# ams-master-pcb.net
KiCad netlist of a schematic drawn in EAGLE
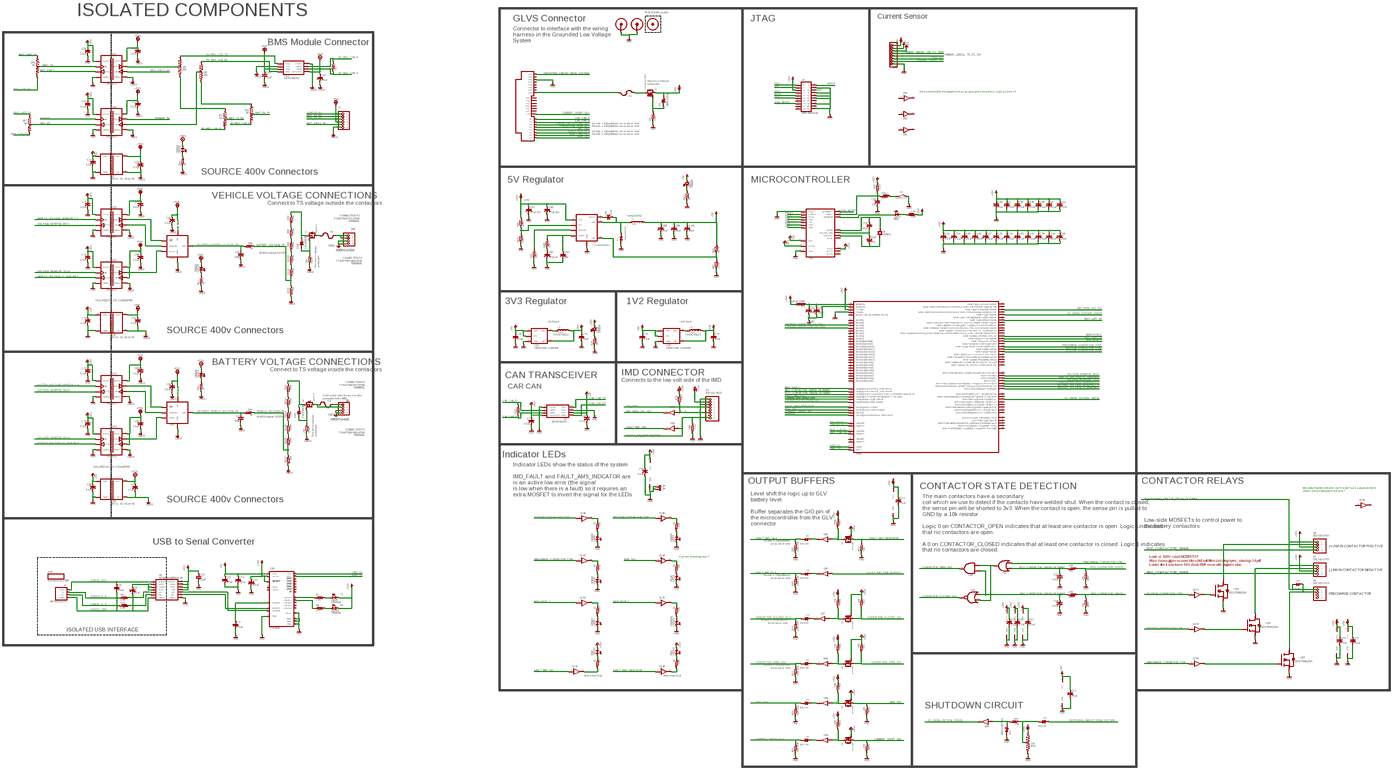
[diagram p0: schematic, sheet 1, overview]
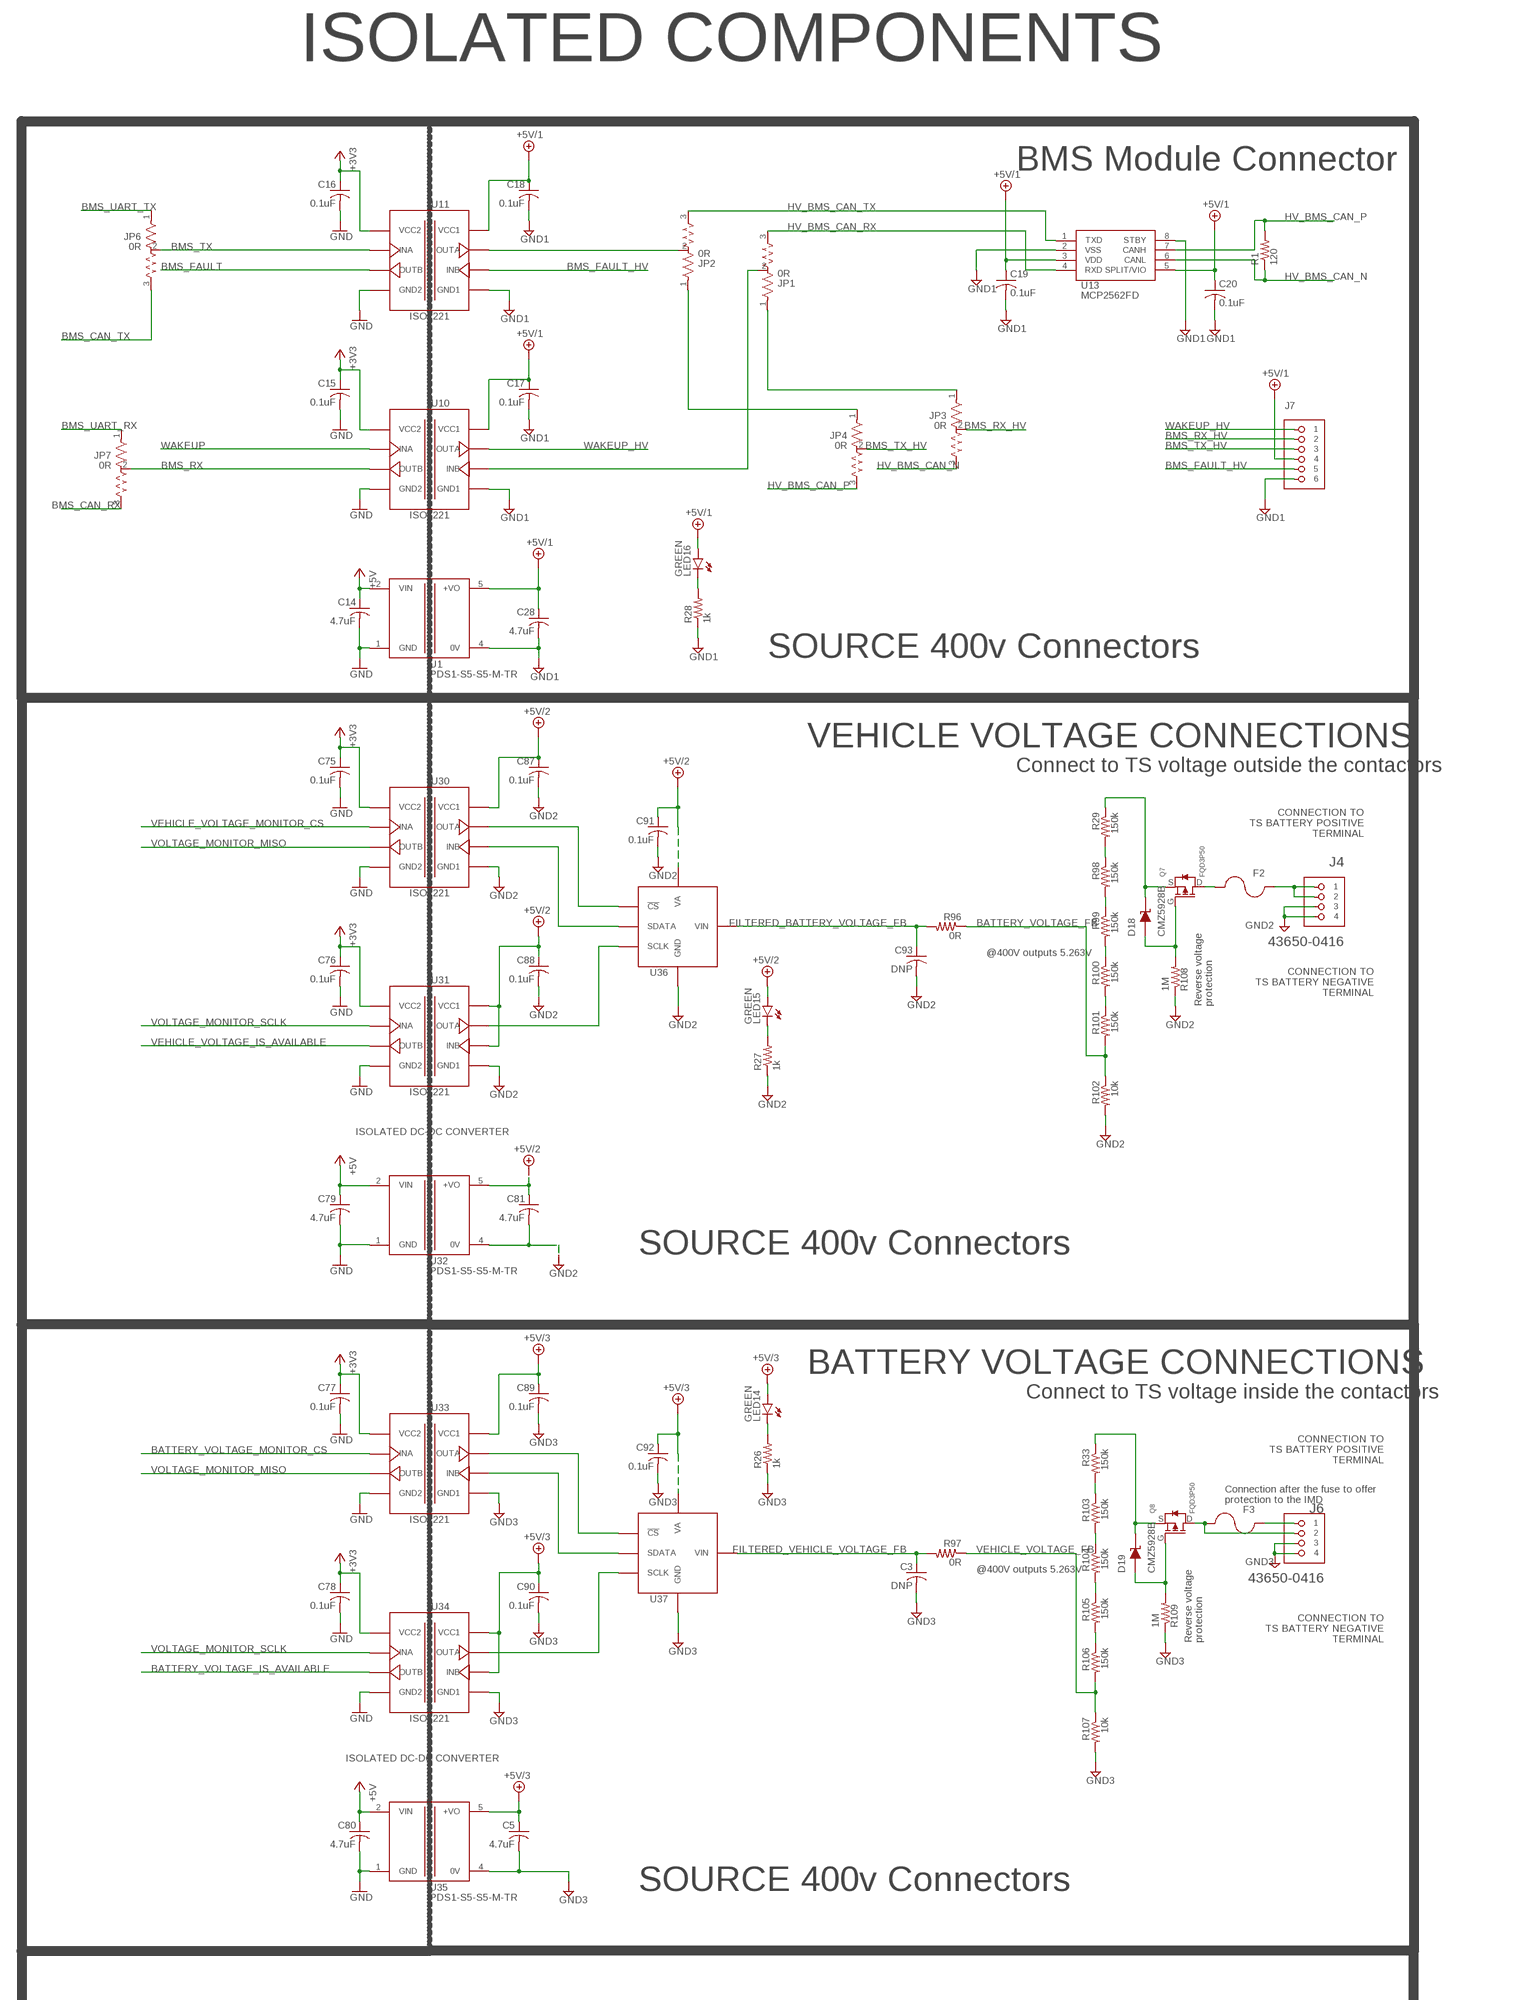
[diagram p1: schematic, sheet 1, part 1 of 6]
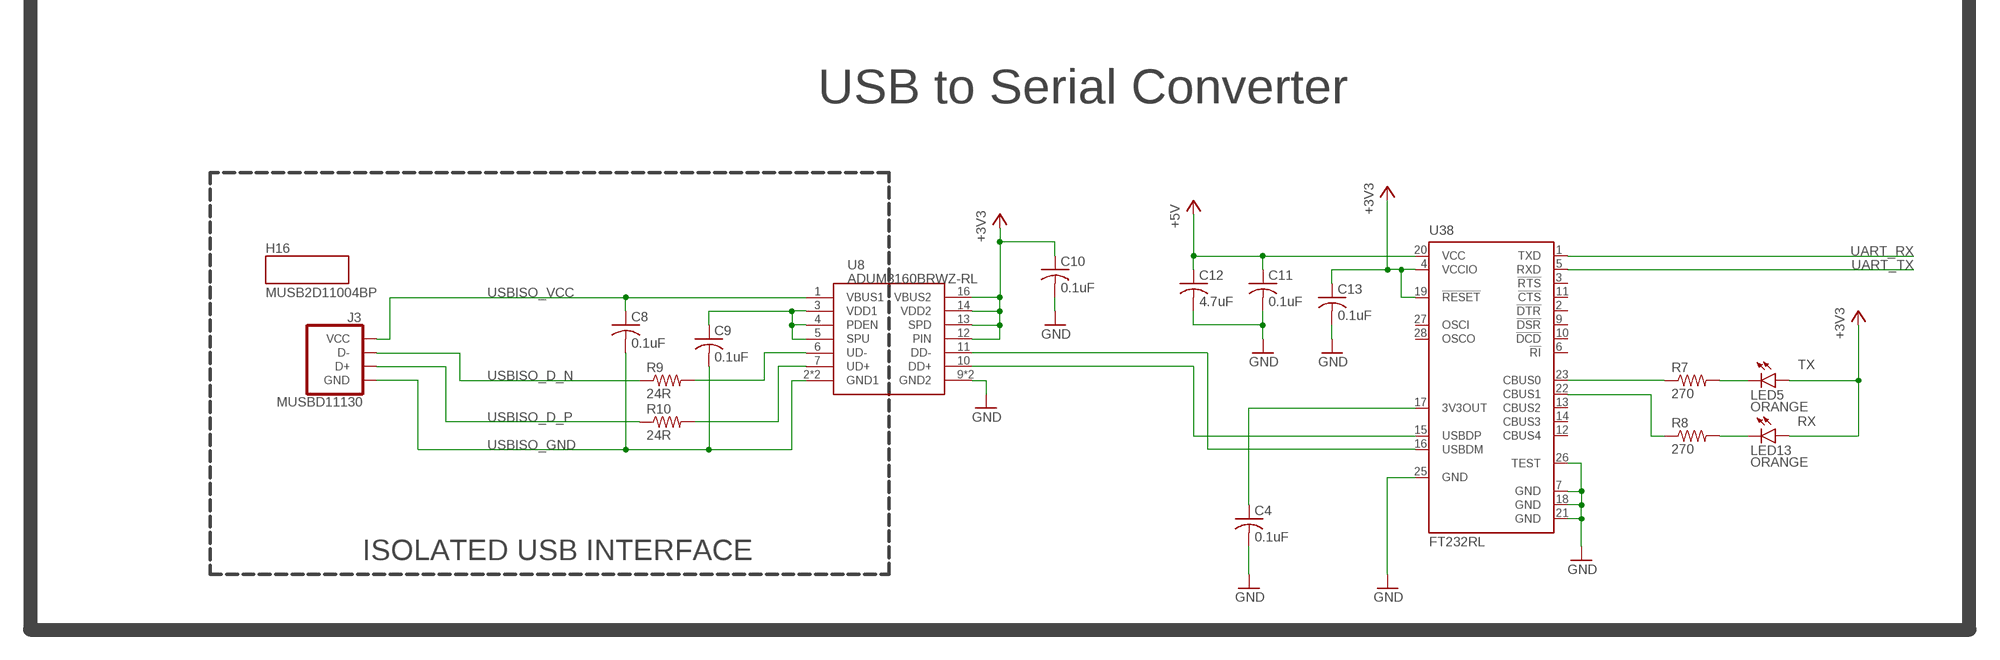
[diagram p2: schematic, sheet 1, part 2 of 6]
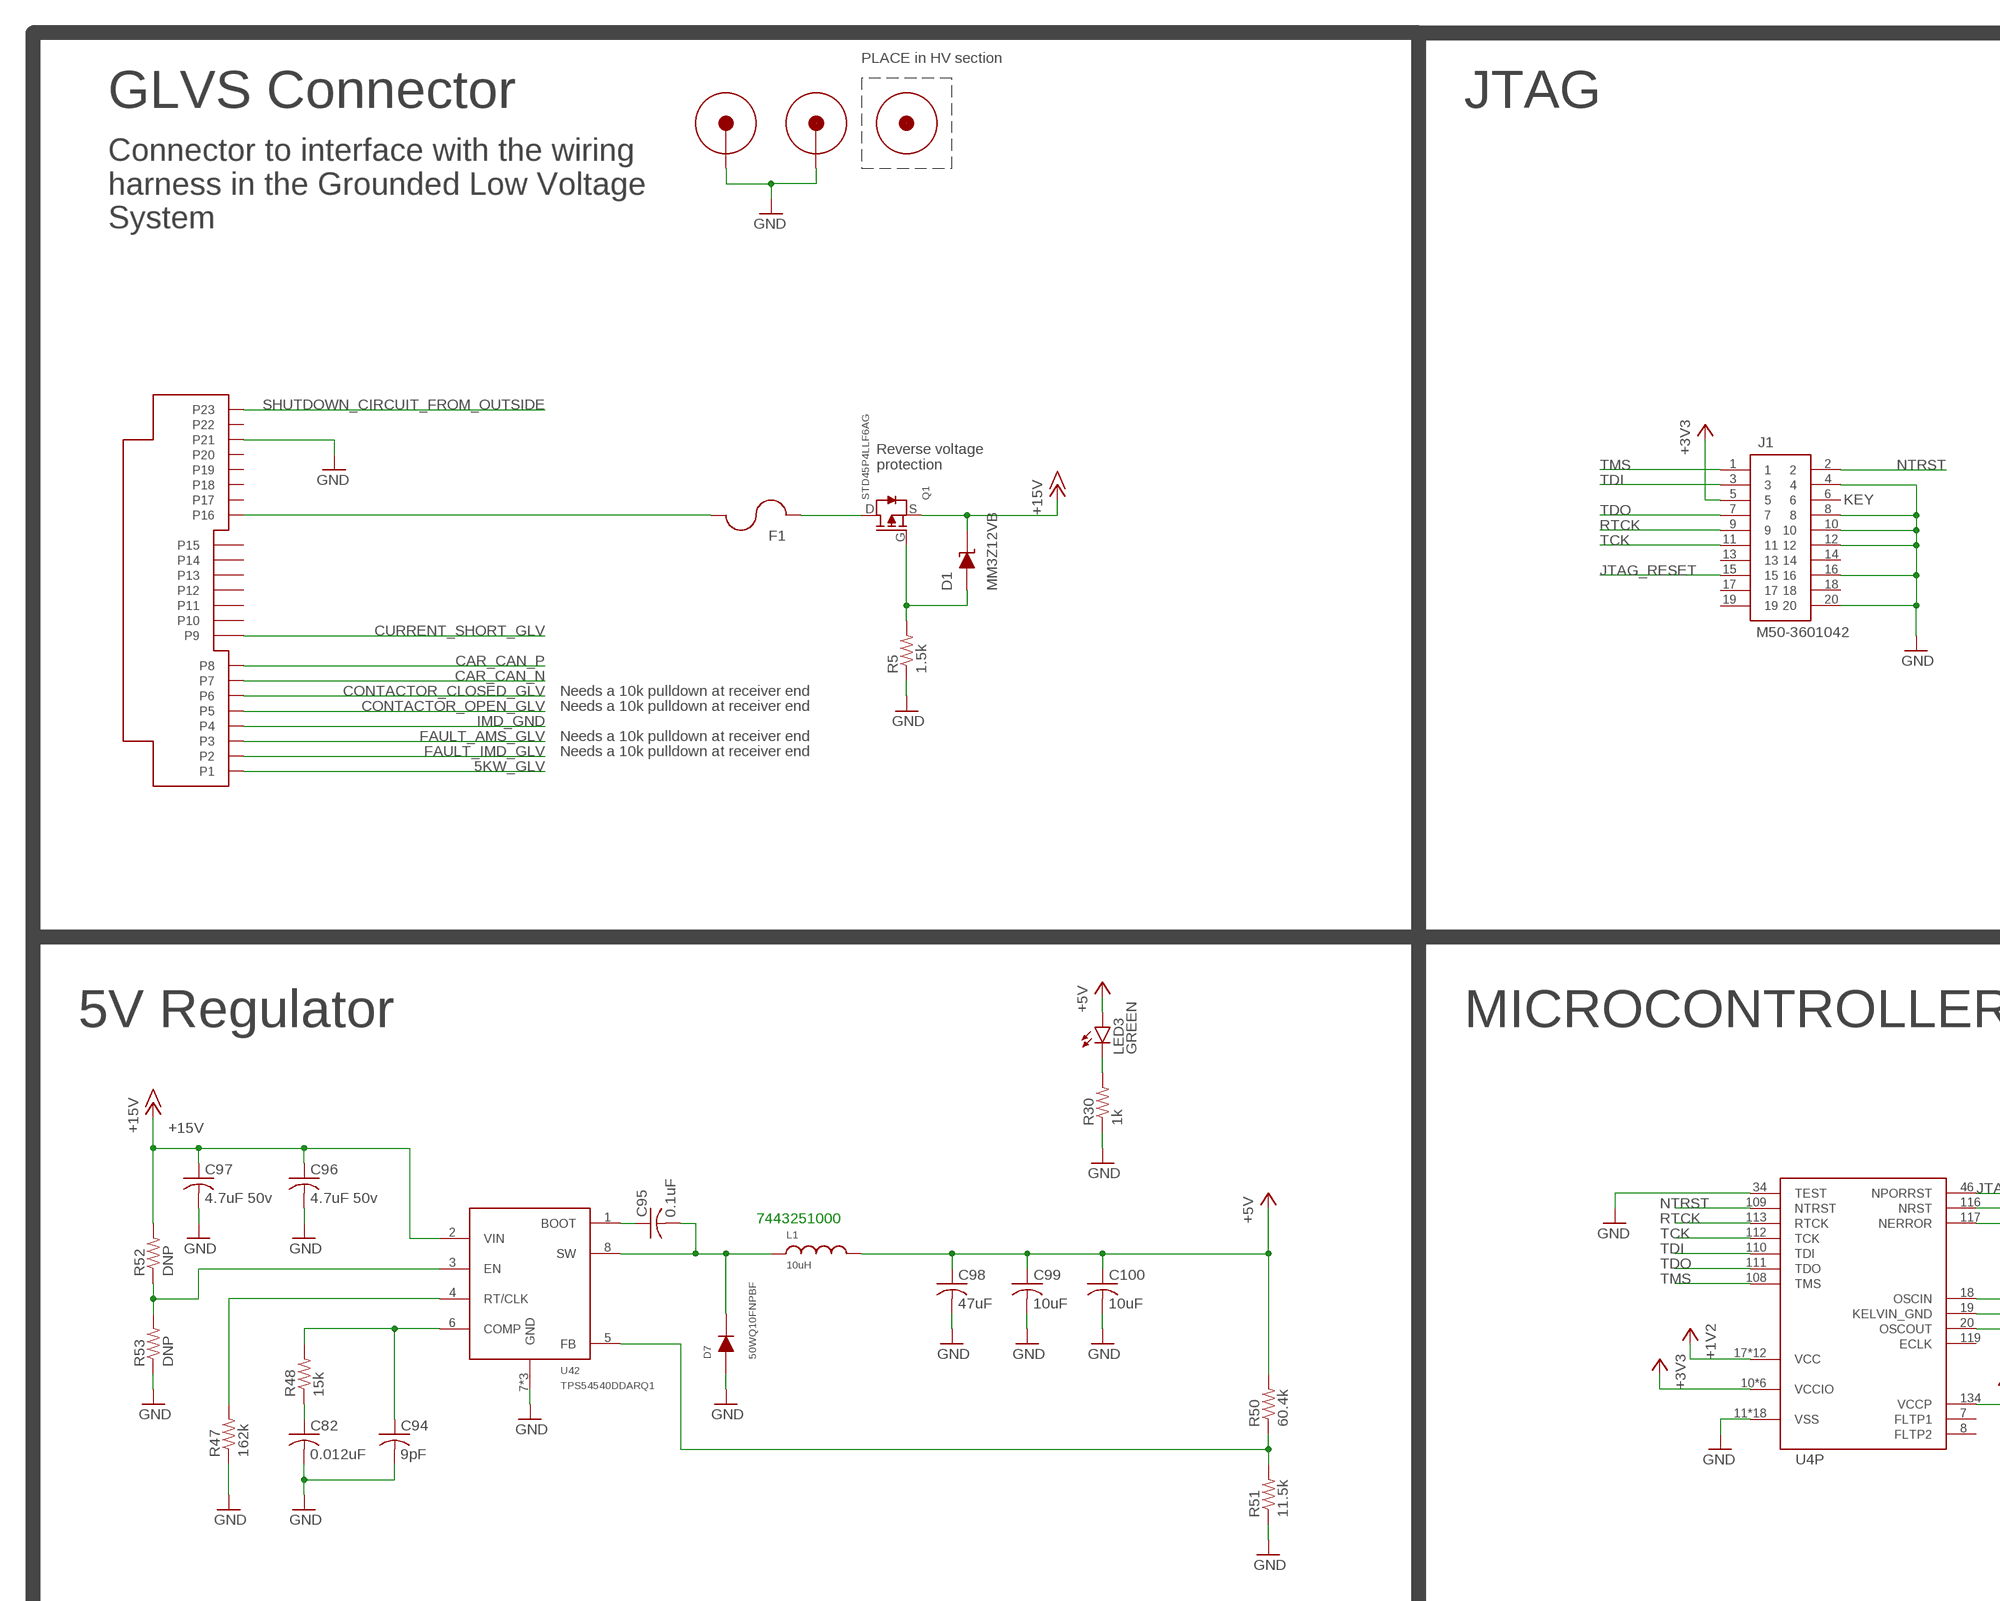
[diagram p3: schematic, sheet 1, part 3 of 6]
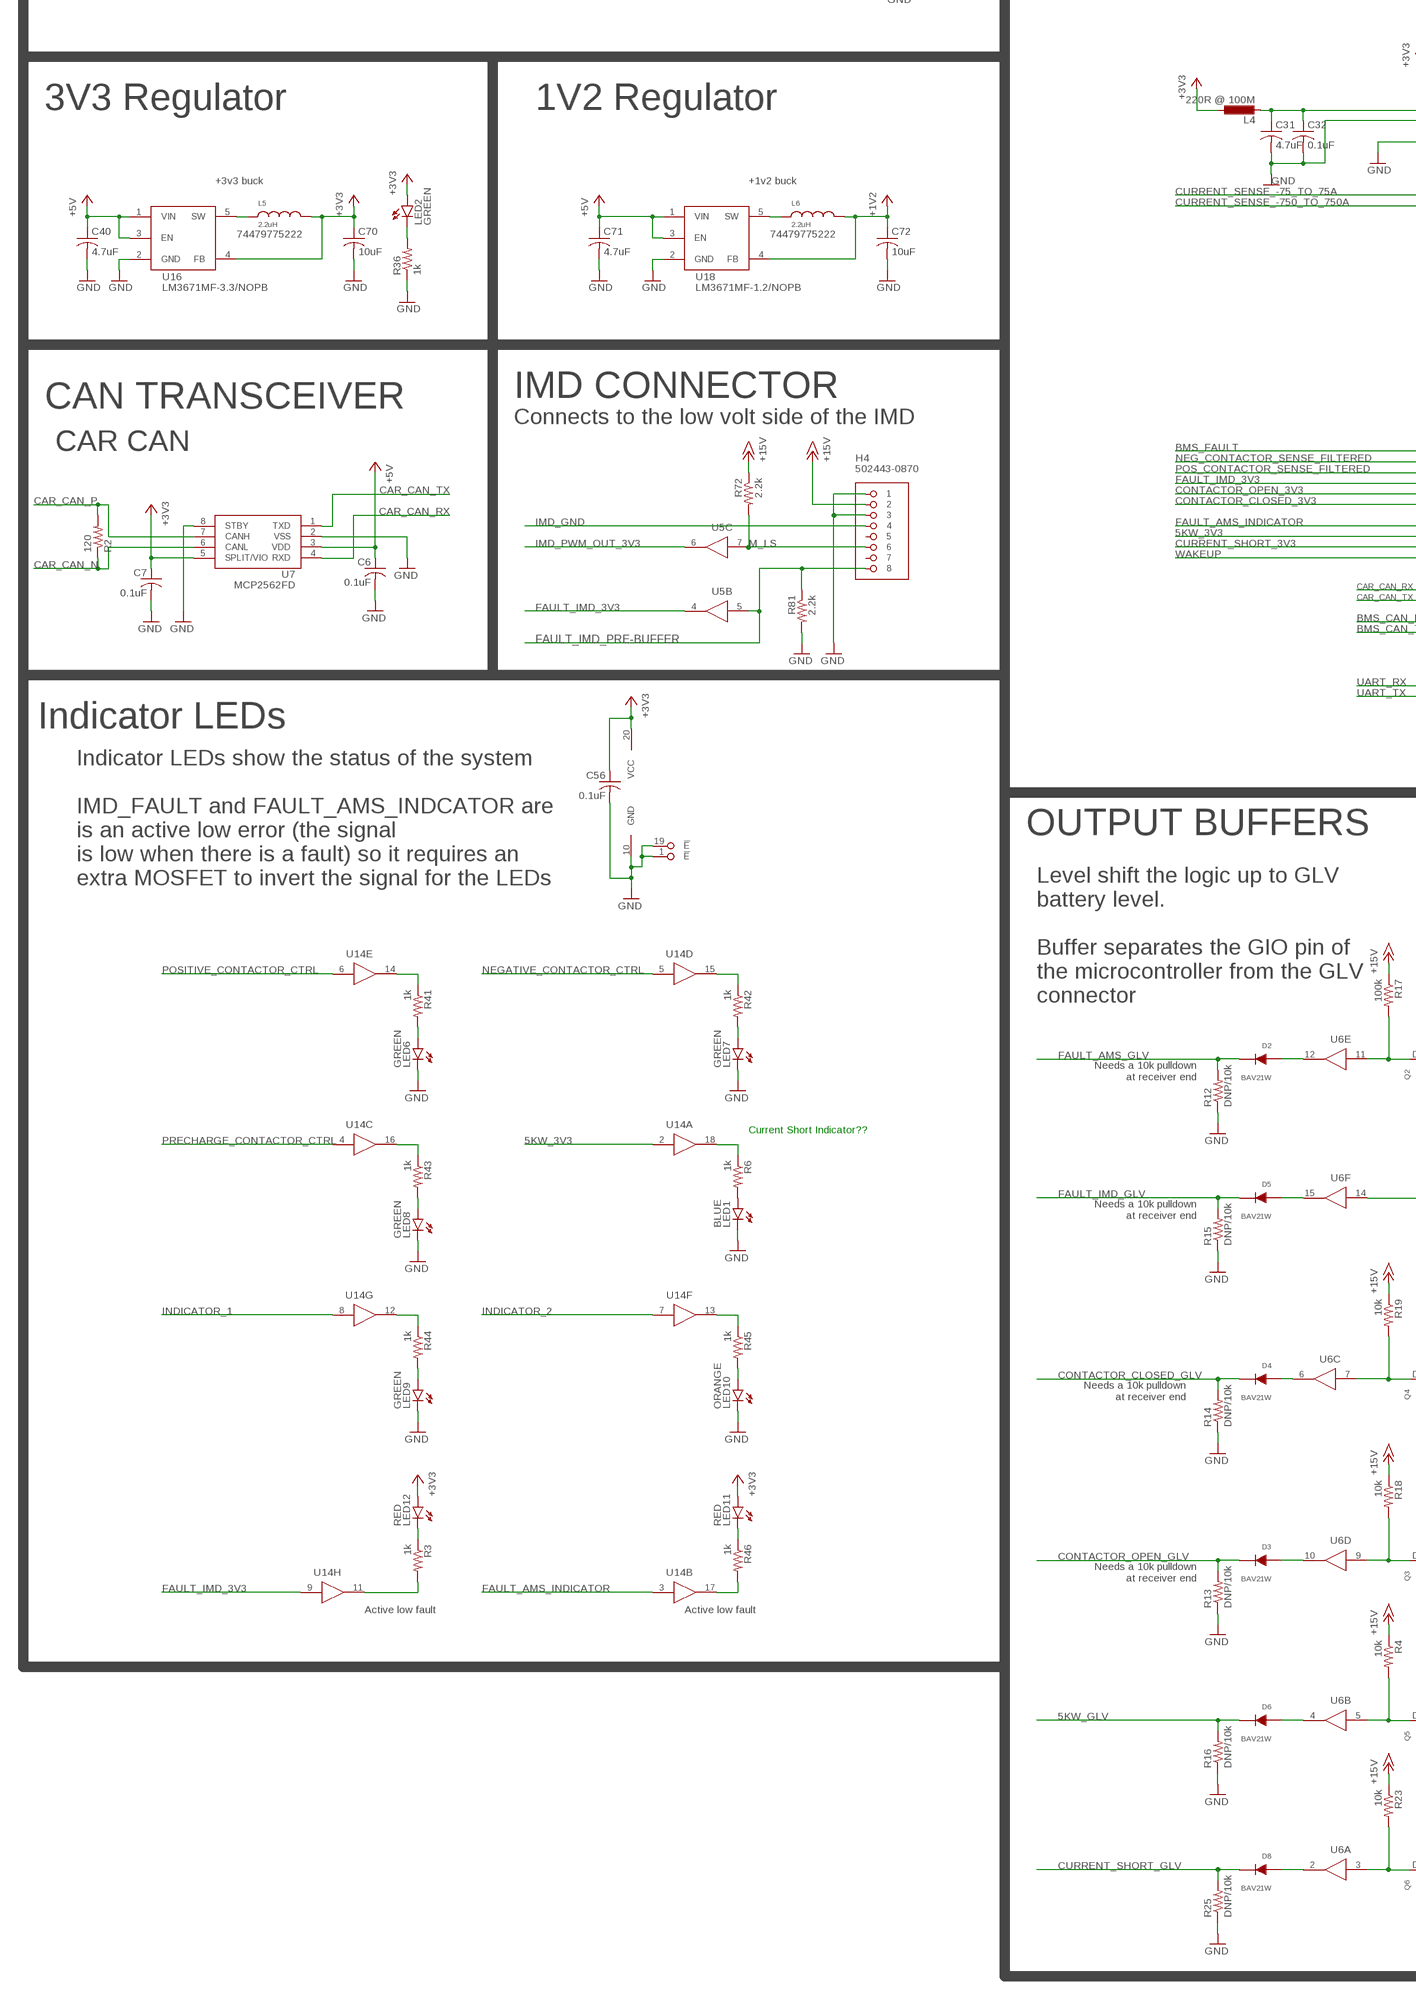
[diagram p4: schematic, sheet 1, part 4 of 6]
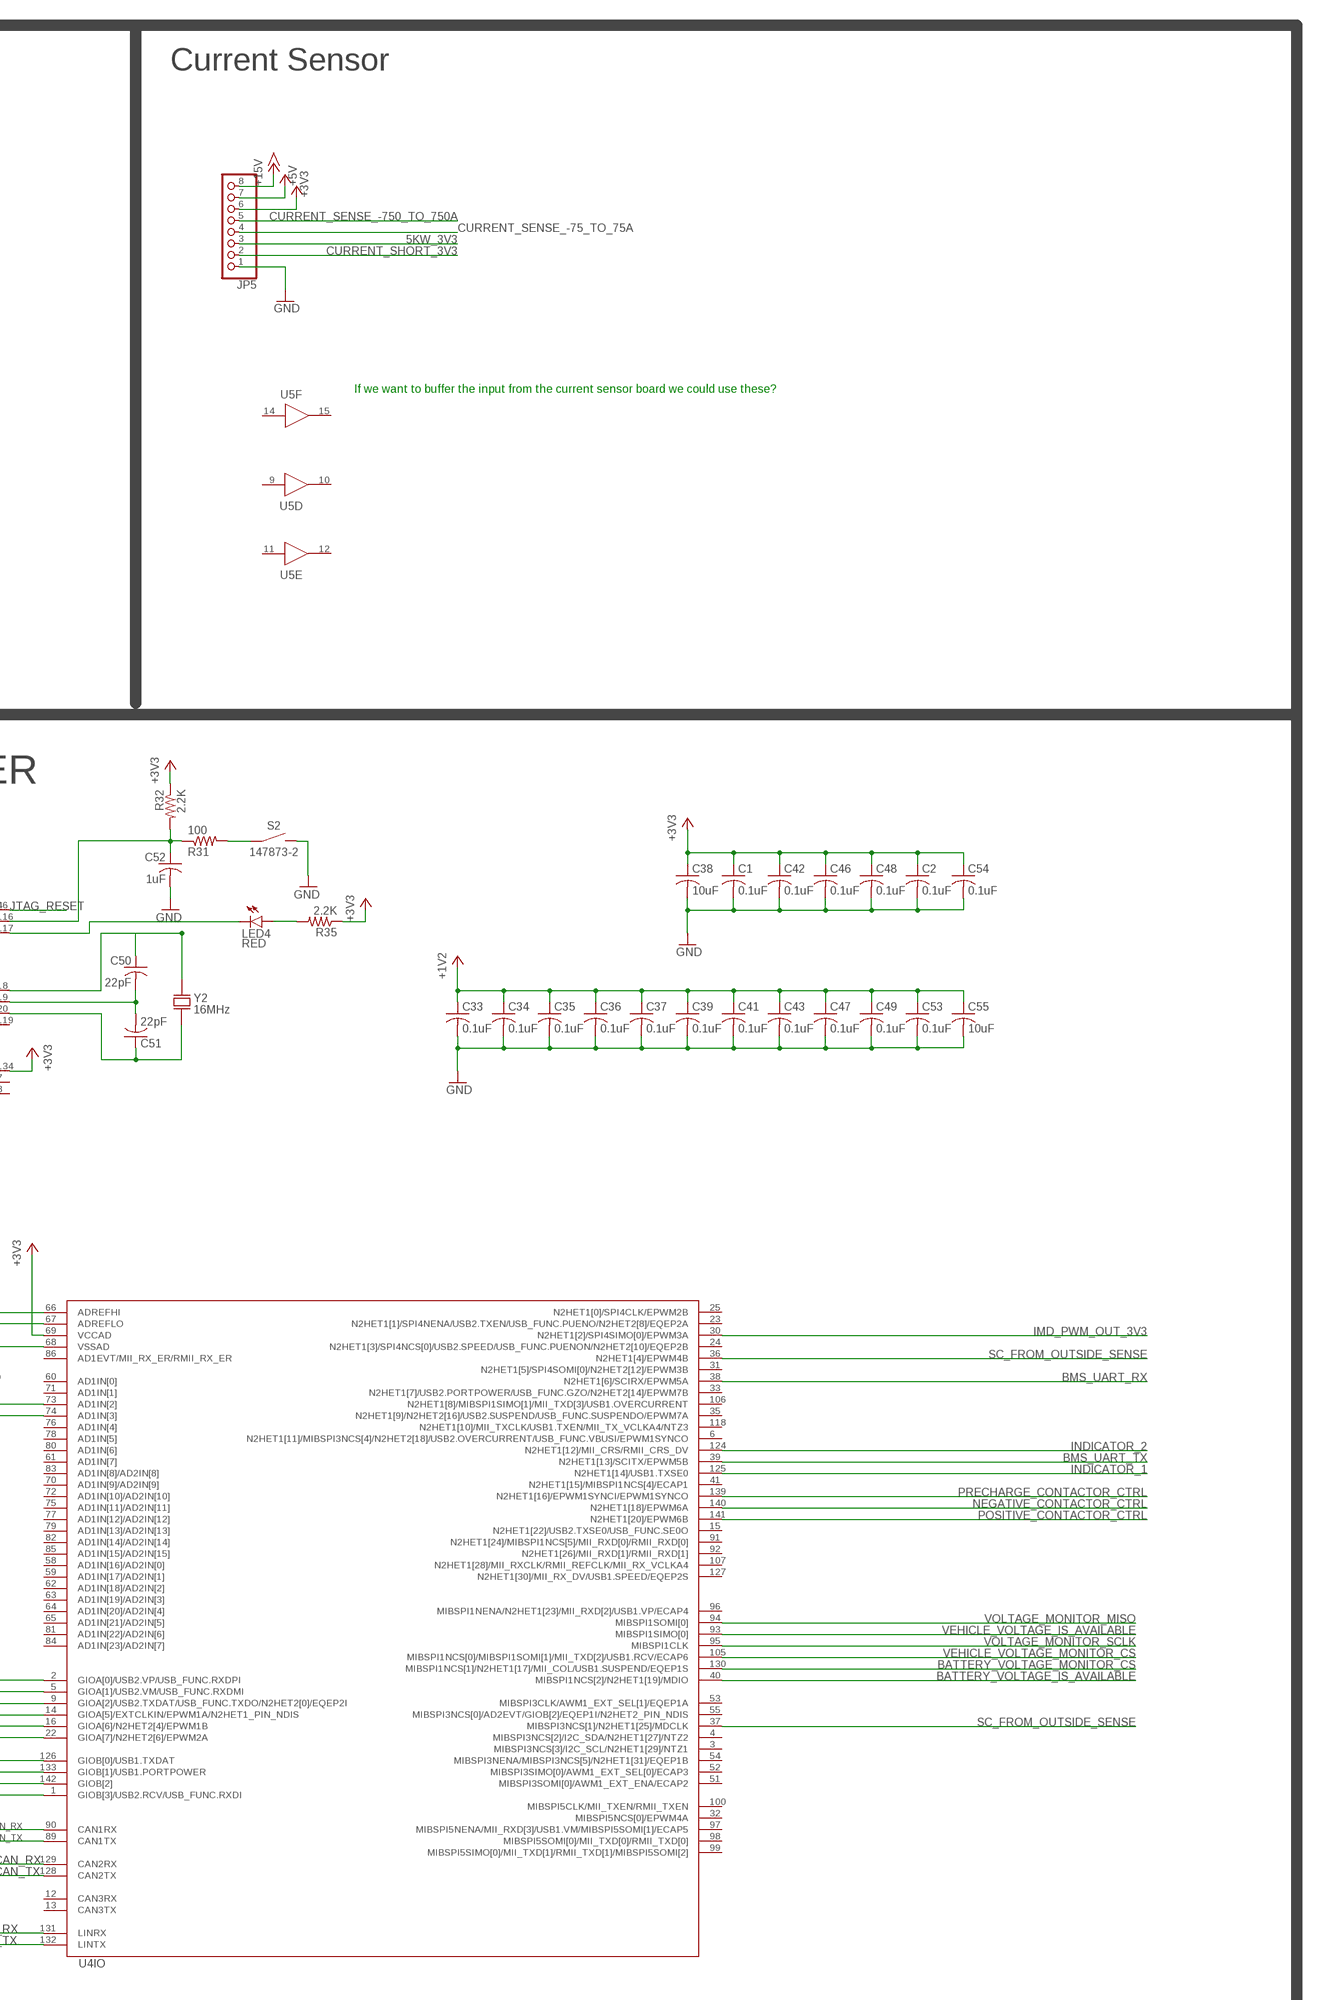
[diagram p5: schematic, sheet 1, part 5 of 6]
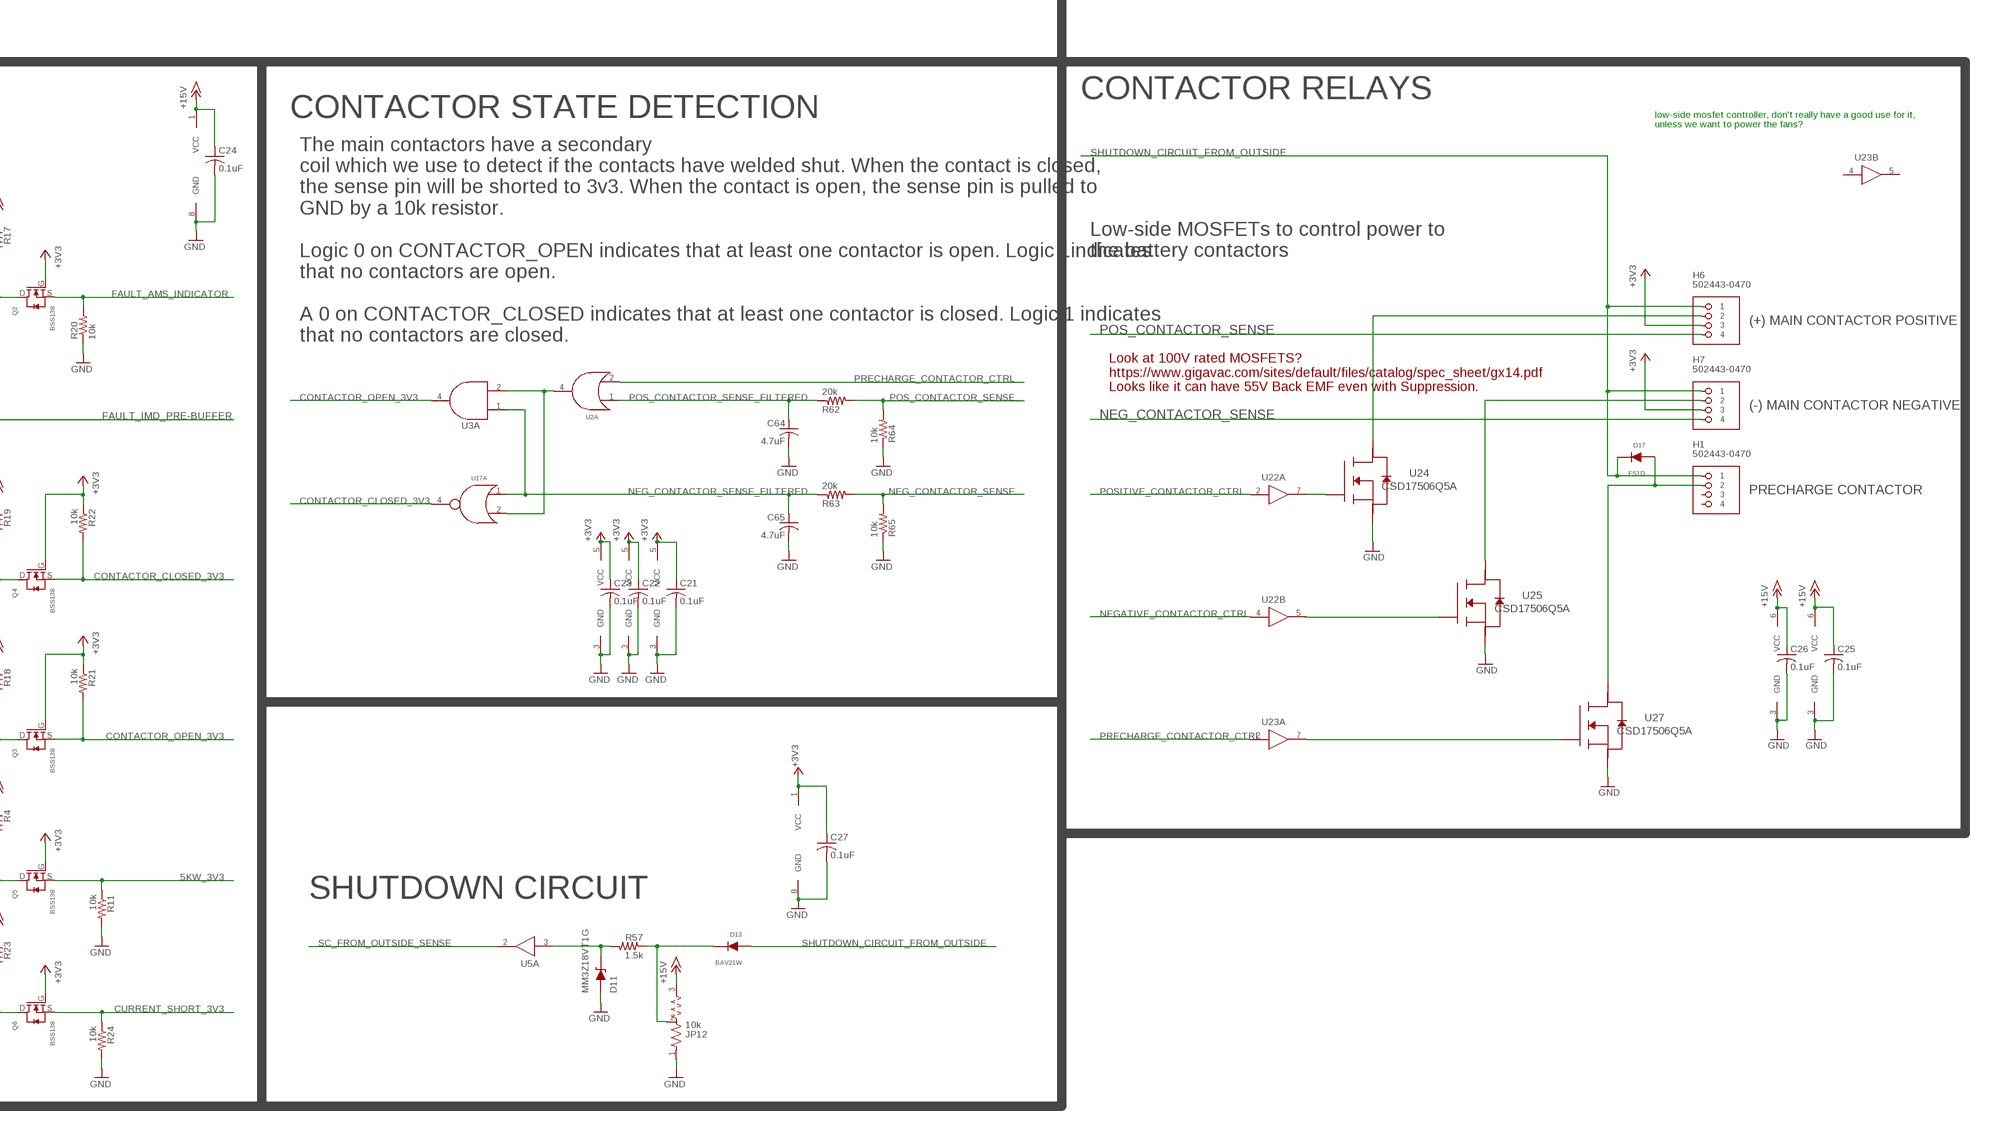
[diagram p6: schematic, sheet 1, part 6 of 6]

(export (version "E")
  (design (tool "Eeschema 10.0.6"))
  (components
    (comp (ref "C1")
      (value "0.1uF")
      (footprint "eagle-import:C0603K")
      (fields (field (name "PARTNO") "GRM188R71E104KA01D"))
      (libsource (lib "eagle-import") (part "C-USC0603K"))
    )
    (comp (ref "C2")
      (value "0.1uF")
      (footprint "eagle-import:C0603K")
      (fields (field (name "PARTNO") "GRM188R71E104KA01D"))
      (libsource (lib "eagle-import") (part "C-USC0603K"))
    )
    (comp (ref "C3")
      (value "DNP")
      (footprint "eagle-import:C0603K")
      (libsource (lib "eagle-import") (part "C-USC0603K"))
    )
    (comp (ref "C4")
      (value "0.1uF")
      (footprint "eagle-import:C0603K")
      (fields (field (name "PARTNO") "GRM188R71E104KA01D"))
      (libsource (lib "eagle-import") (part "C-USC0603K"))
    )
    (comp (ref "C5")
      (value "4.7uF")
      (footprint "eagle-import:C0603K")
      (fields (field (name "PARTNO") "GRM188R61A475KE15D"))
      (libsource (lib "eagle-import") (part "C-USC0603K"))
    )
    (comp (ref "C6")
      (value "0.1uF")
      (footprint "eagle-import:C0603K")
      (fields (field (name "PARTNO") "GRM188R71E104KA01D"))
      (libsource (lib "eagle-import") (part "C-USC0603K"))
    )
    (comp (ref "C7")
      (value "0.1uF")
      (footprint "eagle-import:C0603K")
      (fields (field (name "PARTNO") "GRM188R71E104KA01D"))
      (libsource (lib "eagle-import") (part "C-USC0603K"))
    )
    (comp (ref "C8")
      (value "0.1uF")
      (footprint "eagle-import:C0603K")
      (fields (field (name "PARTNO") "GRM188R71E104KA01D"))
      (libsource (lib "eagle-import") (part "C-USC0603K"))
    )
    (comp (ref "C9")
      (value "0.1uF")
      (footprint "eagle-import:C0603K")
      (fields (field (name "PARTNO") "GRM188R71E104KA01D"))
      (libsource (lib "eagle-import") (part "C-USC0603K"))
    )
    (comp (ref "C10")
      (value "0.1uF")
      (footprint "eagle-import:C0603K")
      (fields (field (name "PARTNO") "GRM188R71E104KA01D"))
      (libsource (lib "eagle-import") (part "C-USC0603K"))
    )
    (comp (ref "C11")
      (value "0.1uF")
      (footprint "eagle-import:C0603K")
      (fields (field (name "PARTNO") "GRM188R71E104KA01D"))
      (libsource (lib "eagle-import") (part "C-USC0603K"))
    )
    (comp (ref "C12")
      (value "4.7uF")
      (footprint "eagle-import:C0603K")
      (fields (field (name "PARTNO") "GRM188R61A475KE15D"))
      (libsource (lib "eagle-import") (part "C-USC0603K"))
    )
    (comp (ref "C13")
      (value "0.1uF")
      (footprint "eagle-import:C0603K")
      (fields (field (name "PARTNO") "GRM188R71E104KA01D"))
      (libsource (lib "eagle-import") (part "C-USC0603K"))
    )
    (comp (ref "C14")
      (value "4.7uF")
      (footprint "eagle-import:C0603K")
      (fields (field (name "PARTNO") "GRM188R61A475KE15D"))
      (libsource (lib "eagle-import") (part "C-USC0603K"))
    )
    (comp (ref "C15")
      (value "0.1uF")
      (footprint "eagle-import:C0603K")
      (fields (field (name "PARTNO") "GRM188R71E104KA01D"))
      (libsource (lib "eagle-import") (part "C-USC0603K"))
    )
    (comp (ref "C16")
      (value "0.1uF")
      (footprint "eagle-import:C0603K")
      (fields (field (name "PARTNO") "GRM188R71E104KA01D"))
      (libsource (lib "eagle-import") (part "C-USC0603K"))
    )
    (comp (ref "C17")
      (value "0.1uF")
      (footprint "eagle-import:C0603K")
      (fields (field (name "PARTNO") "GRM188R71E104KA01D"))
      (libsource (lib "eagle-import") (part "C-USC0603K"))
    )
    (comp (ref "C18")
      (value "0.1uF")
      (footprint "eagle-import:C0603K")
      (fields (field (name "PARTNO") "GRM188R71E104KA01D"))
      (libsource (lib "eagle-import") (part "C-USC0603K"))
    )
    (comp (ref "C19")
      (value "0.1uF")
      (footprint "eagle-import:C0603K")
      (fields (field (name "PARTNO") "GRM188R71E104KA01D"))
      (libsource (lib "eagle-import") (part "C-USC0603K"))
    )
    (comp (ref "C20")
      (value "0.1uF")
      (footprint "eagle-import:C0603K")
      (fields (field (name "PARTNO") "GRM188R71E104KA01D"))
      (libsource (lib "eagle-import") (part "C-USC0603K"))
    )
    (comp (ref "C21")
      (value "0.1uF")
      (footprint "eagle-import:C0603K")
      (fields (field (name "PARTNO") "GRM188R71E104KA01D"))
      (libsource (lib "eagle-import") (part "C-USC0603K"))
    )
    (comp (ref "C22")
      (value "0.1uF")
      (footprint "eagle-import:C0603K")
      (fields (field (name "PARTNO") "GRM188R71E104KA01D"))
      (libsource (lib "eagle-import") (part "C-USC0603K"))
    )
    (comp (ref "C23")
      (value "0.1uF")
      (footprint "eagle-import:C0603K")
      (fields (field (name "PARTNO") "GRM188R71E104KA01D"))
      (libsource (lib "eagle-import") (part "C-USC0603K"))
    )
    (comp (ref "C24")
      (value "0.1uF")
      (footprint "eagle-import:C0603K")
      (fields (field (name "PARTNO") "GRM188R71E104KA01D"))
      (libsource (lib "eagle-import") (part "C-USC0603K"))
    )
    (comp (ref "C25")
      (value "0.1uF")
      (footprint "eagle-import:C0603K")
      (fields (field (name "PARTNO") "GRM188R71E104KA01D"))
      (libsource (lib "eagle-import") (part "C-USC0603K"))
    )
    (comp (ref "C26")
      (value "0.1uF")
      (footprint "eagle-import:C0603K")
      (fields (field (name "PARTNO") "GRM188R71E104KA01D"))
      (libsource (lib "eagle-import") (part "C-USC0603K"))
    )
    (comp (ref "C27")
      (value "0.1uF")
      (footprint "eagle-import:C0603K")
      (fields (field (name "PARTNO") "GRM188R71E104KA01D"))
      (libsource (lib "eagle-import") (part "C-USC0603K"))
    )
    (comp (ref "C28")
      (value "4.7uF")
      (footprint "eagle-import:C0603K")
      (fields (field (name "PARTNO") "GRM188R61A475KE15D"))
      (libsource (lib "eagle-import") (part "C-USC0603K"))
    )
    (comp (ref "C31")
      (value "4.7uF")
      (footprint "eagle-import:C0603K")
      (fields (field (name "PARTNO") "GRM188R61A475KE15D"))
      (libsource (lib "eagle-import") (part "C-USC0603K"))
    )
    (comp (ref "C32")
      (value "0.1uF")
      (footprint "eagle-import:C0603K")
      (fields (field (name "PARTNO") "GRM188R71E104KA01D"))
      (libsource (lib "eagle-import") (part "C-USC0603K"))
    )
    (comp (ref "C33")
      (value "0.1uF")
      (footprint "eagle-import:C0603K")
      (fields (field (name "PARTNO") "GRM188R71E104KA01D"))
      (libsource (lib "eagle-import") (part "C-USC0603K"))
    )
    (comp (ref "C34")
      (value "0.1uF")
      (footprint "eagle-import:C0603K")
      (fields (field (name "PARTNO") "GRM188R71E104KA01D"))
      (libsource (lib "eagle-import") (part "C-USC0603K"))
    )
    (comp (ref "C35")
      (value "0.1uF")
      (footprint "eagle-import:C0603K")
      (fields (field (name "PARTNO") "GRM188R71E104KA01D"))
      (libsource (lib "eagle-import") (part "C-USC0603K"))
    )
    (comp (ref "C36")
      (value "0.1uF")
      (footprint "eagle-import:C0603K")
      (fields (field (name "PARTNO") "GRM188R71E104KA01D"))
      (libsource (lib "eagle-import") (part "C-USC0603K"))
    )
    (comp (ref "C37")
      (value "0.1uF")
      (footprint "eagle-import:C0603K")
      (fields (field (name "PARTNO") "GRM188R71E104KA01D"))
      (libsource (lib "eagle-import") (part "C-USC0603K"))
    )
    (comp (ref "C38")
      (value "10uF")
      (footprint "eagle-import:C0603K")
      (fields (field (name "PARTNO") "GRM188R61A106KE69D"))
      (libsource (lib "eagle-import") (part "C-USC0603K"))
    )
    (comp (ref "C39")
      (value "0.1uF")
      (footprint "eagle-import:C0603K")
      (fields (field (name "PARTNO") "GRM188R71E104KA01D"))
      (libsource (lib "eagle-import") (part "C-USC0603K"))
    )
    (comp (ref "C40")
      (value "4.7uF")
      (footprint "eagle-import:C0603K")
      (fields (field (name "PARTNO") "GRM188R61E475KE11D"))
      (libsource (lib "eagle-import") (part "C-USC0603K"))
    )
    (comp (ref "C41")
      (value "0.1uF")
      (footprint "eagle-import:C0603K")
      (fields (field (name "PARTNO") "GRM188R71E104KA01D"))
      (libsource (lib "eagle-import") (part "C-USC0603K"))
    )
    (comp (ref "C42")
      (value "0.1uF")
      (footprint "eagle-import:C0603K")
      (fields (field (name "PARTNO") "GRM188R71E104KA01D"))
      (libsource (lib "eagle-import") (part "C-USC0603K"))
    )
    (comp (ref "C43")
      (value "0.1uF")
      (footprint "eagle-import:C0603K")
      (fields (field (name "PARTNO") "GRM188R71E104KA01D"))
      (libsource (lib "eagle-import") (part "C-USC0603K"))
    )
    (comp (ref "C46")
      (value "0.1uF")
      (footprint "eagle-import:C0603K")
      (fields (field (name "PARTNO") "GRM188R71E104KA01D"))
      (libsource (lib "eagle-import") (part "C-USC0603K"))
    )
    (comp (ref "C47")
      (value "0.1uF")
      (footprint "eagle-import:C0603K")
      (fields (field (name "PARTNO") "GRM188R71E104KA01D"))
      (libsource (lib "eagle-import") (part "C-USC0603K"))
    )
    (comp (ref "C48")
      (value "0.1uF")
      (footprint "eagle-import:C0603K")
      (fields (field (name "PARTNO") "GRM188R71E104KA01D"))
      (libsource (lib "eagle-import") (part "C-USC0603K"))
    )
    (comp (ref "C49")
      (value "0.1uF")
      (footprint "eagle-import:C0603K")
      (fields (field (name "PARTNO") "GRM188R71E104KA01D"))
      (libsource (lib "eagle-import") (part "C-USC0603K"))
    )
    (comp (ref "C50")
      (value "22pF")
      (footprint "eagle-import:C0603K")
      (fields (field (name "PARTNO") "C1608C0G1H220J080AA"))
      (libsource (lib "eagle-import") (part "C-USC0603K"))
    )
    (comp (ref "C51")
      (value "22pF")
      (footprint "eagle-import:C0603K")
      (fields (field (name "PARTNO") "C1608C0G1H220J080AA"))
      (libsource (lib "eagle-import") (part "C-USC0603K"))
    )
    (comp (ref "C52")
      (value "1uF")
      (footprint "eagle-import:C0603K")
      (fields (field (name "PARTNO") "GRM188R61E105KA12D"))
      (libsource (lib "eagle-import") (part "C-USC0603K"))
    )
    (comp (ref "C53")
      (value "0.1uF")
      (footprint "eagle-import:C0603K")
      (fields (field (name "PARTNO") "GRM188R71E104KA01D"))
      (libsource (lib "eagle-import") (part "C-USC0603K"))
    )
    (comp (ref "C54")
      (value "0.1uF")
      (footprint "eagle-import:C0603K")
      (fields (field (name "PARTNO") "GRM188R71E104KA01D"))
      (libsource (lib "eagle-import") (part "C-USC0603K"))
    )
    (comp (ref "C55")
      (value "10uF")
      (footprint "eagle-import:C0603K")
      (fields (field (name "PARTNO") "GRM188R61A106KE69D"))
      (libsource (lib "eagle-import") (part "C-USC0603K"))
    )
    (comp (ref "C56")
      (value "0.1uF")
      (footprint "eagle-import:C0603K")
      (fields (field (name "PARTNO") "GRM188R71E104KA01D"))
      (libsource (lib "eagle-import") (part "C-USC0603K"))
    )
    (comp (ref "C64")
      (value "4.7uF")
      (footprint "eagle-import:C0603K")
      (fields (field (name "PARTNO") "GRM188R61A475KE15D"))
      (libsource (lib "eagle-import") (part "C-USC0603K"))
    )
    (comp (ref "C65")
      (value "4.7uF")
      (footprint "eagle-import:C0603K")
      (fields (field (name "PARTNO") "GRM188R61A475KE15D"))
      (libsource (lib "eagle-import") (part "C-USC0603K"))
    )
    (comp (ref "C70")
      (value "10uF")
      (footprint "eagle-import:C0603K")
      (fields (field (name "PARTNO") "GRM188R61A106KE69D"))
      (libsource (lib "eagle-import") (part "C-USC0603K"))
    )
    (comp (ref "C71")
      (value "4.7uF")
      (footprint "eagle-import:C0603K")
      (fields (field (name "PARTNO") "GRM188R61E475KE11D"))
      (libsource (lib "eagle-import") (part "C-USC0603K"))
    )
    (comp (ref "C72")
      (value "10uF")
      (footprint "eagle-import:C0603K")
      (fields (field (name "PARTNO") "GRM188R61A106KE69D"))
      (libsource (lib "eagle-import") (part "C-USC0603K"))
    )
    (comp (ref "C75")
      (value "0.1uF")
      (footprint "eagle-import:C0603K")
      (fields (field (name "PARTNO") "GRM188R71E104KA01D"))
      (libsource (lib "eagle-import") (part "C-USC0603K"))
    )
    (comp (ref "C76")
      (value "0.1uF")
      (footprint "eagle-import:C0603K")
      (fields (field (name "PARTNO") "GRM188R71E104KA01D"))
      (libsource (lib "eagle-import") (part "C-USC0603K"))
    )
    (comp (ref "C77")
      (value "0.1uF")
      (footprint "eagle-import:C0603K")
      (fields (field (name "PARTNO") "GRM188R71E104KA01D"))
      (libsource (lib "eagle-import") (part "C-USC0603K"))
    )
    (comp (ref "C78")
      (value "0.1uF")
      (footprint "eagle-import:C0603K")
      (fields (field (name "PARTNO") "GRM188R71E104KA01D"))
      (libsource (lib "eagle-import") (part "C-USC0603K"))
    )
    (comp (ref "C79")
      (value "4.7uF")
      (footprint "eagle-import:C0603K")
      (fields (field (name "PARTNO") "GRM188R61A475KE15D"))
      (libsource (lib "eagle-import") (part "C-USC0603K"))
    )
    (comp (ref "C80")
      (value "4.7uF")
      (footprint "eagle-import:C0603K")
      (fields (field (name "PARTNO") "GRM188R61A475KE15D"))
      (libsource (lib "eagle-import") (part "C-USC0603K"))
    )
    (comp (ref "C81")
      (value "4.7uF")
      (footprint "eagle-import:C0603K")
      (fields (field (name "PARTNO") "GRM188R61A475KE15D"))
      (libsource (lib "eagle-import") (part "C-USC0603K"))
    )
    (comp (ref "C82")
      (value "0.012uF")
      (footprint "eagle-import:C0603K")
      (fields (field (name "PARTNO") "GRM188R71H123KA01D"))
      (libsource (lib "eagle-import") (part "C-USC0603K"))
    )
    (comp (ref "C87")
      (value "0.1uF")
      (footprint "eagle-import:C0603K")
      (fields (field (name "PARTNO") "GRM188R71E104KA01D"))
      (libsource (lib "eagle-import") (part "C-USC0603K"))
    )
    (comp (ref "C88")
      (value "0.1uF")
      (footprint "eagle-import:C0603K")
      (fields (field (name "PARTNO") "GRM188R71E104KA01D"))
      (libsource (lib "eagle-import") (part "C-USC0603K"))
    )
    (comp (ref "C89")
      (value "0.1uF")
      (footprint "eagle-import:C0603K")
      (fields (field (name "PARTNO") "GRM188R71E104KA01D"))
      (libsource (lib "eagle-import") (part "C-USC0603K"))
    )
    (comp (ref "C90")
      (value "0.1uF")
      (footprint "eagle-import:C0603K")
      (fields (field (name "PARTNO") "GRM188R71E104KA01D"))
      (libsource (lib "eagle-import") (part "C-USC0603K"))
    )
    (comp (ref "C91")
      (value "0.1uF")
      (footprint "eagle-import:C0603K")
      (fields (field (name "PARTNO") "GRM188R71E104KA01D"))
      (libsource (lib "eagle-import") (part "C-USC0603K"))
    )
    (comp (ref "C92")
      (value "0.1uF")
      (footprint "eagle-import:C0603K")
      (fields (field (name "PARTNO") "GRM188R71E104KA01D"))
      (libsource (lib "eagle-import") (part "C-USC0603K"))
    )
    (comp (ref "C93")
      (value "DNP")
      (footprint "eagle-import:C0603K")
      (libsource (lib "eagle-import") (part "C-USC0603K"))
    )
    (comp (ref "C94")
      (value "9pF")
      (footprint "eagle-import:C0603K")
      (fields (field (name "PARTNO") "GRM1885C1H9R0DA01D"))
      (libsource (lib "eagle-import") (part "C-USC0603K"))
    )
    (comp (ref "C95")
      (value "0.1uF")
      (footprint "eagle-import:C0603K")
      (fields (field (name "PARTNO") "GRM188R71E104KA01D"))
      (libsource (lib "eagle-import") (part "C-USC0603K"))
    )
    (comp (ref "C96")
      (value "4.7uF 50v")
      (footprint "eagle-import:C1206")
      (fields (field (name "PARTNO") "GRM31CR71H475KA12L"))
      (libsource (lib "eagle-import") (part "C-USC1206"))
    )
    (comp (ref "C97")
      (value "4.7uF 50v")
      (footprint "eagle-import:C1206")
      (fields (field (name "PARTNO") "GRM31CR71H475KA12L"))
      (libsource (lib "eagle-import") (part "C-USC1206"))
    )
    (comp (ref "C98")
      (value "47uF")
      (footprint "eagle-import:C1206")
      (fields (field (name "PARTNO") "GRM31CR61A476ME15L"))
      (libsource (lib "eagle-import") (part "C-USC1206"))
    )
    (comp (ref "C99")
      (value "10uF")
      (footprint "eagle-import:C0603K")
      (fields (field (name "PARTNO") "GRM188R61A106KE69D"))
      (libsource (lib "eagle-import") (part "C-USC0603K"))
    )
    (comp (ref "C100")
      (value "10uF")
      (footprint "eagle-import:C0603K")
      (fields (field (name "PARTNO") "GRM188R61A106KE69D"))
      (libsource (lib "eagle-import") (part "C-USC0603K"))
    )
    (comp (ref "D1")
      (value "MM3Z12VB")
      (footprint "eagle-import:SOD323F")
      (libsource (lib "eagle-import") (part "MM3Z12VB"))
    )
    (comp (ref "D2")
      (value "BAV21W")
      (footprint "eagle-import:BAV21W")
      (fields (field (name "PARTNO") "BAV21WS-TP"))
      (libsource (lib "eagle-import") (part "BAV21W"))
    )
    (comp (ref "D3")
      (value "BAV21W")
      (footprint "eagle-import:BAV21W")
      (fields (field (name "PARTNO") "BAV21WS-TP"))
      (libsource (lib "eagle-import") (part "BAV21W"))
    )
    (comp (ref "D4")
      (value "BAV21W")
      (footprint "eagle-import:BAV21W")
      (fields (field (name "PARTNO") "BAV21WS-TP"))
      (libsource (lib "eagle-import") (part "BAV21W"))
    )
    (comp (ref "D5")
      (value "BAV21W")
      (footprint "eagle-import:BAV21W")
      (fields (field (name "PARTNO") "BAV21WS-TP"))
      (libsource (lib "eagle-import") (part "BAV21W"))
    )
    (comp (ref "D6")
      (value "BAV21W")
      (footprint "eagle-import:BAV21W")
      (fields (field (name "PARTNO") "BAV21WS-TP"))
      (libsource (lib "eagle-import") (part "BAV21W"))
    )
    (comp (ref "D7")
      (value "50WQ10FNPBF")
      (footprint "eagle-import:DPAK")
      (fields (field (name "PARTNO") "VS-50WQ10FNPBF"))
      (libsource (lib "eagle-import") (part "VISHAY-50WQ10FNPBF"))
    )
    (comp (ref "D8")
      (value "BAV21W")
      (footprint "eagle-import:BAV21W")
      (fields (field (name "PARTNO") "BAV21WS-TP"))
      (libsource (lib "eagle-import") (part "BAV21W"))
    )
    (comp (ref "D11")
      (value "MM3Z18VT1G")
      (footprint "eagle-import:SOD-323")
      (libsource (lib "eagle-import") (part "MM3Z18VT1G"))
    )
    (comp (ref "D13")
      (value "BAV21W")
      (footprint "eagle-import:BAV21W")
      (fields (field (name "PARTNO") "BAV21WS-TP"))
      (libsource (lib "eagle-import") (part "BAV21W"))
    )
    (comp (ref "D17")
      (value "ES1D")
      (footprint "eagle-import:ES1D")
      (libsource (lib "eagle-import") (part "ES1D"))
    )
    (comp (ref "D18")
      (value "CMZ5928B")
      (footprint "eagle-import:CMZ59")
      (fields (field (name "PARTNO") "CMZ5928B TR13"))
      (libsource (lib "eagle-import") (part "CMZ5931B"))
    )
    (comp (ref "D19")
      (value "CMZ5928B")
      (footprint "eagle-import:CMZ59")
      (fields (field (name "PARTNO") "CMZ5928B TR13"))
      (libsource (lib "eagle-import") (part "CMZ5931B"))
    )
    (comp (ref "F1")
      (value "0458005.DR")
      (footprint "eagle-import:FUSE_GENERIC_1206")
      (libsource (lib "eagle-import") (part "FUSE_GENERIC_1206"))
    )
    (comp (ref "F2")
      (value "0485001.DR")
      (footprint "eagle-import:LITTELFUSE_485")
      (libsource (lib "eagle-import") (part "LITTELFUSE_485"))
    )
    (comp (ref "F3")
      (value "0485001.DR")
      (footprint "eagle-import:LITTELFUSE_485")
      (libsource (lib "eagle-import") (part "LITTELFUSE_485"))
    )
    (comp (ref "H1")
      (value "502443-0470")
      (footprint "eagle-import:MOLEX_5024430470")
      (fields (field (name "PARTNO") "5024430470"))
      (libsource (lib "eagle-import") (part "MOLEX_502443-0470"))
    )
    (comp (ref "H2")
      (value "MOUNT-HOLE-NPTH3.8MM")
      (footprint "eagle-import:MOUNT-HOLE-3.8MM-NPTH")
      (libsource (lib "eagle-import") (part "MOUNT-HOLE-NPTH3.8MM"))
    )
    (comp (ref "H4")
      (value "502443-0870")
      (footprint "eagle-import:MOLEX_5024430870")
      (fields (field (name "PARTNO") "5024430870"))
      (libsource (lib "eagle-import") (part "MOLEX_502443-0870"))
    )
    (comp (ref "H6")
      (value "502443-0470")
      (footprint "eagle-import:MOLEX_5024430470")
      (fields (field (name "PARTNO") "5024430470"))
      (libsource (lib "eagle-import") (part "MOLEX_502443-0470"))
    )
    (comp (ref "H7")
      (value "502443-0470")
      (footprint "eagle-import:MOLEX_5024430470")
      (fields (field (name "PARTNO") "5024430470"))
      (libsource (lib "eagle-import") (part "MOLEX_502443-0470"))
    )
    (comp (ref "H16")
      (value "MUSB2D11004BP")
      (footprint "eagle-import:EMPTY_FOOTPRINT")
      (libsource (lib "eagle-import") (part "GENERIC_BLOCK"))
    )
    (comp (ref "J1")
      (value "M50-3601042")
      (footprint "eagle-import:SAMTEC-FTR-DUALROW")
      (libsource (lib "eagle-import") (part "CTI-20-MALE"))
    )
    (comp (ref "J2")
      (value "TE-776087")
      (footprint "eagle-import:TE-776087")
      (fields (field (name "PARTNO") "776087-1"))
      (libsource (lib "eagle-import") (part "TE-776087"))
    )
    (comp (ref "J3")
      (value "MUSBD11130")
      (footprint "eagle-import:MUSBD111XX")
      (libsource (lib "eagle-import") (part "MUSBD111XX"))
    )
    (comp (ref "J4")
      (value "MOLEX_43650-0416MOLEX_43650-0416_0_0")
      (footprint "eagle-import:MOLEX_43650-0416_0")
      (fields
        (field (name "3DS_PART_NUMBER") "610-00126")
        (field (name "DIGIKEY_PART_NUMBER") "WM1924-ND")
        (field (name "MF") "Molex")
      )
      (libsource (lib "eagle-import") (part "MOLEX_43650-0416MOLEX_43650-0416_0_0"))
    )
    (comp (ref "J6")
      (value "MOLEX_43650-0416MOLEX_43650-0416_0_0")
      (footprint "eagle-import:MOLEX_43650-0416_0")
      (fields
        (field (name "3DS_PART_NUMBER") "610-00126")
        (field (name "DIGIKEY_PART_NUMBER") "WM1924-ND")
        (field (name "MF") "Molex")
      )
      (libsource (lib "eagle-import") (part "MOLEX_43650-0416MOLEX_43650-0416_0_0"))
    )
    (comp (ref "J7")
      (value "43650-0616")
      (footprint "eagle-import:MOLEX_43650-0616")
      (libsource (lib "eagle-import") (part "MOLEX_43650-0616"))
    )
    (comp (ref "JP1")
      (value "0R")
      (footprint "eagle-import:0603-TWO-WAY-JUMPER")
      (fields (field (name "PARTNO") "ERJ-3EKF1002V"))
      (libsource (lib "eagle-import") (part "TWO-WAY-JUMPER-0603"))
    )
    (comp (ref "JP2")
      (value "0R")
      (footprint "eagle-import:0603-TWO-WAY-JUMPER")
      (fields (field (name "PARTNO") "ERJ-3EKF1002V"))
      (libsource (lib "eagle-import") (part "TWO-WAY-JUMPER-0603"))
    )
    (comp (ref "JP3")
      (value "0R")
      (footprint "eagle-import:0603-TWO-WAY-JUMPER")
      (fields (field (name "PARTNO") "ERJ-3EKF1002V"))
      (libsource (lib "eagle-import") (part "TWO-WAY-JUMPER-0603"))
    )
    (comp (ref "JP4")
      (value "0R")
      (footprint "eagle-import:0603-TWO-WAY-JUMPER")
      (fields (field (name "PARTNO") "ERJ-3EKF1002V"))
      (libsource (lib "eagle-import") (part "TWO-WAY-JUMPER-0603"))
    )
    (comp (ref "JP5")
      (value "PINHD-1X8/90")
      (footprint "eagle-import:1X08_90")
      (libsource (lib "eagle-import") (part "PINHD-1X8/90"))
    )
    (comp (ref "JP6")
      (value "0R")
      (footprint "eagle-import:0603-TWO-WAY-JUMPER")
      (fields (field (name "PARTNO") "ERJ-3EKF1002V"))
      (libsource (lib "eagle-import") (part "TWO-WAY-JUMPER-0603"))
    )
    (comp (ref "JP7")
      (value "0R")
      (footprint "eagle-import:0603-TWO-WAY-JUMPER")
      (fields (field (name "PARTNO") "ERJ-3EKF1002V"))
      (libsource (lib "eagle-import") (part "TWO-WAY-JUMPER-0603"))
    )
    (comp (ref "JP12")
      (value "10k")
      (footprint "eagle-import:0603-TWO-WAY-JUMPER")
      (fields (field (name "PARTNO") "ERJ-3EKF1002V"))
      (libsource (lib "eagle-import") (part "TWO-WAY-JUMPER-0603"))
    )
    (comp (ref "L1")
      (value "10uH")
      (footprint "eagle-import:WURTH-744325XXXX")
      (fields (field (name "PARTNO") "7443251000"))
      (libsource (lib "eagle-import") (part "WURTH-744325XXXX"))
    )
    (comp (ref "L4")
      (value "220R @ 100M")
      (footprint "eagle-import:0805")
      (fields (field (name "PARTNO") "BLM21PG221SN1D"))
      (libsource (lib "eagle-import") (part "INDUCTOR"))
    )
    (comp (ref "L5")
      (value "2.2uH")
      (footprint "eagle-import:0805")
      (fields (field (name "PARTNO") "74479775222"))
      (libsource (lib "eagle-import") (part "L0805"))
    )
    (comp (ref "L6")
      (value "2.2uH")
      (footprint "eagle-import:0805")
      (fields (field (name "PARTNO") "74479775222"))
      (libsource (lib "eagle-import") (part "L0805"))
    )
    (comp (ref "LED1")
      (value "BLUE")
      (footprint "eagle-import:CHIP-LED0805")
      (fields (field (name "PARTNO") "5988110107F"))
      (libsource (lib "eagle-import") (part "LEDCHIP-LED0805"))
    )
    (comp (ref "LED2")
      (value "GREEN")
      (footprint "eagle-import:CHIP-LED0805")
      (fields (field (name "PARTNO") "598-8170-107F"))
      (libsource (lib "eagle-import") (part "LEDCHIP-LED0805"))
    )
    (comp (ref "LED3")
      (value "GREEN")
      (footprint "eagle-import:CHIP-LED0805")
      (fields (field (name "PARTNO") "598-8170-107F"))
      (libsource (lib "eagle-import") (part "LEDCHIP-LED0805"))
    )
    (comp (ref "LED4")
      (value "RED")
      (footprint "eagle-import:CHIP-LED0805")
      (fields (field (name "PARTNO") "5988110107F"))
      (libsource (lib "eagle-import") (part "LEDCHIP-LED0805"))
    )
    (comp (ref "LED5")
      (value "ORANGE")
      (footprint "eagle-import:CHIP-LED0805")
      (fields (field (name "PARTNO") "598-8130-107F"))
      (libsource (lib "eagle-import") (part "LEDCHIP-LED0805"))
    )
    (comp (ref "LED6")
      (value "GREEN")
      (footprint "eagle-import:CHIP-LED0805")
      (fields (field (name "PARTNO") "598-8170-107F"))
      (libsource (lib "eagle-import") (part "LEDCHIP-LED0805"))
    )
    (comp (ref "LED7")
      (value "GREEN")
      (footprint "eagle-import:CHIP-LED0805")
      (fields (field (name "PARTNO") "598-8170-107F"))
      (libsource (lib "eagle-import") (part "LEDCHIP-LED0805"))
    )
    (comp (ref "LED8")
      (value "GREEN")
      (footprint "eagle-import:CHIP-LED0805")
      (fields (field (name "PARTNO") "598-8170-107F"))
      (libsource (lib "eagle-import") (part "LEDCHIP-LED0805"))
    )
    (comp (ref "LED9")
      (value "GREEN")
      (footprint "eagle-import:CHIP-LED0805")
      (fields (field (name "PARTNO") "598-8170-107F"))
      (libsource (lib "eagle-import") (part "LEDCHIP-LED0805"))
    )
    (comp (ref "LED10")
      (value "ORANGE")
      (footprint "eagle-import:CHIP-LED0805")
      (fields (field (name "PARTNO") "598-8130-107F"))
      (libsource (lib "eagle-import") (part "LEDCHIP-LED0805"))
    )
    (comp (ref "LED11")
      (value "RED")
      (footprint "eagle-import:CHIP-LED0805")
      (fields (field (name "PARTNO") "5988110107F"))
      (libsource (lib "eagle-import") (part "LEDCHIP-LED0805"))
    )
    (comp (ref "LED12")
      (value "RED")
      (footprint "eagle-import:CHIP-LED0805")
      (fields (field (name "PARTNO") "5988110107F"))
      (libsource (lib "eagle-import") (part "LEDCHIP-LED0805"))
    )
    (comp (ref "LED13")
      (value "ORANGE")
      (footprint "eagle-import:CHIP-LED0805")
      (fields (field (name "PARTNO") "598-8130-107F"))
      (libsource (lib "eagle-import") (part "LEDCHIP-LED0805"))
    )
    (comp (ref "LED14")
      (value "GREEN")
      (footprint "eagle-import:CHIP-LED0805")
      (fields (field (name "PARTNO") "598-8170-107F"))
      (libsource (lib "eagle-import") (part "LEDCHIP-LED0805"))
    )
    (comp (ref "LED15")
      (value "GREEN")
      (footprint "eagle-import:CHIP-LED0805")
      (fields (field (name "PARTNO") "598-8170-107F"))
      (libsource (lib "eagle-import") (part "LEDCHIP-LED0805"))
    )
    (comp (ref "LED16")
      (value "GREEN")
      (footprint "eagle-import:CHIP-LED0805")
      (fields (field (name "PARTNO") "598-8170-107F"))
      (libsource (lib "eagle-import") (part "LEDCHIP-LED0805"))
    )
    (comp (ref "MP1")
      (value "MOUNT-HOLE3.8MM")
      (footprint "eagle-import:MOUNT-HOLE-3.8MM")
      (libsource (lib "eagle-import") (part "MOUNT-HOLE3.8MM"))
    )
    (comp (ref "MP2")
      (value "MOUNT-HOLE3.8MM")
      (footprint "eagle-import:MOUNT-HOLE-3.8MM")
      (libsource (lib "eagle-import") (part "MOUNT-HOLE3.8MM"))
    )
    (comp (ref "Q1")
      (value "STD45P4LLF6AG")
      (footprint "eagle-import:STD45P4LLF6AG")
      (libsource (lib "eagle-import") (part "STD45P4LLF6AG"))
    )
    (comp (ref "Q2")
      (value "BSS138")
      (footprint "eagle-import:BSS138")
      (libsource (lib "eagle-import") (part "BSS138"))
    )
    (comp (ref "Q3")
      (value "BSS138")
      (footprint "eagle-import:BSS138")
      (libsource (lib "eagle-import") (part "BSS138"))
    )
    (comp (ref "Q4")
      (value "BSS138")
      (footprint "eagle-import:BSS138")
      (libsource (lib "eagle-import") (part "BSS138"))
    )
    (comp (ref "Q5")
      (value "BSS138")
      (footprint "eagle-import:BSS138")
      (libsource (lib "eagle-import") (part "BSS138"))
    )
    (comp (ref "Q6")
      (value "BSS138")
      (footprint "eagle-import:BSS138")
      (libsource (lib "eagle-import") (part "BSS138"))
    )
    (comp (ref "Q7")
      (value "FQD3P50")
      (footprint "eagle-import:FQD3P50")
      (fields (field (name "PARTNO") "FQD3P50TM"))
      (libsource (lib "eagle-import") (part "FQD3P50"))
    )
    (comp (ref "Q8")
      (value "FQD3P50")
      (footprint "eagle-import:FQD3P50")
      (fields (field (name "PARTNO") "FQD3P50TM"))
      (libsource (lib "eagle-import") (part "FQD3P50"))
    )
    (comp (ref "R1")
      (value "120")
      (footprint "eagle-import:R0603")
      (fields (field (name "PARTNO") "ERJ-3EKF1200V"))
      (libsource (lib "eagle-import") (part "R-US_R0603"))
    )
    (comp (ref "R2")
      (value "120")
      (footprint "eagle-import:R0603")
      (fields (field (name "PARTNO") "ERJ-3EKF1200V"))
      (libsource (lib "eagle-import") (part "R-US_R0603"))
    )
    (comp (ref "R3")
      (value "1k")
      (footprint "eagle-import:R0603")
      (fields (field (name "PARTNO") "ERJ-3EKF1001V"))
      (libsource (lib "eagle-import") (part "R-US_R0603"))
    )
    (comp (ref "R4")
      (value "10k")
      (footprint "eagle-import:R0603")
      (fields (field (name "PARTNO") "ERJ-3EKF1002V"))
      (libsource (lib "eagle-import") (part "R-US_R0603"))
    )
    (comp (ref "R5")
      (value "1.5k")
      (footprint "eagle-import:R0603")
      (fields (field (name "PARTNO") "ERJ-3EKF1501V"))
      (libsource (lib "eagle-import") (part "R-US_R0603"))
    )
    (comp (ref "R6")
      (value "1k")
      (footprint "eagle-import:R0603")
      (fields (field (name "PARTNO") "ERJ-3EKF1001V"))
      (libsource (lib "eagle-import") (part "R-US_R0603"))
    )
    (comp (ref "R7")
      (value "270")
      (footprint "eagle-import:R0603")
      (fields (field (name "PARTNO") "ERJ-3EKF2700V"))
      (libsource (lib "eagle-import") (part "R-US_R0603"))
    )
    (comp (ref "R8")
      (value "270")
      (footprint "eagle-import:R0603")
      (fields (field (name "PARTNO") "ERJ-3EKF2700V"))
      (libsource (lib "eagle-import") (part "R-US_R0603"))
    )
    (comp (ref "R9")
      (value "24R")
      (footprint "eagle-import:R0603")
      (fields (field (name "PARTNO") "ERJ-3EKF24R0V"))
      (libsource (lib "eagle-import") (part "R-US_R0603"))
    )
    (comp (ref "R10")
      (value "24R")
      (footprint "eagle-import:R0603")
      (fields (field (name "PARTNO") "ERJ-3EKF24R0V"))
      (libsource (lib "eagle-import") (part "R-US_R0603"))
    )
    (comp (ref "R11")
      (value "10k")
      (footprint "eagle-import:R0603")
      (fields (field (name "PARTNO") "ERJ-3EKF1002V"))
      (libsource (lib "eagle-import") (part "R-US_R0603"))
    )
    (comp (ref "R12")
      (value "DNP/10k")
      (footprint "eagle-import:R0603")
      (libsource (lib "eagle-import") (part "R-US_R0603"))
    )
    (comp (ref "R13")
      (value "DNP/10k")
      (footprint "eagle-import:R0603")
      (libsource (lib "eagle-import") (part "R-US_R0603"))
    )
    (comp (ref "R14")
      (value "DNP/10k")
      (footprint "eagle-import:R0603")
      (libsource (lib "eagle-import") (part "R-US_R0603"))
    )
    (comp (ref "R15")
      (value "DNP/10k")
      (footprint "eagle-import:R0603")
      (libsource (lib "eagle-import") (part "R-US_R0603"))
    )
    (comp (ref "R16")
      (value "DNP/10k")
      (footprint "eagle-import:R0603")
      (libsource (lib "eagle-import") (part "R-US_R0603"))
    )
    (comp (ref "R17")
      (value "100k")
      (footprint "eagle-import:R0603")
      (fields (field (name "PARTNO") "ERJ-3EKF1002V"))
      (libsource (lib "eagle-import") (part "R-US_R0603"))
    )
    (comp (ref "R18")
      (value "10k")
      (footprint "eagle-import:R0603")
      (fields (field (name "PARTNO") "ERJ-3EKF1002V"))
      (libsource (lib "eagle-import") (part "R-US_R0603"))
    )
    (comp (ref "R19")
      (value "10k")
      (footprint "eagle-import:R0603")
      (fields (field (name "PARTNO") "ERJ-3EKF1002V"))
      (libsource (lib "eagle-import") (part "R-US_R0603"))
    )
    (comp (ref "R20")
      (value "10k")
      (footprint "eagle-import:R0603")
      (fields (field (name "PARTNO") "ERJ-3EKF1002V"))
      (libsource (lib "eagle-import") (part "R-US_R0603"))
    )
    (comp (ref "R21")
      (value "10k")
      (footprint "eagle-import:R0603")
      (fields (field (name "PARTNO") "ERJ-3EKF1002V"))
      (libsource (lib "eagle-import") (part "R-US_R0603"))
    )
    (comp (ref "R22")
      (value "10k")
      (footprint "eagle-import:R0603")
      (fields (field (name "PARTNO") "ERJ-3EKF1002V"))
      (libsource (lib "eagle-import") (part "R-US_R0603"))
    )
    (comp (ref "R23")
      (value "10k")
      (footprint "eagle-import:R0603")
      (fields (field (name "PARTNO") "ERJ-3EKF1002V"))
      (libsource (lib "eagle-import") (part "R-US_R0603"))
    )
    (comp (ref "R24")
      (value "10k")
      (footprint "eagle-import:R0603")
      (fields (field (name "PARTNO") "ERJ-3EKF1002V"))
      (libsource (lib "eagle-import") (part "R-US_R0603"))
    )
    (comp (ref "R25")
      (value "DNP/10k")
      (footprint "eagle-import:R0603")
      (libsource (lib "eagle-import") (part "R-US_R0603"))
    )
    (comp (ref "R26")
      (value "1k")
      (footprint "eagle-import:R0603")
      (fields (field (name "PARTNO") "ERJ-3EKF1001V"))
      (libsource (lib "eagle-import") (part "R-US_R0603"))
    )
    (comp (ref "R27")
      (value "1k")
      (footprint "eagle-import:R0603")
      (fields (field (name "PARTNO") "ERJ-3EKF1001V"))
      (libsource (lib "eagle-import") (part "R-US_R0603"))
    )
    (comp (ref "R28")
      (value "1k")
      (footprint "eagle-import:R0603")
      (fields (field (name "PARTNO") "ERJ-3EKF1001V"))
      (libsource (lib "eagle-import") (part "R-US_R0603"))
    )
    (comp (ref "R29")
      (value "150k")
      (footprint "eagle-import:R0805")
      (fields (field (name "PARTNO") "ERJ-6ENF1503V"))
      (libsource (lib "eagle-import") (part "R-US_R0805"))
    )
    (comp (ref "R30")
      (value "1k")
      (footprint "eagle-import:R0603")
      (fields (field (name "PARTNO") "ERJ-3EKF1001V"))
      (libsource (lib "eagle-import") (part "R-US_R0603"))
    )
    (comp (ref "R31")
      (value "100")
      (footprint "eagle-import:R0603")
      (fields (field (name "PARTNO") "ERJ-3EKF1000V"))
      (libsource (lib "eagle-import") (part "R-US_R0603"))
    )
    (comp (ref "R32")
      (value "2.2K")
      (footprint "eagle-import:R0603")
      (fields (field (name "PARTNO") "ERJ-3EKF2201V"))
      (libsource (lib "eagle-import") (part "R-US_R0603"))
    )
    (comp (ref "R33")
      (value "150k")
      (footprint "eagle-import:R0805")
      (fields (field (name "PARTNO") "ERJ-6ENF1503V"))
      (libsource (lib "eagle-import") (part "R-US_R0805"))
    )
    (comp (ref "R35")
      (value "2.2K")
      (footprint "eagle-import:R0603")
      (fields (field (name "PARTNO") "ERJ-3EKF2201V"))
      (libsource (lib "eagle-import") (part "R-US_R0603"))
    )
    (comp (ref "R36")
      (value "1k")
      (footprint "eagle-import:R0603")
      (fields (field (name "PARTNO") "ERJ-3EKF1001V"))
      (libsource (lib "eagle-import") (part "R-US_R0603"))
    )
    (comp (ref "R41")
      (value "1k")
      (footprint "eagle-import:R0603")
      (fields (field (name "PARTNO") "ERJ-3EKF1001V"))
      (libsource (lib "eagle-import") (part "R-US_R0603"))
    )
    (comp (ref "R42")
      (value "1k")
      (footprint "eagle-import:R0603")
      (fields (field (name "PARTNO") "ERJ-3EKF1001V"))
      (libsource (lib "eagle-import") (part "R-US_R0603"))
    )
    (comp (ref "R43")
      (value "1k")
      (footprint "eagle-import:R0603")
      (fields (field (name "PARTNO") "ERJ-3EKF1001V"))
      (libsource (lib "eagle-import") (part "R-US_R0603"))
    )
    (comp (ref "R44")
      (value "1k")
      (footprint "eagle-import:R0603")
      (fields (field (name "PARTNO") "ERJ-3EKF1001V"))
      (libsource (lib "eagle-import") (part "R-US_R0603"))
    )
    (comp (ref "R45")
      (value "1k")
      (footprint "eagle-import:R0603")
      (fields (field (name "PARTNO") "ERJ-3EKF1001V"))
      (libsource (lib "eagle-import") (part "R-US_R0603"))
    )
    (comp (ref "R46")
      (value "1k")
      (footprint "eagle-import:R0603")
      (fields (field (name "PARTNO") "ERJ-3EKF1001V"))
      (libsource (lib "eagle-import") (part "R-US_R0603"))
    )
    (comp (ref "R47")
      (value "162k")
      (footprint "eagle-import:R0603")
      (fields (field (name "PARTNO") "ERJ-3EKF1623V"))
      (libsource (lib "eagle-import") (part "R-US_R0603"))
    )
    (comp (ref "R48")
      (value "15k")
      (footprint "eagle-import:R0603")
      (fields (field (name "PARTNO") "ERJ-3EKF1502V"))
      (libsource (lib "eagle-import") (part "R-US_R0603"))
    )
    (comp (ref "R50")
      (value "60.4k")
      (footprint "eagle-import:R0603")
      (fields (field (name "PARTNO") "ERJ-3EKF6042V"))
      (libsource (lib "eagle-import") (part "R-US_R0603"))
    )
    (comp (ref "R51")
      (value "11.5k")
      (footprint "eagle-import:R0603")
      (fields (field (name "PARTNO") "ERJ-3EKF1152V"))
      (libsource (lib "eagle-import") (part "R-US_R0603"))
    )
    (comp (ref "R52")
      (value "DNP")
      (footprint "eagle-import:R0603")
      (libsource (lib "eagle-import") (part "R-US_R0603"))
    )
    (comp (ref "R53")
      (value "DNP")
      (footprint "eagle-import:R0603")
      (libsource (lib "eagle-import") (part "R-US_R0603"))
    )
    (comp (ref "R57")
      (value "1.5k")
      (footprint "eagle-import:R0603")
      (fields (field (name "PARTNO") "ERJ-3EKF1501V"))
      (libsource (lib "eagle-import") (part "R-US_R0603"))
    )
    (comp (ref "R62")
      (value "20k")
      (footprint "eagle-import:R0603")
      (fields (field (name "PARTNO") "ERJ-3EKF2002V"))
      (libsource (lib "eagle-import") (part "R-US_R0603"))
    )
    (comp (ref "R63")
      (value "20k")
      (footprint "eagle-import:R0603")
      (fields (field (name "PARTNO") "ERJ-3EKF2002V"))
      (libsource (lib "eagle-import") (part "R-US_R0603"))
    )
    (comp (ref "R64")
      (value "10k")
      (footprint "eagle-import:R0603")
      (fields (field (name "PARTNO") "ERJ-3EKF1002V"))
      (libsource (lib "eagle-import") (part "R-US_R0603"))
    )
    (comp (ref "R65")
      (value "10k")
      (footprint "eagle-import:R0603")
      (fields (field (name "PARTNO") "ERJ-3EKF1002V"))
      (libsource (lib "eagle-import") (part "R-US_R0603"))
    )
    (comp (ref "R72")
      (value "2.2k")
      (footprint "eagle-import:R0603")
      (fields (field (name "PARTNO") "ERJ-3EKF2201V"))
      (libsource (lib "eagle-import") (part "R-US_R0603"))
    )
    (comp (ref "R81")
      (value "2.2k")
      (footprint "eagle-import:R0603")
      (fields (field (name "PARTNO") "ERJ-3EKF2201V"))
      (libsource (lib "eagle-import") (part "R-US_R0603"))
    )
    (comp (ref "R96")
      (value "0R")
      (footprint "eagle-import:R0603")
      (fields (field (name "PARTNO") "ERJ-3GEY0R00V"))
      (libsource (lib "eagle-import") (part "R-US_R0603"))
    )
    (comp (ref "R97")
      (value "0R")
      (footprint "eagle-import:R0603")
      (fields (field (name "PARTNO") "ERJ-3GEY0R00V"))
      (libsource (lib "eagle-import") (part "R-US_R0603"))
    )
    (comp (ref "R98")
      (value "150k")
      (footprint "eagle-import:R0805")
      (fields (field (name "PARTNO") "ERJ-6ENF1503V"))
      (libsource (lib "eagle-import") (part "R-US_R0805"))
    )
    (comp (ref "R99")
      (value "150k")
      (footprint "eagle-import:R0805")
      (fields (field (name "PARTNO") "ERJ-6ENF1503V"))
      (libsource (lib "eagle-import") (part "R-US_R0805"))
    )
    (comp (ref "R100")
      (value "150k")
      (footprint "eagle-import:R0805")
      (fields (field (name "PARTNO") "ERJ-6ENF1503V"))
      (libsource (lib "eagle-import") (part "R-US_R0805"))
    )
    (comp (ref "R101")
      (value "150k")
      (footprint "eagle-import:R0805")
      (fields (field (name "PARTNO") "ERJ-6ENF1503V"))
      (libsource (lib "eagle-import") (part "R-US_R0805"))
    )
    (comp (ref "R102")
      (value "10k")
      (footprint "eagle-import:R0603")
      (fields (field (name "PARTNO") "ERJ-3EKF1002V"))
      (libsource (lib "eagle-import") (part "R-US_R0603"))
    )
    (comp (ref "R103")
      (value "150k")
      (footprint "eagle-import:R0805")
      (fields (field (name "PARTNO") "ERJ-6ENF1503V"))
      (libsource (lib "eagle-import") (part "R-US_R0805"))
    )
    (comp (ref "R104")
      (value "150k")
      (footprint "eagle-import:R0805")
      (fields (field (name "PARTNO") "ERJ-6ENF1503V"))
      (libsource (lib "eagle-import") (part "R-US_R0805"))
    )
    (comp (ref "R105")
      (value "150k")
      (footprint "eagle-import:R0805")
      (fields (field (name "PARTNO") "ERJ-6ENF1503V"))
      (libsource (lib "eagle-import") (part "R-US_R0805"))
    )
    (comp (ref "R106")
      (value "150k")
      (footprint "eagle-import:R0805")
      (fields (field (name "PARTNO") "ERJ-6ENF1503V"))
      (libsource (lib "eagle-import") (part "R-US_R0805"))
    )
    (comp (ref "R107")
      (value "10k")
      (footprint "eagle-import:R0603")
      (fields (field (name "PARTNO") "ERJ-3EKF1002V"))
      (libsource (lib "eagle-import") (part "R-US_R0603"))
    )
    (comp (ref "R108")
      (value "1M")
      (footprint "eagle-import:R0805")
      (fields (field (name "PARTNO") "ERJ-6ENF1004V"))
      (libsource (lib "eagle-import") (part "R-US_R0805"))
    )
    (comp (ref "R109")
      (value "1M")
      (footprint "eagle-import:R0805")
      (fields (field (name "PARTNO") "ERJ-6ENF1004V"))
      (libsource (lib "eagle-import") (part "R-US_R0805"))
    )
    (comp (ref "S2")
      (value "147873-2")
      (footprint "eagle-import:TE-147873-2")
      (libsource (lib "eagle-import") (part "TE-147873-2"))
    )
    (comp (ref "U1")
      (value "PDS1-S5-S5-M-TR")
      (footprint "eagle-import:PDS1-M")
      (libsource (lib "eagle-import") (part "PDS1-M"))
    )
    (comp (ref "U2")
      (value "SN74LVC1G32DBV")
      (footprint "eagle-import:SOT23-5")
      (fields (field (name "PARTNO") "SN74LVC1G32DBVR"))
      (libsource (lib "eagle-import") (part "LL_OR{colon}SN74LVC1G32-Q1DBV"))
    )
    (comp (ref "U3")
      (value "SN74LVC1G08DBV")
      (footprint "eagle-import:SOT23-5")
      (fields (field (name "PARTNO") "SN74LVC1G08DBVR"))
      (libsource (lib "eagle-import") (part "LL_AND{colon}SN74LVC1G08DBV"))
    )
    (comp (ref "U4")
      (value "RM46L852")
      (footprint "eagle-import:LQFP144")
      (libsource (lib "eagle-import") (part "RM46L852"))
    )
    (comp (ref "U5")
      (value "CD4050BD")
      (footprint "eagle-import:SOIC-16")
      (fields (field (name "PARTNO") "CD4050BDR"))
      (libsource (lib "eagle-import") (part "CD4050BD"))
    )
    (comp (ref "U6")
      (value "CD4050BD")
      (footprint "eagle-import:SOIC-16")
      (fields (field (name "PARTNO") "CD4050BDR"))
      (libsource (lib "eagle-import") (part "CD4050BD"))
    )
    (comp (ref "U7")
      (value "MCP2562FD")
      (footprint "eagle-import:SOIC8-N_MC")
      (fields (field (name "PARTNO") "MCP2562FD-E/SN"))
      (libsource (lib "eagle-import") (part "MCP256X-SOIC"))
    )
    (comp (ref "U8")
      (value "ADUM3160BRWZ-RL")
      (footprint "eagle-import:ADUM3160")
      (libsource (lib "eagle-import") (part "ADUM3160"))
    )
    (comp (ref "U10")
      (value "ISO7221")
      (footprint "eagle-import:ISO722X")
      (fields (field (name "PARTNO") "ISO7221CDR"))
      (libsource (lib "eagle-import") (part "ISO7221"))
    )
    (comp (ref "U11")
      (value "ISO7221")
      (footprint "eagle-import:ISO722X")
      (fields (field (name "PARTNO") "ISO7221CDR"))
      (libsource (lib "eagle-import") (part "ISO7221"))
    )
    (comp (ref "U13")
      (value "MCP2562FD")
      (footprint "eagle-import:SOIC8-N_MC")
      (fields (field (name "PARTNO") "MCP2562FD-E/SN"))
      (libsource (lib "eagle-import") (part "MCP256X-SOIC"))
    )
    (comp (ref "U14")
      (value "SN74LVC541A")
      (footprint "eagle-import:TSSOP20_MC")
      (fields (field (name "PARTNO") "SN74LVC541APWR"))
      (libsource (lib "eagle-import") (part "SN74LVC541A"))
    )
    (comp (ref "U16")
      (value "LM3671MF-3.3/NOPB")
      (footprint "eagle-import:SOT23-5")
      (libsource (lib "eagle-import") (part "LM3671MF"))
    )
    (comp (ref "U17")
      (value "SN74LVC1G02DBV")
      (footprint "eagle-import:SOT23-5")
      (fields (field (name "PARTNO") "SN74LVC1G02DBVR"))
      (libsource (lib "eagle-import") (part "LL_NOR{colon}SN74LVC1G02DBV"))
    )
    (comp (ref "U18")
      (value "LM3671MF-1.2/NOPB")
      (footprint "eagle-import:SOT23-5")
      (libsource (lib "eagle-import") (part "LM3671MF"))
    )
    (comp (ref "U22")
      (value "FAN3214")
      (footprint "eagle-import:FAN3214")
      (fields (field (name "PARTNO") "FAN3214TMX"))
      (libsource (lib "eagle-import") (part "FAN3214"))
    )
    (comp (ref "U23")
      (value "FAN3214")
      (footprint "eagle-import:FAN3214")
      (fields (field (name "PARTNO") "FAN3214TMX"))
      (libsource (lib "eagle-import") (part "FAN3214"))
    )
    (comp (ref "U24")
      (value "CSD17506Q5A")
      (footprint "eagle-import:SON_5X6")
      (libsource (lib "eagle-import") (part "CSD17506Q5A"))
    )
    (comp (ref "U25")
      (value "CSD17506Q5A")
      (footprint "eagle-import:SON_5X6")
      (libsource (lib "eagle-import") (part "CSD17506Q5A"))
    )
    (comp (ref "U27")
      (value "CSD17506Q5A")
      (footprint "eagle-import:SON_5X6")
      (libsource (lib "eagle-import") (part "CSD17506Q5A"))
    )
    (comp (ref "U30")
      (value "ISO7221")
      (footprint "eagle-import:ISO722X")
      (fields (field (name "PARTNO") "ISO7221CDR"))
      (libsource (lib "eagle-import") (part "ISO7221"))
    )
    (comp (ref "U31")
      (value "ISO7221")
      (footprint "eagle-import:ISO722X")
      (fields (field (name "PARTNO") "ISO7221CDR"))
      (libsource (lib "eagle-import") (part "ISO7221"))
    )
    (comp (ref "U32")
      (value "PDS1-S5-S5-M-TR")
      (footprint "eagle-import:PDS1-M")
      (libsource (lib "eagle-import") (part "PDS1-M"))
    )
    (comp (ref "U33")
      (value "ISO7221")
      (footprint "eagle-import:ISO722X")
      (fields (field (name "PARTNO") "ISO7221CDR"))
      (libsource (lib "eagle-import") (part "ISO7221"))
    )
    (comp (ref "U34")
      (value "ISO7221")
      (footprint "eagle-import:ISO722X")
      (fields (field (name "PARTNO") "ISO7221CDR"))
      (libsource (lib "eagle-import") (part "ISO7221"))
    )
    (comp (ref "U35")
      (value "PDS1-S5-S5-M-TR")
      (footprint "eagle-import:PDS1-M")
      (libsource (lib "eagle-import") (part "PDS1-M"))
    )
    (comp (ref "U36")
      (value "ADC121S021")
      (footprint "eagle-import:ADC121S021")
      (fields (field (name "PARTNO") "ADC121S021CIMF/NOPB"))
      (libsource (lib "eagle-import") (part "ADC121S021"))
    )
    (comp (ref "U37")
      (value "ADC121S021")
      (footprint "eagle-import:ADC121S021")
      (fields (field (name "PARTNO") "ADC121S021CIMF/NOPB"))
      (libsource (lib "eagle-import") (part "ADC121S021"))
    )
    (comp (ref "U38")
      (value "FT232RL")
      (footprint "eagle-import:SSOP28")
      (fields (field (name "PARTNO") "FT232RL-REEL"))
      (libsource (lib "eagle-import") (part "FT232RL"))
    )
    (comp (ref "U42")
      (value "TPS54540DDARQ1")
      (footprint "eagle-import:TPS54540")
      (fields (field (name "PARTNO") "TPS54540DDAR"))
      (libsource (lib "eagle-import") (part "TPS54540"))
    )
    (comp (ref "Y2")
      (value "16MHz")
      (footprint "eagle-import:CSM-3X")
      (fields (field (name "PARTNO") "ECS-160-20-3X-TR"))
      (libsource (lib "eagle-import") (part "CSM-3X"))
    )
  )
  (nets
    (net (code "1") (name "+1V2") (class "Default")
      (node (ref "C33") (pin "1") (pinfunction "1_1") (pintype "passive"))
      (node (ref "C34") (pin "1") (pinfunction "1_1") (pintype "passive"))
      (node (ref "C35") (pin "1") (pinfunction "1_1") (pintype "passive"))
      (node (ref "C36") (pin "1") (pinfunction "1_1") (pintype "passive"))
      (node (ref "C37") (pin "1") (pinfunction "1_1") (pintype "passive"))
      (node (ref "C39") (pin "1") (pinfunction "1_1") (pintype "passive"))
      (node (ref "C41") (pin "1") (pinfunction "1_1") (pintype "passive"))
      (node (ref "C43") (pin "1") (pinfunction "1_1") (pintype "passive"))
      (node (ref "C47") (pin "1") (pinfunction "1_1") (pintype "passive"))
      (node (ref "C49") (pin "1") (pinfunction "1_1") (pintype "passive"))
      (node (ref "C53") (pin "1") (pinfunction "1_1") (pintype "passive"))
      (node (ref "C55") (pin "1") (pinfunction "1_1") (pintype "passive"))
      (node (ref "C72") (pin "1") (pinfunction "1_1") (pintype "passive"))
      (node (ref "L6") (pin "2") (pinfunction "P$2_2") (pintype "bidirectional"))
      (node (ref "U18") (pin "4") (pinfunction "FB_4") (pintype "bidirectional"))
      (node (ref "U4") (pin "101") (pinfunction "VCC_101") (pintype "power_in"))
      (node (ref "U4") (pin "114") (pinfunction "VCC_114") (pintype "power_in"))
      (node (ref "U4") (pin "123") (pinfunction "VCC_123") (pintype "power_in"))
      (node (ref "U4") (pin "137") (pinfunction "VCC_137") (pintype "power_in"))
      (node (ref "U4") (pin "143") (pinfunction "VCC_143") (pintype "power_in"))
      (node (ref "U4") (pin "17") (pinfunction "VCC_17") (pintype "power_in"))
      (node (ref "U4") (pin "29") (pinfunction "VCC_29") (pintype "power_in"))
      (node (ref "U4") (pin "45") (pinfunction "VCC_45") (pintype "power_in"))
      (node (ref "U4") (pin "48") (pinfunction "VCC_48") (pintype "power_in"))
      (node (ref "U4") (pin "49") (pinfunction "VCC_49") (pintype "power_in"))
      (node (ref "U4") (pin "57") (pinfunction "VCC_57") (pintype "power_in"))
      (node (ref "U4") (pin "87") (pinfunction "VCC_87") (pintype "power_in"))
    )
    (net (code "2") (name "+3V3") (class "Default")
      (node (ref "C1") (pin "1") (pinfunction "1_1") (pintype "passive"))
      (node (ref "C10") (pin "1") (pinfunction "1_1") (pintype "passive"))
      (node (ref "C13") (pin "1") (pinfunction "1_1") (pintype "passive"))
      (node (ref "C15") (pin "1") (pinfunction "1_1") (pintype "passive"))
      (node (ref "C16") (pin "1") (pinfunction "1_1") (pintype "passive"))
      (node (ref "C2") (pin "1") (pinfunction "1_1") (pintype "passive"))
      (node (ref "C21") (pin "1") (pinfunction "1_1") (pintype "passive"))
      (node (ref "C22") (pin "1") (pinfunction "1_1") (pintype "passive"))
      (node (ref "C23") (pin "1") (pinfunction "1_1") (pintype "passive"))
      (node (ref "C27") (pin "1") (pinfunction "1_1") (pintype "passive"))
      (node (ref "C38") (pin "1") (pinfunction "1_1") (pintype "passive"))
      (node (ref "C42") (pin "1") (pinfunction "1_1") (pintype "passive"))
      (node (ref "C46") (pin "1") (pinfunction "1_1") (pintype "passive"))
      (node (ref "C48") (pin "1") (pinfunction "1_1") (pintype "passive"))
      (node (ref "C54") (pin "1") (pinfunction "1_1") (pintype "passive"))
      (node (ref "C56") (pin "1") (pinfunction "1_1") (pintype "passive"))
      (node (ref "C7") (pin "1") (pinfunction "1_1") (pintype "passive"))
      (node (ref "C70") (pin "1") (pinfunction "1_1") (pintype "passive"))
      (node (ref "C75") (pin "1") (pinfunction "1_1") (pintype "passive"))
      (node (ref "C76") (pin "1") (pinfunction "1_1") (pintype "passive"))
      (node (ref "C77") (pin "1") (pinfunction "1_1") (pintype "passive"))
      (node (ref "C78") (pin "1") (pinfunction "1_1") (pintype "passive"))
      (node (ref "H6") (pin "3") (pinfunction "3_3") (pintype "bidirectional"))
      (node (ref "H7") (pin "3") (pinfunction "3_3") (pintype "bidirectional"))
      (node (ref "J1") (pin "5") (pinfunction "5_5") (pintype "bidirectional"))
      (node (ref "JP5") (pin "6") (pinfunction "6_6") (pintype "passive"))
      (node (ref "L4") (pin "1") (pinfunction "1_1") (pintype "passive"))
      (node (ref "L5") (pin "2") (pinfunction "P$2_2") (pintype "bidirectional"))
      (node (ref "LED11") (pin "A") (pinfunction "A_A") (pintype "passive"))
      (node (ref "LED12") (pin "A") (pinfunction "A_A") (pintype "passive"))
      (node (ref "LED13") (pin "A") (pinfunction "A_A") (pintype "passive"))
      (node (ref "LED2") (pin "A") (pinfunction "A_A") (pintype "passive"))
      (node (ref "LED5") (pin "A") (pinfunction "A_A") (pintype "passive"))
      (node (ref "Q2") (pin "G") (pinfunction "G_G") (pintype "bidirectional"))
      (node (ref "Q3") (pin "G") (pinfunction "G_G") (pintype "bidirectional"))
      (node (ref "Q4") (pin "G") (pinfunction "G_G") (pintype "bidirectional"))
      (node (ref "Q5") (pin "G") (pinfunction "G_G") (pintype "bidirectional"))
      (node (ref "Q6") (pin "G") (pinfunction "G_G") (pintype "bidirectional"))
      (node (ref "R21") (pin "1") (pinfunction "1_1") (pintype "passive"))
      (node (ref "R22") (pin "1") (pinfunction "1_1") (pintype "passive"))
      (node (ref "R32") (pin "1") (pinfunction "1_1") (pintype "passive"))
      (node (ref "R35") (pin "1") (pinfunction "1_1") (pintype "passive"))
      (node (ref "U10") (pin "P$8") (pinfunction "VCC2_P$8") (pintype "bidirectional"))
      (node (ref "U11") (pin "P$8") (pinfunction "VCC2_P$8") (pintype "bidirectional"))
      (node (ref "U14") (pin "20") (pinfunction "VCC_20") (pintype "power_in"))
      (node (ref "U16") (pin "4") (pinfunction "FB_4") (pintype "bidirectional"))
      (node (ref "U17") (pin "5") (pinfunction "VCC_5") (pintype "power_in"))
      (node (ref "U2") (pin "5") (pinfunction "VCC_5") (pintype "power_in"))
      (node (ref "U3") (pin "5") (pinfunction "VCC_5") (pintype "power_in"))
      (node (ref "U30") (pin "P$8") (pinfunction "VCC2_P$8") (pintype "bidirectional"))
      (node (ref "U31") (pin "P$8") (pinfunction "VCC2_P$8") (pintype "bidirectional"))
      (node (ref "U33") (pin "P$8") (pinfunction "VCC2_P$8") (pintype "bidirectional"))
      (node (ref "U34") (pin "P$8") (pinfunction "VCC2_P$8") (pintype "bidirectional"))
      (node (ref "U38") (pin "19") (pinfunction "~{RESET}_19") (pintype "input"))
      (node (ref "U38") (pin "4") (pinfunction "VCCIO_4") (pintype "power_in"))
      (node (ref "U4") (pin "10") (pinfunction "VCCIO_10") (pintype "power_in"))
      (node (ref "U4") (pin "104") (pinfunction "VCCIO_104") (pintype "power_in"))
      (node (ref "U4") (pin "120") (pinfunction "VCCIO_120") (pintype "power_in"))
      (node (ref "U4") (pin "134") (pinfunction "VCCP_134") (pintype "power_in"))
      (node (ref "U4") (pin "136") (pinfunction "VCCIO_136") (pintype "power_in"))
      (node (ref "U4") (pin "26") (pinfunction "VCCIO_26") (pintype "power_in"))
      (node (ref "U4") (pin "42") (pinfunction "VCCIO_42") (pintype "power_in"))
      (node (ref "U4") (pin "69") (pinfunction "VCCAD_69") (pintype "power_in"))
      (node (ref "U5") (pin "1") (pinfunction "VCC_1") (pintype "power_in"))
      (node (ref "U7") (pin "5") (pinfunction "SPLIT/VIO_5") (pintype "bidirectional"))
      (node (ref "U8") (pin "12") (pinfunction "PIN_12") (pintype "bidirectional"))
      (node (ref "U8") (pin "13") (pinfunction "SPD_13") (pintype "bidirectional"))
      (node (ref "U8") (pin "14") (pinfunction "VDD2_14") (pintype "bidirectional"))
      (node (ref "U8") (pin "16") (pinfunction "VBUS2_16") (pintype "bidirectional"))
    )
    (net (code "3") (name "+5V") (class "Default")
      (node (ref "C100") (pin "1") (pinfunction "1_1") (pintype "passive"))
      (node (ref "C11") (pin "1") (pinfunction "1_1") (pintype "passive"))
      (node (ref "C12") (pin "1") (pinfunction "1_1") (pintype "passive"))
      (node (ref "C14") (pin "1") (pinfunction "1_1") (pintype "passive"))
      (node (ref "C40") (pin "1") (pinfunction "1_1") (pintype "passive"))
      (node (ref "C6") (pin "1") (pinfunction "1_1") (pintype "passive"))
      (node (ref "C71") (pin "1") (pinfunction "1_1") (pintype "passive"))
      (node (ref "C79") (pin "1") (pinfunction "1_1") (pintype "passive"))
      (node (ref "C80") (pin "1") (pinfunction "1_1") (pintype "passive"))
      (node (ref "C98") (pin "1") (pinfunction "1_1") (pintype "passive"))
      (node (ref "C99") (pin "1") (pinfunction "1_1") (pintype "passive"))
      (node (ref "JP5") (pin "7") (pinfunction "7_7") (pintype "passive"))
      (node (ref "L1") (pin "P$2") (pinfunction "P$2_P$2") (pintype "bidirectional"))
      (node (ref "LED3") (pin "A") (pinfunction "A_A") (pintype "passive"))
      (node (ref "R50") (pin "2") (pinfunction "2_2") (pintype "passive"))
      (node (ref "U1") (pin "2") (pinfunction "VIN_2") (pintype "bidirectional"))
      (node (ref "U16") (pin "1") (pinfunction "VIN_1") (pintype "bidirectional"))
      (node (ref "U16") (pin "3") (pinfunction "EN_3") (pintype "bidirectional"))
      (node (ref "U18") (pin "1") (pinfunction "VIN_1") (pintype "bidirectional"))
      (node (ref "U18") (pin "3") (pinfunction "EN_3") (pintype "bidirectional"))
      (node (ref "U32") (pin "2") (pinfunction "VIN_2") (pintype "bidirectional"))
      (node (ref "U35") (pin "2") (pinfunction "VIN_2") (pintype "bidirectional"))
      (node (ref "U38") (pin "20") (pinfunction "VCC_20") (pintype "power_in"))
      (node (ref "U7") (pin "3") (pinfunction "VDD_3") (pintype "power_in"))
    )
    (net (code "4") (name "+5V{slash}1") (class "Default")
      (node (ref "C17") (pin "1") (pinfunction "1_1") (pintype "passive"))
      (node (ref "C18") (pin "1") (pinfunction "1_1") (pintype "passive"))
      (node (ref "C19") (pin "1") (pinfunction "1_1") (pintype "passive"))
      (node (ref "C20") (pin "1") (pinfunction "1_1") (pintype "passive"))
      (node (ref "C28") (pin "1") (pinfunction "1_1") (pintype "passive"))
      (node (ref "J7") (pin "4") (pinfunction "4_4") (pintype "bidirectional"))
      (node (ref "LED16") (pin "A") (pinfunction "A_A") (pintype "passive"))
      (node (ref "U1") (pin "5") (pinfunction "+VO_5") (pintype "bidirectional"))
      (node (ref "U10") (pin "P$1") (pinfunction "VCC1_P$1") (pintype "bidirectional"))
      (node (ref "U11") (pin "P$1") (pinfunction "VCC1_P$1") (pintype "bidirectional"))
      (node (ref "U13") (pin "3") (pinfunction "VDD_3") (pintype "power_in"))
      (node (ref "U13") (pin "5") (pinfunction "SPLIT/VIO_5") (pintype "bidirectional"))
    )
    (net (code "5") (name "+5V{slash}2") (class "Default")
      (node (ref "C81") (pin "1") (pinfunction "1_1") (pintype "passive"))
      (node (ref "C87") (pin "1") (pinfunction "1_1") (pintype "passive"))
      (node (ref "C88") (pin "1") (pinfunction "1_1") (pintype "passive"))
      (node (ref "C91") (pin "1") (pinfunction "1_1") (pintype "passive"))
      (node (ref "LED15") (pin "A") (pinfunction "A_A") (pintype "passive"))
      (node (ref "U30") (pin "P$1") (pinfunction "VCC1_P$1") (pintype "bidirectional"))
      (node (ref "U31") (pin "P$1") (pinfunction "VCC1_P$1") (pintype "bidirectional"))
      (node (ref "U31") (pin "P$3") (pinfunction "INB_P$3") (pintype "bidirectional"))
      (node (ref "U32") (pin "5") (pinfunction "+VO_5") (pintype "bidirectional"))
      (node (ref "U36") (pin "P$1") (pinfunction "VA_P$1") (pintype "bidirectional"))
    )
    (net (code "6") (name "+5V{slash}3") (class "Default")
      (node (ref "C5") (pin "1") (pinfunction "1_1") (pintype "passive"))
      (node (ref "C89") (pin "1") (pinfunction "1_1") (pintype "passive"))
      (node (ref "C90") (pin "1") (pinfunction "1_1") (pintype "passive"))
      (node (ref "C92") (pin "1") (pinfunction "1_1") (pintype "passive"))
      (node (ref "LED14") (pin "A") (pinfunction "A_A") (pintype "passive"))
      (node (ref "U33") (pin "P$1") (pinfunction "VCC1_P$1") (pintype "bidirectional"))
      (node (ref "U34") (pin "P$1") (pinfunction "VCC1_P$1") (pintype "bidirectional"))
      (node (ref "U34") (pin "P$3") (pinfunction "INB_P$3") (pintype "bidirectional"))
      (node (ref "U35") (pin "5") (pinfunction "+VO_5") (pintype "bidirectional"))
      (node (ref "U37") (pin "P$1") (pinfunction "VA_P$1") (pintype "bidirectional"))
    )
    (net (code "7") (name "+15V") (class "Default")
      (node (ref "C24") (pin "1") (pinfunction "1_1") (pintype "passive"))
      (node (ref "C25") (pin "1") (pinfunction "1_1") (pintype "passive"))
      (node (ref "C26") (pin "1") (pinfunction "1_1") (pintype "passive"))
      (node (ref "C96") (pin "1") (pinfunction "1_1") (pintype "passive"))
      (node (ref "C97") (pin "1") (pinfunction "1_1") (pintype "passive"))
      (node (ref "D1") (pin "CATHODE") (pinfunction "CATHODE_CATHODE") (pintype "bidirectional"))
      (node (ref "H4") (pin "2") (pinfunction "2_2") (pintype "bidirectional"))
      (node (ref "JP12") (pin "3") (pinfunction "P$3_3") (pintype "bidirectional"))
      (node (ref "JP5") (pin "8") (pinfunction "8_8") (pintype "passive"))
      (node (ref "Q1") (pin "S") (pinfunction "S_S") (pintype "bidirectional"))
      (node (ref "R17") (pin "1") (pinfunction "1_1") (pintype "passive"))
      (node (ref "R18") (pin "1") (pinfunction "1_1") (pintype "passive"))
      (node (ref "R19") (pin "1") (pinfunction "1_1") (pintype "passive"))
      (node (ref "R23") (pin "1") (pinfunction "1_1") (pintype "passive"))
      (node (ref "R4") (pin "1") (pinfunction "1_1") (pintype "passive"))
      (node (ref "R52") (pin "2") (pinfunction "2_2") (pintype "passive"))
      (node (ref "R72") (pin "1") (pinfunction "1_1") (pintype "passive"))
      (node (ref "U22") (pin "6") (pinfunction "VCC_6") (pintype "power_in"))
      (node (ref "U23") (pin "6") (pinfunction "VCC_6") (pintype "power_in"))
      (node (ref "U42") (pin "2") (pinfunction "VIN_2") (pintype "bidirectional"))
      (node (ref "U6") (pin "1") (pinfunction "VCC_1") (pintype "power_in"))
    )
    (net (code "8") (name "/5KW_3V3") (class "Default")
      (node (ref "JP5") (pin "3") (pinfunction "3_3") (pintype "passive"))
      (node (ref "Q5") (pin "S") (pinfunction "S_S") (pintype "bidirectional"))
      (node (ref "R11") (pin "1") (pinfunction "1_1") (pintype "passive"))
      (node (ref "U14") (pin "2") (pinfunction "IN_2") (pintype "input"))
      (node (ref "U4") (pin "133") (pinfunction "GIOB[1]/USB1.PORTPOWER_133") (pintype "bidirectional"))
    )
    (net (code "9") (name "/5KW_GLV") (class "Default")
      (node (ref "D6") (pin "CATHODE") (pinfunction "CATHODE_CATHODE") (pintype "bidirectional"))
      (node (ref "J2") (pin "P$1") (pinfunction "P1_P$1") (pintype "bidirectional"))
      (node (ref "R16") (pin "2") (pinfunction "2_2") (pintype "passive"))
    )
    (net (code "10") (name "/BATTERY_VOLTAGE_FB") (class "Default")
      (node (ref "R101") (pin "2") (pinfunction "2_2") (pintype "passive"))
      (node (ref "R102") (pin "1") (pinfunction "1_1") (pintype "passive"))
      (node (ref "R96") (pin "1") (pinfunction "1_1") (pintype "passive"))
    )
    (net (code "11") (name "/BATTERY_VOLTAGE_IS_AVAILABLE") (class "Default")
      (node (ref "U34") (pin "P$6") (pinfunction "OUTB_P$6") (pintype "bidirectional"))
      (node (ref "U4") (pin "40") (pinfunction "MIBSPI1NCS[2]/N2HET1[19]/MDIO_40") (pintype "bidirectional"))
    )
    (net (code "12") (name "/BATTERY_VOLTAGE_MONITOR_CS") (class "Default")
      (node (ref "U33") (pin "P$7") (pinfunction "INA_P$7") (pintype "bidirectional"))
      (node (ref "U4") (pin "130") (pinfunction "MIBSPI1NCS[1]/N2HET1[17]/MII_COL/USB1.SUSPEND/EQEP1S_130") (pintype "bidirectional"))
    )
    (net (code "13") (name "/BMS_CAN_RX") (class "Default")
      (node (ref "JP7") (pin "3") (pinfunction "P$3_3") (pintype "bidirectional"))
      (node (ref "U4") (pin "129") (pinfunction "CAN2RX_129") (pintype "bidirectional"))
    )
    (net (code "14") (name "/BMS_CAN_TX") (class "Default")
      (node (ref "JP6") (pin "3") (pinfunction "P$3_3") (pintype "bidirectional"))
      (node (ref "U4") (pin "128") (pinfunction "CAN2TX_128") (pintype "bidirectional"))
    )
    (net (code "15") (name "/BMS_FAULT") (class "Default")
      (node (ref "U11") (pin "P$6") (pinfunction "OUTB_P$6") (pintype "bidirectional"))
      (node (ref "U4") (pin "2") (pinfunction "GIOA[0]/USB2.VP/USB_FUNC.RXDPI_2") (pintype "bidirectional"))
    )
    (net (code "16") (name "/BMS_FAULT_HV") (class "Default")
      (node (ref "J7") (pin "5") (pinfunction "5_5") (pintype "bidirectional"))
      (node (ref "U11") (pin "P$3") (pinfunction "INB_P$3") (pintype "bidirectional"))
    )
    (net (code "17") (name "/BMS_RX") (class "Default")
      (node (ref "JP7") (pin "2") (pinfunction "P$2_2") (pintype "bidirectional"))
      (node (ref "U10") (pin "P$6") (pinfunction "OUTB_P$6") (pintype "bidirectional"))
    )
    (net (code "18") (name "/BMS_RX_HV") (class "Default")
      (node (ref "J7") (pin "2") (pinfunction "2_2") (pintype "bidirectional"))
      (node (ref "JP3") (pin "2") (pinfunction "P$2_2") (pintype "bidirectional"))
    )
    (net (code "19") (name "/BMS_TX") (class "Default")
      (node (ref "JP6") (pin "2") (pinfunction "P$2_2") (pintype "bidirectional"))
      (node (ref "U11") (pin "P$7") (pinfunction "INA_P$7") (pintype "bidirectional"))
    )
    (net (code "20") (name "/BMS_TX_HV") (class "Default")
      (node (ref "J7") (pin "3") (pinfunction "3_3") (pintype "bidirectional"))
      (node (ref "JP4") (pin "2") (pinfunction "P$2_2") (pintype "bidirectional"))
    )
    (net (code "21") (name "/BMS_UART_RX") (class "Default")
      (node (ref "JP7") (pin "1") (pinfunction "P$1_1") (pintype "bidirectional"))
      (node (ref "U4") (pin "38") (pinfunction "N2HET1[6]/SCIRX/EPWM5A_38") (pintype "bidirectional"))
    )
    (net (code "22") (name "/BMS_UART_TX") (class "Default")
      (node (ref "JP6") (pin "1") (pinfunction "P$1_1") (pintype "bidirectional"))
      (node (ref "U4") (pin "39") (pinfunction "N2HET1[13]/SCITX/EPWM5B_39") (pintype "bidirectional"))
    )
    (net (code "23") (name "/CAR_CAN_N") (class "Default")
      (node (ref "J2") (pin "P$7") (pinfunction "P7_P$7") (pintype "bidirectional"))
      (node (ref "R2") (pin "1") (pinfunction "1_1") (pintype "passive"))
      (node (ref "U7") (pin "6") (pinfunction "CANL_6") (pintype "bidirectional"))
    )
    (net (code "24") (name "/CAR_CAN_P") (class "Default")
      (node (ref "J2") (pin "P$8") (pinfunction "P8_P$8") (pintype "bidirectional"))
      (node (ref "R2") (pin "2") (pinfunction "2_2") (pintype "passive"))
      (node (ref "U7") (pin "7") (pinfunction "CANH_7") (pintype "bidirectional"))
    )
    (net (code "25") (name "/CAR_CAN_RX") (class "Default")
      (node (ref "U4") (pin "90") (pinfunction "CAN1RX_90") (pintype "bidirectional"))
      (node (ref "U7") (pin "4") (pinfunction "RXD_4") (pintype "bidirectional"))
    )
    (net (code "26") (name "/CAR_CAN_TX") (class "Default")
      (node (ref "U4") (pin "89") (pinfunction "CAN1TX_89") (pintype "bidirectional"))
      (node (ref "U7") (pin "1") (pinfunction "TXD_1") (pintype "bidirectional"))
    )
    (net (code "27") (name "/CONTACTOR_CLOSED_3V3") (class "Default")
      (node (ref "Q4") (pin "S") (pinfunction "S_S") (pintype "bidirectional"))
      (node (ref "R22") (pin "2") (pinfunction "2_2") (pintype "passive"))
      (node (ref "U17") (pin "4") (pinfunction "OUT_4") (pintype "output"))
      (node (ref "U4") (pin "22") (pinfunction "GIOA[7]/N2HET2[6]/EPWM2A_22") (pintype "bidirectional"))
    )
    (net (code "28") (name "/CONTACTOR_CLOSED_GLV") (class "Default")
      (node (ref "D4") (pin "CATHODE") (pinfunction "CATHODE_CATHODE") (pintype "bidirectional"))
      (node (ref "J2") (pin "P$6") (pinfunction "P6_P$6") (pintype "bidirectional"))
      (node (ref "R14") (pin "2") (pinfunction "2_2") (pintype "passive"))
    )
    (net (code "29") (name "/CONTACTOR_OPEN_3V3") (class "Default")
      (node (ref "Q3") (pin "S") (pinfunction "S_S") (pintype "bidirectional"))
      (node (ref "R21") (pin "2") (pinfunction "2_2") (pintype "passive"))
      (node (ref "U3") (pin "4") (pinfunction "OUT_4") (pintype "output"))
      (node (ref "U4") (pin "16") (pinfunction "GIOA[6]/N2HET2[4]/EPWM1B_16") (pintype "bidirectional"))
    )
    (net (code "30") (name "/CONTACTOR_OPEN_GLV") (class "Default")
      (node (ref "D3") (pin "CATHODE") (pinfunction "CATHODE_CATHODE") (pintype "bidirectional"))
      (node (ref "J2") (pin "P$5") (pinfunction "P5_P$5") (pintype "bidirectional"))
      (node (ref "R13") (pin "2") (pinfunction "2_2") (pintype "passive"))
    )
    (net (code "31") (name "/CURRENT_SENSE_-75_TO_75A") (class "Default")
      (node (ref "JP5") (pin "4") (pinfunction "4_4") (pintype "passive"))
      (node (ref "U4") (pin "73") (pinfunction "AD1IN[2]_73") (pintype "input"))
    )
    (net (code "32") (name "/CURRENT_SENSE_-750_TO_750A") (class "Default")
      (node (ref "JP5") (pin "5") (pinfunction "5_5") (pintype "passive"))
      (node (ref "U4") (pin "74") (pinfunction "AD1IN[3]_74") (pintype "input"))
    )
    (net (code "33") (name "/CURRENT_SHORT_3V3") (class "Default")
      (node (ref "JP5") (pin "2") (pinfunction "2_2") (pintype "passive"))
      (node (ref "Q6") (pin "S") (pinfunction "S_S") (pintype "bidirectional"))
      (node (ref "R24") (pin "1") (pinfunction "1_1") (pintype "passive"))
      (node (ref "U4") (pin "142") (pinfunction "GIOB[2]_142") (pintype "bidirectional"))
    )
    (net (code "34") (name "/CURRENT_SHORT_GLV") (class "Default")
      (node (ref "D8") (pin "CATHODE") (pinfunction "CATHODE_CATHODE") (pintype "bidirectional"))
      (node (ref "J2") (pin "P$9") (pinfunction "P9_P$9") (pintype "bidirectional"))
      (node (ref "R25") (pin "2") (pinfunction "2_2") (pintype "passive"))
    )
    (net (code "35") (name "/FAULT_AMS_GLV") (class "Default")
      (node (ref "D2") (pin "CATHODE") (pinfunction "CATHODE_CATHODE") (pintype "bidirectional"))
      (node (ref "J2") (pin "P$3") (pinfunction "P3_P$3") (pintype "bidirectional"))
      (node (ref "R12") (pin "2") (pinfunction "2_2") (pintype "passive"))
    )
    (net (code "36") (name "/FAULT_AMS_INDICATOR") (class "Default")
      (node (ref "Q2") (pin "S") (pinfunction "S_S") (pintype "bidirectional"))
      (node (ref "R20") (pin "2") (pinfunction "2_2") (pintype "passive"))
      (node (ref "U14") (pin "3") (pinfunction "IN_3") (pintype "input"))
      (node (ref "U4") (pin "126") (pinfunction "GIOB[0]/USB1.TXDAT_126") (pintype "bidirectional"))
    )
    (net (code "37") (name "/FAULT_IMD_3V3") (class "Default")
      (node (ref "U14") (pin "9") (pinfunction "IN_9") (pintype "input"))
      (node (ref "U4") (pin "14") (pinfunction "GIOA[5]/EXTCLKIN/EPWM1A/N2HET1_PIN_NDIS_14") (pintype "bidirectional"))
      (node (ref "U5") (pin "4") (pinfunction "OUT_4") (pintype "output"))
    )
    (net (code "38") (name "/FAULT_IMD_GLV") (class "Default")
      (node (ref "D5") (pin "CATHODE") (pinfunction "CATHODE_CATHODE") (pintype "bidirectional"))
      (node (ref "J2") (pin "P$2") (pinfunction "P2_P$2") (pintype "bidirectional"))
      (node (ref "R15") (pin "2") (pinfunction "2_2") (pintype "passive"))
    )
    (net (code "39") (name "/FAULT_IMD_PRE-BUFFER") (class "Default")
      (node (ref "H4") (pin "8") (pinfunction "8_8") (pintype "bidirectional"))
      (node (ref "R81") (pin "1") (pinfunction "1_1") (pintype "passive"))
      (node (ref "U5") (pin "5") (pinfunction "IN_5") (pintype "input"))
      (node (ref "U6") (pin "14") (pinfunction "IN_14") (pintype "input"))
    )
    (net (code "40") (name "/FILTERED_BATTERY_VOLTAGE_FB") (class "Default")
      (node (ref "C93") (pin "1") (pinfunction "1_1") (pintype "passive"))
      (node (ref "R96") (pin "2") (pinfunction "2_2") (pintype "passive"))
      (node (ref "U36") (pin "P$3") (pinfunction "VIN_P$3") (pintype "bidirectional"))
    )
    (net (code "41") (name "/FILTERED_VEHICLE_VOLTAGE_FB") (class "Default")
      (node (ref "C3") (pin "1") (pinfunction "1_1") (pintype "passive"))
      (node (ref "R97") (pin "2") (pinfunction "2_2") (pintype "passive"))
      (node (ref "U37") (pin "P$3") (pinfunction "VIN_P$3") (pintype "bidirectional"))
    )
    (net (code "42") (name "/HV_BMS_CAN_N") (class "Default")
      (node (ref "JP3") (pin "3") (pinfunction "P$3_3") (pintype "bidirectional"))
      (node (ref "R1") (pin "1") (pinfunction "1_1") (pintype "passive"))
      (node (ref "U13") (pin "6") (pinfunction "CANL_6") (pintype "bidirectional"))
    )
    (net (code "43") (name "/HV_BMS_CAN_P") (class "Default")
      (node (ref "JP4") (pin "3") (pinfunction "P$3_3") (pintype "bidirectional"))
      (node (ref "R1") (pin "2") (pinfunction "2_2") (pintype "passive"))
      (node (ref "U13") (pin "7") (pinfunction "CANH_7") (pintype "bidirectional"))
    )
    (net (code "44") (name "/HV_BMS_CAN_RX") (class "Default")
      (node (ref "JP1") (pin "3") (pinfunction "P$3_3") (pintype "bidirectional"))
      (node (ref "U13") (pin "4") (pinfunction "RXD_4") (pintype "bidirectional"))
    )
    (net (code "45") (name "/HV_BMS_CAN_TX") (class "Default")
      (node (ref "JP2") (pin "3") (pinfunction "P$3_3") (pintype "bidirectional"))
      (node (ref "U13") (pin "1") (pinfunction "TXD_1") (pintype "bidirectional"))
    )
    (net (code "46") (name "/IMD_GND") (class "Default")
      (node (ref "H4") (pin "4") (pinfunction "4_4") (pintype "bidirectional"))
      (node (ref "J2") (pin "P$4") (pinfunction "P4_P$4") (pintype "bidirectional"))
    )
    (net (code "47") (name "/IMD_PWM_OUT_3V3") (class "Default")
      (node (ref "U4") (pin "30") (pinfunction "N2HET1[2]/SPI4SIMO[0]/EPWM3A_30") (pintype "bidirectional"))
      (node (ref "U5") (pin "6") (pinfunction "OUT_6") (pintype "output"))
    )
    (net (code "48") (name "/INDICATOR_1") (class "Default")
      (node (ref "U14") (pin "8") (pinfunction "IN_8") (pintype "input"))
      (node (ref "U4") (pin "125") (pinfunction "N2HET1[14]/USB1.TXSE0_125") (pintype "bidirectional"))
    )
    (net (code "49") (name "/INDICATOR_2") (class "Default")
      (node (ref "U14") (pin "7") (pinfunction "IN_7") (pintype "input"))
      (node (ref "U4") (pin "124") (pinfunction "N2HET1[12]/MII_CRS/RMII_CRS_DV_124") (pintype "bidirectional"))
    )
    (net (code "50") (name "/JTAG_RESET") (class "Default")
      (node (ref "J1") (pin "15") (pinfunction "15_15") (pintype "bidirectional"))
      (node (ref "U4") (pin "46") (pinfunction "NPORRST_46") (pintype "input"))
    )
    (net (code "51") (name "/M_LS") (class "Default")
      (node (ref "H4") (pin "6") (pinfunction "6_6") (pintype "bidirectional"))
      (node (ref "R72") (pin "2") (pinfunction "2_2") (pintype "passive"))
      (node (ref "U5") (pin "7") (pinfunction "IN_7") (pintype "input"))
    )
    (net (code "52") (name "/NEGATIVE_CONTACTOR_CTRL") (class "Default")
      (node (ref "U14") (pin "5") (pinfunction "IN_5") (pintype "input"))
      (node (ref "U22") (pin "4") (pinfunction "IN_4") (pintype "input"))
      (node (ref "U4") (pin "140") (pinfunction "N2HET1[18]/EPWM6A_140") (pintype "bidirectional"))
    )
    (net (code "53") (name "/NEG_CONTACTOR_SENSE") (class "Default")
      (node (ref "H7") (pin "4") (pinfunction "4_4") (pintype "bidirectional"))
      (node (ref "R63") (pin "2") (pinfunction "2_2") (pintype "passive"))
      (node (ref "R65") (pin "2") (pinfunction "2_2") (pintype "passive"))
    )
    (net (code "54") (name "/NEG_CONTACTOR_SENSE_FILTERED") (class "Default")
      (node (ref "C65") (pin "1") (pinfunction "1_1") (pintype "passive"))
      (node (ref "R63") (pin "1") (pinfunction "1_1") (pintype "passive"))
      (node (ref "U17") (pin "1") (pinfunction "IN1_1") (pintype "input"))
      (node (ref "U3") (pin "1") (pinfunction "IN1_1") (pintype "input"))
      (node (ref "U4") (pin "5") (pinfunction "GIOA[1]/USB2.VM/USB_FUNC.RXDMI_5") (pintype "bidirectional"))
    )
    (net (code "55") (name "/NTRST") (class "Default")
      (node (ref "J1") (pin "2") (pinfunction "2_2") (pintype "bidirectional"))
      (node (ref "U4") (pin "109") (pinfunction "NTRST_109") (pintype "input"))
    )
    (net (code "56") (name "/POSITIVE_CONTACTOR_CTRL") (class "Default")
      (node (ref "U14") (pin "6") (pinfunction "IN_6") (pintype "input"))
      (node (ref "U22") (pin "2") (pinfunction "IN_2") (pintype "input"))
      (node (ref "U4") (pin "141") (pinfunction "N2HET1[20]/EPWM6B_141") (pintype "bidirectional"))
    )
    (net (code "57") (name "/POS_CONTACTOR_SENSE") (class "Default")
      (node (ref "H6") (pin "4") (pinfunction "4_4") (pintype "bidirectional"))
      (node (ref "R62") (pin "2") (pinfunction "2_2") (pintype "passive"))
      (node (ref "R64") (pin "2") (pinfunction "2_2") (pintype "passive"))
    )
    (net (code "58") (name "/POS_CONTACTOR_SENSE_FILTERED") (class "Default")
      (node (ref "C64") (pin "1") (pinfunction "1_1") (pintype "passive"))
      (node (ref "R62") (pin "1") (pinfunction "1_1") (pintype "passive"))
      (node (ref "U2") (pin "1") (pinfunction "IN1_1") (pintype "input"))
      (node (ref "U4") (pin "9") (pinfunction "GIOA[2]/USB2.TXDAT/USB_FUNC.TXDO/N2HET2[0]/EQEP2I_9") (pintype "bidirectional"))
    )
    (net (code "59") (name "/PRECHARGE_CONTACTOR_CTRL") (class "Default")
      (node (ref "U14") (pin "4") (pinfunction "IN_4") (pintype "input"))
      (node (ref "U2") (pin "2") (pinfunction "IN2_2") (pintype "input"))
      (node (ref "U23") (pin "2") (pinfunction "IN_2") (pintype "input"))
      (node (ref "U4") (pin "139") (pinfunction "N2HET1[16]/EPWM1SYNCI/EPWM1SYNCO_139") (pintype "bidirectional"))
    )
    (net (code "60") (name "/RTCK") (class "Default")
      (node (ref "J1") (pin "9") (pinfunction "9_9") (pintype "bidirectional"))
      (node (ref "U4") (pin "113") (pinfunction "RTCK_113") (pintype "output"))
    )
    (net (code "61") (name "/SC_FROM_OUTSIDE_SENSE") (class "Default")
      (node (ref "U4") (pin "36") (pinfunction "N2HET1[4]/EPWM4B_36") (pintype "bidirectional"))
      (node (ref "U4") (pin "37") (pinfunction "MIBSPI3NCS[1]/N2HET1[25]/MDCLK_37") (pintype "bidirectional"))
      (node (ref "U5") (pin "2") (pinfunction "OUT_2") (pintype "output"))
    )
    (net (code "62") (name "/SHUTDOWN_CIRCUIT_FROM_OUTSIDE") (class "Default")
      (node (ref "D13") (pin "ANODE") (pinfunction "ANODE_ANODE") (pintype "bidirectional"))
      (node (ref "D17") (pin "1") (pinfunction "CATHODE_1") (pintype "bidirectional"))
      (node (ref "H1") (pin "1") (pinfunction "1_1") (pintype "bidirectional"))
      (node (ref "H6") (pin "1") (pinfunction "1_1") (pintype "bidirectional"))
      (node (ref "H7") (pin "1") (pinfunction "1_1") (pintype "bidirectional"))
      (node (ref "J2") (pin "P$23") (pinfunction "P23_P$23") (pintype "bidirectional"))
    )
    (net (code "63") (name "/TCK") (class "Default")
      (node (ref "J1") (pin "11") (pinfunction "11_11") (pintype "bidirectional"))
      (node (ref "U4") (pin "112") (pinfunction "TCK_112") (pintype "input"))
    )
    (net (code "64") (name "/TDI") (class "Default")
      (node (ref "J1") (pin "3") (pinfunction "3_3") (pintype "bidirectional"))
      (node (ref "U4") (pin "110") (pinfunction "TDI_110") (pintype "input"))
    )
    (net (code "65") (name "/TDO") (class "Default")
      (node (ref "J1") (pin "7") (pinfunction "7_7") (pintype "bidirectional"))
      (node (ref "U4") (pin "111") (pinfunction "TDO_111") (pintype "output"))
    )
    (net (code "66") (name "/TMS") (class "Default")
      (node (ref "J1") (pin "1") (pinfunction "1_1") (pintype "bidirectional"))
      (node (ref "U4") (pin "108") (pinfunction "TMS_108") (pintype "input"))
    )
    (net (code "67") (name "/UART_RX") (class "Default")
      (node (ref "U38") (pin "1") (pinfunction "TXD_1") (pintype "output"))
      (node (ref "U4") (pin "131") (pinfunction "LINRX_131") (pintype "bidirectional"))
    )
    (net (code "68") (name "/UART_TX") (class "Default")
      (node (ref "U38") (pin "5") (pinfunction "RXD_5") (pintype "input"))
      (node (ref "U4") (pin "132") (pinfunction "LINTX_132") (pintype "bidirectional"))
    )
    (net (code "69") (name "/USBISO_D_N") (class "Default")
      (node (ref "J3") (pin "2") (pinfunction "D-_2") (pintype "bidirectional"))
      (node (ref "R9") (pin "1") (pinfunction "1_1") (pintype "passive"))
    )
    (net (code "70") (name "/USBISO_D_P") (class "Default")
      (node (ref "J3") (pin "3") (pinfunction "D+_3") (pintype "bidirectional"))
      (node (ref "R10") (pin "1") (pinfunction "1_1") (pintype "passive"))
    )
    (net (code "71") (name "/USBISO_GND") (class "Default")
      (node (ref "C8") (pin "2") (pinfunction "2_2") (pintype "passive"))
      (node (ref "C9") (pin "2") (pinfunction "2_2") (pintype "passive"))
      (node (ref "J3") (pin "4") (pinfunction "GND_4") (pintype "bidirectional"))
      (node (ref "U8") (pin "2") (pinfunction "GND1_2") (pintype "bidirectional"))
      (node (ref "U8") (pin "8") (pinfunction "GND1_8") (pintype "bidirectional"))
    )
    (net (code "72") (name "/USBISO_VCC") (class "Default")
      (node (ref "C8") (pin "1") (pinfunction "1_1") (pintype "passive"))
      (node (ref "J3") (pin "1") (pinfunction "VCC_1") (pintype "bidirectional"))
      (node (ref "U8") (pin "1") (pinfunction "VBUS1_1") (pintype "bidirectional"))
    )
    (net (code "73") (name "/VEHICLE_VOLTAGE_FB") (class "Default")
      (node (ref "R106") (pin "2") (pinfunction "2_2") (pintype "passive"))
      (node (ref "R107") (pin "1") (pinfunction "1_1") (pintype "passive"))
      (node (ref "R97") (pin "1") (pinfunction "1_1") (pintype "passive"))
    )
    (net (code "74") (name "/VEHICLE_VOLTAGE_IS_AVAILABLE") (class "Default")
      (node (ref "U31") (pin "P$6") (pinfunction "OUTB_P$6") (pintype "bidirectional"))
      (node (ref "U4") (pin "93") (pinfunction "MIBSPI1SIMO[0]_93") (pintype "bidirectional"))
    )
    (net (code "75") (name "/VEHICLE_VOLTAGE_MONITOR_CS") (class "Default")
      (node (ref "U30") (pin "P$7") (pinfunction "INA_P$7") (pintype "bidirectional"))
      (node (ref "U4") (pin "105") (pinfunction "MIBSPI1NCS[0]/MIBSPI1SOMI[1]/MII_TXD[2]/USB1.RCV/ECAP6_105") (pintype "bidirectional"))
    )
    (net (code "76") (name "/VOLTAGE_MONITOR_MISO") (class "Default")
      (node (ref "U30") (pin "P$6") (pinfunction "OUTB_P$6") (pintype "bidirectional"))
      (node (ref "U33") (pin "P$6") (pinfunction "OUTB_P$6") (pintype "bidirectional"))
      (node (ref "U4") (pin "94") (pinfunction "MIBSPI1SOMI[0]_94") (pintype "bidirectional"))
    )
    (net (code "77") (name "/VOLTAGE_MONITOR_SCLK") (class "Default")
      (node (ref "U31") (pin "P$7") (pinfunction "INA_P$7") (pintype "bidirectional"))
      (node (ref "U34") (pin "P$7") (pinfunction "INA_P$7") (pintype "bidirectional"))
      (node (ref "U4") (pin "95") (pinfunction "MIBSPI1CLK_95") (pintype "bidirectional"))
    )
    (net (code "78") (name "/WAKEUP") (class "Default")
      (node (ref "U10") (pin "P$7") (pinfunction "INA_P$7") (pintype "bidirectional"))
      (node (ref "U4") (pin "1") (pinfunction "GIOB[3]/USB2.RCV/USB_FUNC.RXDI_1") (pintype "bidirectional"))
    )
    (net (code "79") (name "/WAKEUP_HV") (class "Default")
      (node (ref "J7") (pin "1") (pinfunction "1_1") (pintype "bidirectional"))
      (node (ref "U10") (pin "P$2") (pinfunction "OUTA_P$2") (pintype "bidirectional"))
    )
    (net (code "80") (name "GND") (class "Default")
      (node (ref "C1") (pin "2") (pinfunction "2_2") (pintype "passive"))
      (node (ref "C10") (pin "2") (pinfunction "2_2") (pintype "passive"))
      (node (ref "C100") (pin "2") (pinfunction "2_2") (pintype "passive"))
      (node (ref "C11") (pin "2") (pinfunction "2_2") (pintype "passive"))
      (node (ref "C12") (pin "2") (pinfunction "2_2") (pintype "passive"))
      (node (ref "C13") (pin "2") (pinfunction "2_2") (pintype "passive"))
      (node (ref "C14") (pin "2") (pinfunction "2_2") (pintype "passive"))
      (node (ref "C15") (pin "2") (pinfunction "2_2") (pintype "passive"))
      (node (ref "C16") (pin "2") (pinfunction "2_2") (pintype "passive"))
      (node (ref "C2") (pin "2") (pinfunction "2_2") (pintype "passive"))
      (node (ref "C21") (pin "2") (pinfunction "2_2") (pintype "passive"))
      (node (ref "C22") (pin "2") (pinfunction "2_2") (pintype "passive"))
      (node (ref "C23") (pin "2") (pinfunction "2_2") (pintype "passive"))
      (node (ref "C24") (pin "2") (pinfunction "2_2") (pintype "passive"))
      (node (ref "C25") (pin "2") (pinfunction "2_2") (pintype "passive"))
      (node (ref "C26") (pin "2") (pinfunction "2_2") (pintype "passive"))
      (node (ref "C27") (pin "2") (pinfunction "2_2") (pintype "passive"))
      (node (ref "C31") (pin "2") (pinfunction "2_2") (pintype "passive"))
      (node (ref "C32") (pin "2") (pinfunction "2_2") (pintype "passive"))
      (node (ref "C33") (pin "2") (pinfunction "2_2") (pintype "passive"))
      (node (ref "C34") (pin "2") (pinfunction "2_2") (pintype "passive"))
      (node (ref "C35") (pin "2") (pinfunction "2_2") (pintype "passive"))
      (node (ref "C36") (pin "2") (pinfunction "2_2") (pintype "passive"))
      (node (ref "C37") (pin "2") (pinfunction "2_2") (pintype "passive"))
      (node (ref "C38") (pin "2") (pinfunction "2_2") (pintype "passive"))
      (node (ref "C39") (pin "2") (pinfunction "2_2") (pintype "passive"))
      (node (ref "C4") (pin "2") (pinfunction "2_2") (pintype "passive"))
      (node (ref "C40") (pin "2") (pinfunction "2_2") (pintype "passive"))
      (node (ref "C41") (pin "2") (pinfunction "2_2") (pintype "passive"))
      (node (ref "C42") (pin "2") (pinfunction "2_2") (pintype "passive"))
      (node (ref "C43") (pin "2") (pinfunction "2_2") (pintype "passive"))
      (node (ref "C46") (pin "2") (pinfunction "2_2") (pintype "passive"))
      (node (ref "C47") (pin "2") (pinfunction "2_2") (pintype "passive"))
      (node (ref "C48") (pin "2") (pinfunction "2_2") (pintype "passive"))
      (node (ref "C49") (pin "2") (pinfunction "2_2") (pintype "passive"))
      (node (ref "C52") (pin "2") (pinfunction "2_2") (pintype "passive"))
      (node (ref "C53") (pin "2") (pinfunction "2_2") (pintype "passive"))
      (node (ref "C54") (pin "2") (pinfunction "2_2") (pintype "passive"))
      (node (ref "C55") (pin "2") (pinfunction "2_2") (pintype "passive"))
      (node (ref "C56") (pin "2") (pinfunction "2_2") (pintype "passive"))
      (node (ref "C6") (pin "2") (pinfunction "2_2") (pintype "passive"))
      (node (ref "C64") (pin "2") (pinfunction "2_2") (pintype "passive"))
      (node (ref "C65") (pin "2") (pinfunction "2_2") (pintype "passive"))
      (node (ref "C7") (pin "2") (pinfunction "2_2") (pintype "passive"))
      (node (ref "C70") (pin "2") (pinfunction "2_2") (pintype "passive"))
      (node (ref "C71") (pin "2") (pinfunction "2_2") (pintype "passive"))
      (node (ref "C72") (pin "2") (pinfunction "2_2") (pintype "passive"))
      (node (ref "C75") (pin "2") (pinfunction "2_2") (pintype "passive"))
      (node (ref "C76") (pin "2") (pinfunction "2_2") (pintype "passive"))
      (node (ref "C77") (pin "2") (pinfunction "2_2") (pintype "passive"))
      (node (ref "C78") (pin "2") (pinfunction "2_2") (pintype "passive"))
      (node (ref "C79") (pin "2") (pinfunction "2_2") (pintype "passive"))
      (node (ref "C80") (pin "2") (pinfunction "2_2") (pintype "passive"))
      (node (ref "C82") (pin "2") (pinfunction "2_2") (pintype "passive"))
      (node (ref "C94") (pin "2") (pinfunction "2_2") (pintype "passive"))
      (node (ref "C96") (pin "2") (pinfunction "2_2") (pintype "passive"))
      (node (ref "C97") (pin "2") (pinfunction "2_2") (pintype "passive"))
      (node (ref "C98") (pin "2") (pinfunction "2_2") (pintype "passive"))
      (node (ref "C99") (pin "2") (pinfunction "2_2") (pintype "passive"))
      (node (ref "D11") (pin "ANODE") (pinfunction "ANODE_ANODE") (pintype "bidirectional"))
      (node (ref "D7") (pin "1") (pinfunction "ANODE_1") (pintype "bidirectional"))
      (node (ref "D7") (pin "3") (pinfunction "ANODE_3") (pintype "bidirectional"))
      (node (ref "H4") (pin "1") (pinfunction "1_1") (pintype "bidirectional"))
      (node (ref "H4") (pin "3") (pinfunction "3_3") (pintype "bidirectional"))
      (node (ref "J1") (pin "10") (pinfunction "10_10") (pintype "bidirectional"))
      (node (ref "J1") (pin "12") (pinfunction "12_12") (pintype "bidirectional"))
      (node (ref "J1") (pin "16") (pinfunction "16_16") (pintype "bidirectional"))
      (node (ref "J1") (pin "20") (pinfunction "20_20") (pintype "bidirectional"))
      (node (ref "J1") (pin "4") (pinfunction "4_4") (pintype "bidirectional"))
      (node (ref "J1") (pin "8") (pinfunction "8_8") (pintype "bidirectional"))
      (node (ref "J2") (pin "P$21") (pinfunction "P21_P$21") (pintype "bidirectional"))
      (node (ref "JP12") (pin "1") (pinfunction "P$1_1") (pintype "bidirectional"))
      (node (ref "JP5") (pin "1") (pinfunction "1_1") (pintype "passive"))
      (node (ref "LED1") (pin "C") (pinfunction "C_C") (pintype "passive"))
      (node (ref "LED10") (pin "C") (pinfunction "C_C") (pintype "passive"))
      (node (ref "LED6") (pin "C") (pinfunction "C_C") (pintype "passive"))
      (node (ref "LED7") (pin "C") (pinfunction "C_C") (pintype "passive"))
      (node (ref "LED8") (pin "C") (pinfunction "C_C") (pintype "passive"))
      (node (ref "LED9") (pin "C") (pinfunction "C_C") (pintype "passive"))
      (node (ref "MP1") (pin "P$1") (pinfunction "P$1_P$1") (pintype "bidirectional"))
      (node (ref "MP2") (pin "P$1") (pinfunction "P$1_P$1") (pintype "bidirectional"))
      (node (ref "R11") (pin "2") (pinfunction "2_2") (pintype "passive"))
      (node (ref "R12") (pin "1") (pinfunction "1_1") (pintype "passive"))
      (node (ref "R13") (pin "1") (pinfunction "1_1") (pintype "passive"))
      (node (ref "R14") (pin "1") (pinfunction "1_1") (pintype "passive"))
      (node (ref "R15") (pin "1") (pinfunction "1_1") (pintype "passive"))
      (node (ref "R16") (pin "1") (pinfunction "1_1") (pintype "passive"))
      (node (ref "R20") (pin "1") (pinfunction "1_1") (pintype "passive"))
      (node (ref "R24") (pin "2") (pinfunction "2_2") (pintype "passive"))
      (node (ref "R25") (pin "1") (pinfunction "1_1") (pintype "passive"))
      (node (ref "R30") (pin "1") (pinfunction "1_1") (pintype "passive"))
      (node (ref "R36") (pin "1") (pinfunction "1_1") (pintype "passive"))
      (node (ref "R47") (pin "1") (pinfunction "1_1") (pintype "passive"))
      (node (ref "R5") (pin "1") (pinfunction "1_1") (pintype "passive"))
      (node (ref "R51") (pin "1") (pinfunction "1_1") (pintype "passive"))
      (node (ref "R53") (pin "1") (pinfunction "1_1") (pintype "passive"))
      (node (ref "R64") (pin "1") (pinfunction "1_1") (pintype "passive"))
      (node (ref "R65") (pin "1") (pinfunction "1_1") (pintype "passive"))
      (node (ref "R81") (pin "2") (pinfunction "2_2") (pintype "passive"))
      (node (ref "S2") (pin "P$2") (pinfunction "2_P$2") (pintype "bidirectional"))
      (node (ref "U1") (pin "1") (pinfunction "GND_1") (pintype "bidirectional"))
      (node (ref "U10") (pin "P$5") (pinfunction "GND2_P$5") (pintype "bidirectional"))
      (node (ref "U11") (pin "P$5") (pinfunction "GND2_P$5") (pintype "bidirectional"))
      (node (ref "U14") (pin "1") (pinfunction "~{E}_1") (pintype "input"))
      (node (ref "U14") (pin "10") (pinfunction "GND_10") (pintype "power_in"))
      (node (ref "U14") (pin "19") (pinfunction "~{E}_19") (pintype "input"))
      (node (ref "U16") (pin "2") (pinfunction "GND_2") (pintype "bidirectional"))
      (node (ref "U17") (pin "3") (pinfunction "GND_3") (pintype "power_in"))
      (node (ref "U18") (pin "2") (pinfunction "GND_2") (pintype "bidirectional"))
      (node (ref "U2") (pin "3") (pinfunction "GND_3") (pintype "power_in"))
      (node (ref "U22") (pin "3") (pinfunction "GND_3") (pintype "power_in"))
      (node (ref "U23") (pin "3") (pinfunction "GND_3") (pintype "power_in"))
      (node (ref "U24") (pin "1") (pinfunction "S_1") (pintype "bidirectional"))
      (node (ref "U24") (pin "2") (pinfunction "S_2") (pintype "bidirectional"))
      (node (ref "U24") (pin "3") (pinfunction "S_3") (pintype "bidirectional"))
      (node (ref "U25") (pin "1") (pinfunction "S_1") (pintype "bidirectional"))
      (node (ref "U25") (pin "2") (pinfunction "S_2") (pintype "bidirectional"))
      (node (ref "U25") (pin "3") (pinfunction "S_3") (pintype "bidirectional"))
      (node (ref "U27") (pin "1") (pinfunction "S_1") (pintype "bidirectional"))
      (node (ref "U27") (pin "2") (pinfunction "S_2") (pintype "bidirectional"))
      (node (ref "U27") (pin "3") (pinfunction "S_3") (pintype "bidirectional"))
      (node (ref "U3") (pin "3") (pinfunction "GND_3") (pintype "power_in"))
      (node (ref "U30") (pin "P$5") (pinfunction "GND2_P$5") (pintype "bidirectional"))
      (node (ref "U31") (pin "P$5") (pinfunction "GND2_P$5") (pintype "bidirectional"))
      (node (ref "U32") (pin "1") (pinfunction "GND_1") (pintype "bidirectional"))
      (node (ref "U33") (pin "P$5") (pinfunction "GND2_P$5") (pintype "bidirectional"))
      (node (ref "U34") (pin "P$5") (pinfunction "GND2_P$5") (pintype "bidirectional"))
      (node (ref "U35") (pin "1") (pinfunction "GND_1") (pintype "bidirectional"))
      (node (ref "U38") (pin "18") (pinfunction "GND_18") (pintype "power_in"))
      (node (ref "U38") (pin "21") (pinfunction "GND_21") (pintype "power_in"))
      (node (ref "U38") (pin "25") (pinfunction "GND_25") (pintype "power_in"))
      (node (ref "U38") (pin "26") (pinfunction "TEST_26") (pintype "input"))
      (node (ref "U38") (pin "7") (pinfunction "GND_7") (pintype "power_in"))
      (node (ref "U4") (pin "102") (pinfunction "VSS_102") (pintype "power_in"))
      (node (ref "U4") (pin "103") (pinfunction "VSS_103") (pintype "power_in"))
      (node (ref "U4") (pin "11") (pinfunction "VSS_11") (pintype "power_in"))
      (node (ref "U4") (pin "115") (pinfunction "VSS_115") (pintype "power_in"))
      (node (ref "U4") (pin "121") (pinfunction "VSS_121") (pintype "power_in"))
      (node (ref "U4") (pin "122") (pinfunction "VSS_122") (pintype "power_in"))
      (node (ref "U4") (pin "135") (pinfunction "VSS_135") (pintype "power_in"))
      (node (ref "U4") (pin "138") (pinfunction "VSS_138") (pintype "power_in"))
      (node (ref "U4") (pin "144") (pinfunction "VSS_144") (pintype "power_in"))
      (node (ref "U4") (pin "21") (pinfunction "VSS_21") (pintype "power_in"))
      (node (ref "U4") (pin "27") (pinfunction "VSS_27") (pintype "power_in"))
      (node (ref "U4") (pin "28") (pinfunction "VSS_28") (pintype "power_in"))
      (node (ref "U4") (pin "34") (pinfunction "TEST_34") (pintype "input"))
      (node (ref "U4") (pin "43") (pinfunction "VSS_43") (pintype "power_in"))
      (node (ref "U4") (pin "44") (pinfunction "VSS_44") (pintype "power_in"))
      (node (ref "U4") (pin "47") (pinfunction "VSS_47") (pintype "power_in"))
      (node (ref "U4") (pin "50") (pinfunction "VSS_50") (pintype "power_in"))
      (node (ref "U4") (pin "56") (pinfunction "VSS_56") (pintype "power_in"))
      (node (ref "U4") (pin "67") (pinfunction "ADREFLO_67") (pintype "power_in"))
      (node (ref "U4") (pin "68") (pinfunction "VSSAD_68") (pintype "power_in"))
      (node (ref "U4") (pin "88") (pinfunction "VSS_88") (pintype "power_in"))
      (node (ref "U42") (pin "7") (pinfunction "GND_7") (pintype "bidirectional"))
      (node (ref "U42") (pin "PAD") (pinfunction "GND_PAD") (pintype "bidirectional"))
      (node (ref "U42") (pin "PAD1") (pinfunction "GND_PAD1") (pintype "bidirectional"))
      (node (ref "U5") (pin "8") (pinfunction "GND_8") (pintype "power_in"))
      (node (ref "U6") (pin "8") (pinfunction "GND_8") (pintype "power_in"))
      (node (ref "U7") (pin "2") (pinfunction "VSS_2") (pintype "power_in"))
      (node (ref "U7") (pin "8") (pinfunction "STBY_8") (pintype "input"))
      (node (ref "U8") (pin "15") (pinfunction "GND2_15") (pintype "bidirectional"))
      (node (ref "U8") (pin "9") (pinfunction "GND2_9") (pintype "bidirectional"))
    )
    (net (code "81") (name "GND1") (class "Default")
      (node (ref "C17") (pin "2") (pinfunction "2_2") (pintype "passive"))
      (node (ref "C18") (pin "2") (pinfunction "2_2") (pintype "passive"))
      (node (ref "C19") (pin "2") (pinfunction "2_2") (pintype "passive"))
      (node (ref "C20") (pin "2") (pinfunction "2_2") (pintype "passive"))
      (node (ref "C28") (pin "2") (pinfunction "2_2") (pintype "passive"))
      (node (ref "J7") (pin "6") (pinfunction "6_6") (pintype "bidirectional"))
      (node (ref "R28") (pin "1") (pinfunction "1_1") (pintype "passive"))
      (node (ref "U1") (pin "4") (pinfunction "0V_4") (pintype "bidirectional"))
      (node (ref "U10") (pin "P$4") (pinfunction "GND1_P$4") (pintype "bidirectional"))
      (node (ref "U11") (pin "P$4") (pinfunction "GND1_P$4") (pintype "bidirectional"))
      (node (ref "U13") (pin "2") (pinfunction "VSS_2") (pintype "power_in"))
      (node (ref "U13") (pin "8") (pinfunction "STBY_8") (pintype "input"))
    )
    (net (code "82") (name "GND2") (class "Default")
      (node (ref "C81") (pin "2") (pinfunction "2_2") (pintype "passive"))
      (node (ref "C87") (pin "2") (pinfunction "2_2") (pintype "passive"))
      (node (ref "C88") (pin "2") (pinfunction "2_2") (pintype "passive"))
      (node (ref "C91") (pin "2") (pinfunction "2_2") (pintype "passive"))
      (node (ref "C93") (pin "2") (pinfunction "2_2") (pintype "passive"))
      (node (ref "J4") (pin "3") (pinfunction "3_3") (pintype "bidirectional"))
      (node (ref "J4") (pin "4") (pinfunction "4_4") (pintype "bidirectional"))
      (node (ref "R102") (pin "2") (pinfunction "2_2") (pintype "passive"))
      (node (ref "R108") (pin "1") (pinfunction "1_1") (pintype "passive"))
      (node (ref "R27") (pin "1") (pinfunction "1_1") (pintype "passive"))
      (node (ref "U30") (pin "P$4") (pinfunction "GND1_P$4") (pintype "bidirectional"))
      (node (ref "U31") (pin "P$4") (pinfunction "GND1_P$4") (pintype "bidirectional"))
      (node (ref "U32") (pin "4") (pinfunction "0V_4") (pintype "bidirectional"))
      (node (ref "U36") (pin "P$2") (pinfunction "GND_P$2") (pintype "bidirectional"))
    )
    (net (code "83") (name "GND3") (class "Default")
      (node (ref "C3") (pin "2") (pinfunction "2_2") (pintype "passive"))
      (node (ref "C5") (pin "2") (pinfunction "2_2") (pintype "passive"))
      (node (ref "C89") (pin "2") (pinfunction "2_2") (pintype "passive"))
      (node (ref "C90") (pin "2") (pinfunction "2_2") (pintype "passive"))
      (node (ref "C92") (pin "2") (pinfunction "2_2") (pintype "passive"))
      (node (ref "J6") (pin "3") (pinfunction "3_3") (pintype "bidirectional"))
      (node (ref "J6") (pin "4") (pinfunction "4_4") (pintype "bidirectional"))
      (node (ref "R107") (pin "2") (pinfunction "2_2") (pintype "passive"))
      (node (ref "R109") (pin "1") (pinfunction "1_1") (pintype "passive"))
      (node (ref "R26") (pin "1") (pinfunction "1_1") (pintype "passive"))
      (node (ref "U33") (pin "P$4") (pinfunction "GND1_P$4") (pintype "bidirectional"))
      (node (ref "U34") (pin "P$4") (pinfunction "GND1_P$4") (pintype "bidirectional"))
      (node (ref "U35") (pin "4") (pinfunction "0V_4") (pintype "bidirectional"))
      (node (ref "U37") (pin "P$2") (pinfunction "GND_P$2") (pintype "bidirectional"))
    )
    (net (code "84") (name "Net-(C82-Pad1)") (class "Default")
      (node (ref "C82") (pin "1") (pinfunction "1_1") (pintype "passive"))
      (node (ref "R48") (pin "1") (pinfunction "1_1") (pintype "passive"))
    )
    (net (code "85") (name "Net-(D1-PadANODE)") (class "Default")
      (node (ref "D1") (pin "ANODE") (pinfunction "ANODE_ANODE") (pintype "bidirectional"))
      (node (ref "Q1") (pin "G") (pinfunction "G_G") (pintype "bidirectional"))
      (node (ref "R5") (pin "2") (pinfunction "2_2") (pintype "passive"))
    )
    (net (code "86") (name "Net-(D7-CATHODE)") (class "Default")
      (node (ref "C95") (pin "2") (pinfunction "2_2") (pintype "passive"))
      (node (ref "D7") (pin "2") (pinfunction "CATHODE_2") (pintype "bidirectional"))
      (node (ref "L1") (pin "P$1") (pinfunction "P$1_P$1") (pintype "bidirectional"))
      (node (ref "U42") (pin "8") (pinfunction "SW_8") (pintype "bidirectional"))
    )
    (net (code "87") (name "Net-(D17-ANODE)") (class "Default")
      (node (ref "D17") (pin "2") (pinfunction "ANODE_2") (pintype "bidirectional"))
      (node (ref "H1") (pin "2") (pinfunction "2_2") (pintype "bidirectional"))
      (node (ref "U27") (pin "5") (pinfunction "D_5") (pintype "bidirectional"))
      (node (ref "U27") (pin "6") (pinfunction "D_6") (pintype "bidirectional"))
      (node (ref "U27") (pin "7") (pinfunction "D_7") (pintype "bidirectional"))
      (node (ref "U27") (pin "8") (pinfunction "D_8") (pintype "bidirectional"))
      (node (ref "U27") (pin "PAD") (pinfunction "D_PAD") (pintype "bidirectional"))
      (node (ref "U27") (pin "PAD1") (pinfunction "D_PAD1") (pintype "bidirectional"))
      (node (ref "U27") (pin "VIA1") (pinfunction "D_VIA1") (pintype "bidirectional"))
      (node (ref "U27") (pin "VIA2") (pinfunction "D_VIA2") (pintype "bidirectional"))
      (node (ref "U27") (pin "VIA3") (pinfunction "D_VIA3") (pintype "bidirectional"))
      (node (ref "U27") (pin "VIA4") (pinfunction "D_VIA4") (pintype "bidirectional"))
      (node (ref "U27") (pin "VIA5") (pinfunction "D_VIA5") (pintype "bidirectional"))
      (node (ref "U27") (pin "VIA6") (pinfunction "D_VIA6") (pintype "bidirectional"))
      (node (ref "U27") (pin "VIA7") (pinfunction "D_VIA7") (pintype "bidirectional"))
      (node (ref "U27") (pin "VIA8") (pinfunction "D_VIA8") (pintype "bidirectional"))
      (node (ref "U27") (pin "VIA9") (pinfunction "D_VIA9") (pintype "bidirectional"))
    )
    (net (code "88") (name "Net-(D18-ANODE)") (class "Default")
      (node (ref "D18") (pin "2") (pinfunction "ANODE_2") (pintype "bidirectional"))
      (node (ref "Q7") (pin "G") (pinfunction "G_G") (pintype "bidirectional"))
      (node (ref "R108") (pin "2") (pinfunction "2_2") (pintype "passive"))
    )
    (net (code "89") (name "Net-(D18-CATHODE)") (class "Default")
      (node (ref "D18") (pin "1") (pinfunction "CATHODE_1") (pintype "bidirectional"))
      (node (ref "Q7") (pin "S") (pinfunction "S_S") (pintype "bidirectional"))
      (node (ref "R29") (pin "1") (pinfunction "1_1") (pintype "passive"))
    )
    (net (code "90") (name "Net-(D19-ANODE)") (class "Default")
      (node (ref "D19") (pin "2") (pinfunction "ANODE_2") (pintype "bidirectional"))
      (node (ref "Q8") (pin "G") (pinfunction "G_G") (pintype "bidirectional"))
      (node (ref "R109") (pin "2") (pinfunction "2_2") (pintype "passive"))
    )
    (net (code "91") (name "Net-(D19-CATHODE)") (class "Default")
      (node (ref "D19") (pin "1") (pinfunction "CATHODE_1") (pintype "bidirectional"))
      (node (ref "Q8") (pin "S") (pinfunction "S_S") (pintype "bidirectional"))
      (node (ref "R33") (pin "1") (pinfunction "1_1") (pintype "passive"))
    )
    (net (code "92") (name "Net-(F1-PadP$1)") (class "Default")
      (node (ref "F1") (pin "P$1") (pinfunction "P$1_P$1") (pintype "bidirectional"))
      (node (ref "Q1") (pin "D") (pinfunction "D_D") (pintype "bidirectional"))
    )
    (net (code "93") (name "Net-(F2-PadP$1)") (class "Default")
      (node (ref "F2") (pin "P$1") (pinfunction "P$1_P$1") (pintype "bidirectional"))
      (node (ref "J4") (pin "1") (pinfunction "1_1") (pintype "bidirectional"))
      (node (ref "J4") (pin "2") (pinfunction "2_2") (pintype "bidirectional"))
    )
    (net (code "94") (name "Net-(F2-PadP$2)") (class "Default")
      (node (ref "F2") (pin "P$2") (pinfunction "P$2_P$2") (pintype "bidirectional"))
      (node (ref "Q7") (pin "D") (pinfunction "D_D") (pintype "bidirectional"))
    )
    (net (code "95") (name "Net-(F3-PadP$1)") (class "Default")
      (node (ref "F3") (pin "P$1") (pinfunction "P$1_P$1") (pintype "bidirectional"))
      (node (ref "J6") (pin "1") (pinfunction "1_1") (pintype "bidirectional"))
    )
    (net (code "96") (name "Net-(F3-PadP$2)") (class "Default")
      (node (ref "F3") (pin "P$2") (pinfunction "P$2_P$2") (pintype "bidirectional"))
      (node (ref "J6") (pin "2") (pinfunction "2_2") (pintype "bidirectional"))
      (node (ref "Q8") (pin "D") (pinfunction "D_D") (pintype "bidirectional"))
    )
    (net (code "97") (name "Net-(H6-Pad2)") (class "Default")
      (node (ref "H6") (pin "2") (pinfunction "2_2") (pintype "bidirectional"))
      (node (ref "U24") (pin "5") (pinfunction "D_5") (pintype "bidirectional"))
      (node (ref "U24") (pin "6") (pinfunction "D_6") (pintype "bidirectional"))
      (node (ref "U24") (pin "7") (pinfunction "D_7") (pintype "bidirectional"))
      (node (ref "U24") (pin "8") (pinfunction "D_8") (pintype "bidirectional"))
      (node (ref "U24") (pin "PAD") (pinfunction "D_PAD") (pintype "bidirectional"))
      (node (ref "U24") (pin "PAD1") (pinfunction "D_PAD1") (pintype "bidirectional"))
      (node (ref "U24") (pin "VIA1") (pinfunction "D_VIA1") (pintype "bidirectional"))
      (node (ref "U24") (pin "VIA2") (pinfunction "D_VIA2") (pintype "bidirectional"))
      (node (ref "U24") (pin "VIA3") (pinfunction "D_VIA3") (pintype "bidirectional"))
      (node (ref "U24") (pin "VIA4") (pinfunction "D_VIA4") (pintype "bidirectional"))
      (node (ref "U24") (pin "VIA5") (pinfunction "D_VIA5") (pintype "bidirectional"))
      (node (ref "U24") (pin "VIA6") (pinfunction "D_VIA6") (pintype "bidirectional"))
      (node (ref "U24") (pin "VIA7") (pinfunction "D_VIA7") (pintype "bidirectional"))
      (node (ref "U24") (pin "VIA8") (pinfunction "D_VIA8") (pintype "bidirectional"))
      (node (ref "U24") (pin "VIA9") (pinfunction "D_VIA9") (pintype "bidirectional"))
    )
    (net (code "98") (name "Net-(H7-Pad2)") (class "Default")
      (node (ref "H7") (pin "2") (pinfunction "2_2") (pintype "bidirectional"))
      (node (ref "U25") (pin "5") (pinfunction "D_5") (pintype "bidirectional"))
      (node (ref "U25") (pin "6") (pinfunction "D_6") (pintype "bidirectional"))
      (node (ref "U25") (pin "7") (pinfunction "D_7") (pintype "bidirectional"))
      (node (ref "U25") (pin "8") (pinfunction "D_8") (pintype "bidirectional"))
      (node (ref "U25") (pin "PAD") (pinfunction "D_PAD") (pintype "bidirectional"))
      (node (ref "U25") (pin "PAD1") (pinfunction "D_PAD1") (pintype "bidirectional"))
      (node (ref "U25") (pin "VIA1") (pinfunction "D_VIA1") (pintype "bidirectional"))
      (node (ref "U25") (pin "VIA2") (pinfunction "D_VIA2") (pintype "bidirectional"))
      (node (ref "U25") (pin "VIA3") (pinfunction "D_VIA3") (pintype "bidirectional"))
      (node (ref "U25") (pin "VIA4") (pinfunction "D_VIA4") (pintype "bidirectional"))
      (node (ref "U25") (pin "VIA5") (pinfunction "D_VIA5") (pintype "bidirectional"))
      (node (ref "U25") (pin "VIA6") (pinfunction "D_VIA6") (pintype "bidirectional"))
      (node (ref "U25") (pin "VIA7") (pinfunction "D_VIA7") (pintype "bidirectional"))
      (node (ref "U25") (pin "VIA8") (pinfunction "D_VIA8") (pintype "bidirectional"))
      (node (ref "U25") (pin "VIA9") (pinfunction "D_VIA9") (pintype "bidirectional"))
    )
    (net (code "99") (name "Net-(J2-P16)") (class "Default")
      (node (ref "F1") (pin "P$2") (pinfunction "P$2_P$2") (pintype "bidirectional"))
      (node (ref "J2") (pin "P$16") (pinfunction "P16_P$16") (pintype "bidirectional"))
    )
    (net (code "100") (name "Net-(JP1-P$1)") (class "Default")
      (node (ref "JP1") (pin "1") (pinfunction "P$1_1") (pintype "bidirectional"))
      (node (ref "JP3") (pin "1") (pinfunction "P$1_1") (pintype "bidirectional"))
    )
    (net (code "101") (name "Net-(JP1-P$2)") (class "Default")
      (node (ref "JP1") (pin "2") (pinfunction "P$2_2") (pintype "bidirectional"))
      (node (ref "U10") (pin "P$3") (pinfunction "INB_P$3") (pintype "bidirectional"))
    )
    (net (code "102") (name "Net-(JP2-P$1)") (class "Default")
      (node (ref "JP2") (pin "1") (pinfunction "P$1_1") (pintype "bidirectional"))
      (node (ref "JP4") (pin "1") (pinfunction "P$1_1") (pintype "bidirectional"))
    )
    (net (code "103") (name "Net-(JP2-P$2)") (class "Default")
      (node (ref "JP2") (pin "2") (pinfunction "P$2_2") (pintype "bidirectional"))
      (node (ref "U11") (pin "P$2") (pinfunction "OUTA_P$2") (pintype "bidirectional"))
    )
    (net (code "104") (name "Net-(JP12-P$2)") (class "Default")
      (node (ref "D13") (pin "CATHODE") (pinfunction "CATHODE_CATHODE") (pintype "bidirectional"))
      (node (ref "JP12") (pin "2") (pinfunction "P$2_2") (pintype "bidirectional"))
      (node (ref "R57") (pin "1") (pinfunction "1_1") (pintype "passive"))
    )
    (net (code "105") (name "Net-(L5-P$1)") (class "Default")
      (node (ref "L5") (pin "1") (pinfunction "P$1_1") (pintype "bidirectional"))
      (node (ref "U16") (pin "5") (pinfunction "SW_5") (pintype "bidirectional"))
    )
    (net (code "106") (name "Net-(L6-P$1)") (class "Default")
      (node (ref "L6") (pin "1") (pinfunction "P$1_1") (pintype "bidirectional"))
      (node (ref "U18") (pin "5") (pinfunction "SW_5") (pintype "bidirectional"))
    )
    (net (code "107") (name "Net-(LED1-PadA)") (class "Default")
      (node (ref "LED1") (pin "A") (pinfunction "A_A") (pintype "passive"))
      (node (ref "R6") (pin "2") (pinfunction "2_2") (pintype "passive"))
    )
    (net (code "108") (name "Net-(LED2-PadC)") (class "Default")
      (node (ref "LED2") (pin "C") (pinfunction "C_C") (pintype "passive"))
      (node (ref "R36") (pin "2") (pinfunction "2_2") (pintype "passive"))
    )
    (net (code "109") (name "Net-(LED3-PadC)") (class "Default")
      (node (ref "LED3") (pin "C") (pinfunction "C_C") (pintype "passive"))
      (node (ref "R30") (pin "2") (pinfunction "2_2") (pintype "passive"))
    )
    (net (code "110") (name "Net-(LED4-PadA)") (class "Default")
      (node (ref "LED4") (pin "A") (pinfunction "A_A") (pintype "passive"))
      (node (ref "R35") (pin "2") (pinfunction "2_2") (pintype "passive"))
    )
    (net (code "111") (name "Net-(LED5-PadC)") (class "Default")
      (node (ref "LED5") (pin "C") (pinfunction "C_C") (pintype "passive"))
      (node (ref "R7") (pin "2") (pinfunction "2_2") (pintype "passive"))
    )
    (net (code "112") (name "Net-(LED6-PadA)") (class "Default")
      (node (ref "LED6") (pin "A") (pinfunction "A_A") (pintype "passive"))
      (node (ref "R41") (pin "2") (pinfunction "2_2") (pintype "passive"))
    )
    (net (code "113") (name "Net-(LED7-PadA)") (class "Default")
      (node (ref "LED7") (pin "A") (pinfunction "A_A") (pintype "passive"))
      (node (ref "R42") (pin "2") (pinfunction "2_2") (pintype "passive"))
    )
    (net (code "114") (name "Net-(LED8-PadA)") (class "Default")
      (node (ref "LED8") (pin "A") (pinfunction "A_A") (pintype "passive"))
      (node (ref "R43") (pin "2") (pinfunction "2_2") (pintype "passive"))
    )
    (net (code "115") (name "Net-(LED9-PadA)") (class "Default")
      (node (ref "LED9") (pin "A") (pinfunction "A_A") (pintype "passive"))
      (node (ref "R44") (pin "2") (pinfunction "2_2") (pintype "passive"))
    )
    (net (code "116") (name "Net-(LED10-PadA)") (class "Default")
      (node (ref "LED10") (pin "A") (pinfunction "A_A") (pintype "passive"))
      (node (ref "R45") (pin "2") (pinfunction "2_2") (pintype "passive"))
    )
    (net (code "117") (name "Net-(LED11-PadC)") (class "Default")
      (node (ref "LED11") (pin "C") (pinfunction "C_C") (pintype "passive"))
      (node (ref "R46") (pin "1") (pinfunction "1_1") (pintype "passive"))
    )
    (net (code "118") (name "Net-(LED12-PadC)") (class "Default")
      (node (ref "LED12") (pin "C") (pinfunction "C_C") (pintype "passive"))
      (node (ref "R3") (pin "1") (pinfunction "1_1") (pintype "passive"))
    )
    (net (code "119") (name "Net-(LED13-PadC)") (class "Default")
      (node (ref "LED13") (pin "C") (pinfunction "C_C") (pintype "passive"))
      (node (ref "R8") (pin "2") (pinfunction "2_2") (pintype "passive"))
    )
    (net (code "120") (name "Net-(LED14-PadC)") (class "Default")
      (node (ref "LED14") (pin "C") (pinfunction "C_C") (pintype "passive"))
      (node (ref "R26") (pin "2") (pinfunction "2_2") (pintype "passive"))
    )
    (net (code "121") (name "Net-(LED15-PadC)") (class "Default")
      (node (ref "LED15") (pin "C") (pinfunction "C_C") (pintype "passive"))
      (node (ref "R27") (pin "2") (pinfunction "2_2") (pintype "passive"))
    )
    (net (code "122") (name "Net-(LED16-PadC)") (class "Default")
      (node (ref "LED16") (pin "C") (pinfunction "C_C") (pintype "passive"))
      (node (ref "R28") (pin "2") (pinfunction "2_2") (pintype "passive"))
    )
    (net (code "123") (name "Net-(R29-Pad2)") (class "Default")
      (node (ref "R29") (pin "2") (pinfunction "2_2") (pintype "passive"))
      (node (ref "R98") (pin "1") (pinfunction "1_1") (pintype "passive"))
    )
    (net (code "124") (name "Net-(R98-Pad2)") (class "Default")
      (node (ref "R98") (pin "2") (pinfunction "2_2") (pintype "passive"))
      (node (ref "R99") (pin "1") (pinfunction "1_1") (pintype "passive"))
    )
    (net (code "125") (name "Net-(R100-Pad1)") (class "Default")
      (node (ref "R100") (pin "1") (pinfunction "1_1") (pintype "passive"))
      (node (ref "R99") (pin "2") (pinfunction "2_2") (pintype "passive"))
    )
    (net (code "126") (name "Net-(R100-Pad2)") (class "Default")
      (node (ref "R100") (pin "2") (pinfunction "2_2") (pintype "passive"))
      (node (ref "R101") (pin "1") (pinfunction "1_1") (pintype "passive"))
    )
    (net (code "127") (name "Net-(R103-Pad1)") (class "Default")
      (node (ref "R103") (pin "1") (pinfunction "1_1") (pintype "passive"))
      (node (ref "R33") (pin "2") (pinfunction "2_2") (pintype "passive"))
    )
    (net (code "128") (name "Net-(R103-Pad2)") (class "Default")
      (node (ref "R103") (pin "2") (pinfunction "2_2") (pintype "passive"))
      (node (ref "R104") (pin "1") (pinfunction "1_1") (pintype "passive"))
    )
    (net (code "129") (name "Net-(R104-Pad2)") (class "Default")
      (node (ref "R104") (pin "2") (pinfunction "2_2") (pintype "passive"))
      (node (ref "R105") (pin "1") (pinfunction "1_1") (pintype "passive"))
    )
    (net (code "130") (name "Net-(R105-Pad2)") (class "Default")
      (node (ref "R105") (pin "2") (pinfunction "2_2") (pintype "passive"))
      (node (ref "R106") (pin "1") (pinfunction "1_1") (pintype "passive"))
    )
    (net (code "131") (name "Net-(S2-1)") (class "Default")
      (node (ref "R31") (pin "2") (pinfunction "2_2") (pintype "passive"))
      (node (ref "S2") (pin "P$1") (pinfunction "1_P$1") (pintype "bidirectional"))
    )
    (net (code "132") (name "Net-(U4A-ADREFHI)") (class "Default")
      (node (ref "C31") (pin "1") (pinfunction "1_1") (pintype "passive"))
      (node (ref "C32") (pin "1") (pinfunction "1_1") (pintype "passive"))
      (node (ref "L4") (pin "2") (pinfunction "2_2") (pintype "passive"))
      (node (ref "U4") (pin "66") (pinfunction "ADREFHI_66") (pintype "power_in"))
    )
    (net (code "133") (name "Net-(U4B-KELVIN_GND)") (class "Default")
      (node (ref "C50") (pin "2") (pinfunction "2_2") (pintype "passive"))
      (node (ref "C51") (pin "2") (pinfunction "2_2") (pintype "passive"))
      (node (ref "U4") (pin "19") (pinfunction "KELVIN_GND_19") (pintype "input"))
    )
    (net (code "134") (name "Net-(U4B-NERROR)") (class "Default")
      (node (ref "LED4") (pin "C") (pinfunction "C_C") (pintype "passive"))
      (node (ref "U4") (pin "117") (pinfunction "NERROR_117") (pintype "bidirectional"))
    )
    (net (code "135") (name "Net-(U4B-NRST)") (class "Default")
      (node (ref "C52") (pin "1") (pinfunction "1_1") (pintype "passive"))
      (node (ref "R31") (pin "1") (pinfunction "1_1") (pintype "passive"))
      (node (ref "R32") (pin "2") (pinfunction "2_2") (pintype "passive"))
      (node (ref "U4") (pin "116") (pinfunction "NRST_116") (pintype "bidirectional"))
    )
    (net (code "136") (name "Net-(U4B-OSCIN)") (class "Default")
      (node (ref "C50") (pin "1") (pinfunction "1_1") (pintype "passive"))
      (node (ref "U4") (pin "18") (pinfunction "OSCIN_18") (pintype "input"))
      (node (ref "Y2") (pin "P$1") (pinfunction "P$1_P$1") (pintype "bidirectional"))
    )
    (net (code "137") (name "Net-(U4B-OSCOUT)") (class "Default")
      (node (ref "C51") (pin "1") (pinfunction "1_1") (pintype "passive"))
      (node (ref "U4") (pin "20") (pinfunction "OSCOUT_20") (pintype "output"))
      (node (ref "Y2") (pin "P$2") (pinfunction "P$3_P$2") (pintype "bidirectional"))
    )
    (net (code "138") (name "Net-(U5A-IN)") (class "Default")
      (node (ref "D11") (pin "CATHODE") (pinfunction "CATHODE_CATHODE") (pintype "bidirectional"))
      (node (ref "R57") (pin "2") (pinfunction "2_2") (pintype "passive"))
      (node (ref "U5") (pin "3") (pinfunction "IN_3") (pintype "input"))
    )
    (net (code "139") (name "Net-(U6A-IN)") (class "Default")
      (node (ref "Q6") (pin "D") (pinfunction "D_D") (pintype "bidirectional"))
      (node (ref "R23") (pin "2") (pinfunction "2_2") (pintype "passive"))
      (node (ref "U6") (pin "3") (pinfunction "IN_3") (pintype "input"))
    )
    (net (code "140") (name "Net-(U6A-OUT)") (class "Default")
      (node (ref "D8") (pin "ANODE") (pinfunction "ANODE_ANODE") (pintype "bidirectional"))
      (node (ref "U6") (pin "2") (pinfunction "OUT_2") (pintype "output"))
    )
    (net (code "141") (name "Net-(U6B-IN)") (class "Default")
      (node (ref "Q5") (pin "D") (pinfunction "D_D") (pintype "bidirectional"))
      (node (ref "R4") (pin "2") (pinfunction "2_2") (pintype "passive"))
      (node (ref "U6") (pin "5") (pinfunction "IN_5") (pintype "input"))
    )
    (net (code "142") (name "Net-(U6B-OUT)") (class "Default")
      (node (ref "D6") (pin "ANODE") (pinfunction "ANODE_ANODE") (pintype "bidirectional"))
      (node (ref "U6") (pin "4") (pinfunction "OUT_4") (pintype "output"))
    )
    (net (code "143") (name "Net-(U6C-IN)") (class "Default")
      (node (ref "Q4") (pin "D") (pinfunction "D_D") (pintype "bidirectional"))
      (node (ref "R19") (pin "2") (pinfunction "2_2") (pintype "passive"))
      (node (ref "U6") (pin "7") (pinfunction "IN_7") (pintype "input"))
    )
    (net (code "144") (name "Net-(U6C-OUT)") (class "Default")
      (node (ref "D4") (pin "ANODE") (pinfunction "ANODE_ANODE") (pintype "bidirectional"))
      (node (ref "U6") (pin "6") (pinfunction "OUT_6") (pintype "output"))
    )
    (net (code "145") (name "Net-(U6D-IN)") (class "Default")
      (node (ref "Q3") (pin "D") (pinfunction "D_D") (pintype "bidirectional"))
      (node (ref "R18") (pin "2") (pinfunction "2_2") (pintype "passive"))
      (node (ref "U6") (pin "9") (pinfunction "IN_9") (pintype "input"))
    )
    (net (code "146") (name "Net-(U6D-OUT)") (class "Default")
      (node (ref "D3") (pin "ANODE") (pinfunction "ANODE_ANODE") (pintype "bidirectional"))
      (node (ref "U6") (pin "10") (pinfunction "OUT_10") (pintype "output"))
    )
    (net (code "147") (name "Net-(U6E-IN)") (class "Default")
      (node (ref "Q2") (pin "D") (pinfunction "D_D") (pintype "bidirectional"))
      (node (ref "R17") (pin "2") (pinfunction "2_2") (pintype "passive"))
      (node (ref "U6") (pin "11") (pinfunction "IN_11") (pintype "input"))
    )
    (net (code "148") (name "Net-(U6E-OUT)") (class "Default")
      (node (ref "D2") (pin "ANODE") (pinfunction "ANODE_ANODE") (pintype "bidirectional"))
      (node (ref "U6") (pin "12") (pinfunction "OUT_12") (pintype "output"))
    )
    (net (code "149") (name "Net-(U6F-OUT)") (class "Default")
      (node (ref "D5") (pin "ANODE") (pinfunction "ANODE_ANODE") (pintype "bidirectional"))
      (node (ref "U6") (pin "15") (pinfunction "OUT_15") (pintype "output"))
    )
    (net (code "150") (name "Net-(U8-PDEN)") (class "Default")
      (node (ref "C9") (pin "1") (pinfunction "1_1") (pintype "passive"))
      (node (ref "U8") (pin "3") (pinfunction "VDD1_3") (pintype "bidirectional"))
      (node (ref "U8") (pin "4") (pinfunction "PDEN_4") (pintype "bidirectional"))
      (node (ref "U8") (pin "5") (pinfunction "SPU_5") (pintype "bidirectional"))
    )
    (net (code "151") (name "Net-(U8-UD+)") (class "Default")
      (node (ref "R10") (pin "2") (pinfunction "2_2") (pintype "passive"))
      (node (ref "U8") (pin "7") (pinfunction "UD+_7") (pintype "bidirectional"))
    )
    (net (code "152") (name "Net-(U8-UD-)") (class "Default")
      (node (ref "R9") (pin "2") (pinfunction "2_2") (pintype "passive"))
      (node (ref "U8") (pin "6") (pinfunction "UD-_6") (pintype "bidirectional"))
    )
    (net (code "153") (name "Net-(U14A-OUT)") (class "Default")
      (node (ref "R6") (pin "1") (pinfunction "1_1") (pintype "passive"))
      (node (ref "U14") (pin "18") (pinfunction "OUT_18") (pintype "output"))
    )
    (net (code "154") (name "Net-(U14B-OUT)") (class "Default")
      (node (ref "R46") (pin "2") (pinfunction "2_2") (pintype "passive"))
      (node (ref "U14") (pin "17") (pinfunction "OUT_17") (pintype "output"))
    )
    (net (code "155") (name "Net-(U14C-OUT)") (class "Default")
      (node (ref "R43") (pin "1") (pinfunction "1_1") (pintype "passive"))
      (node (ref "U14") (pin "16") (pinfunction "OUT_16") (pintype "output"))
    )
    (net (code "156") (name "Net-(U14D-OUT)") (class "Default")
      (node (ref "R42") (pin "1") (pinfunction "1_1") (pintype "passive"))
      (node (ref "U14") (pin "15") (pinfunction "OUT_15") (pintype "output"))
    )
    (net (code "157") (name "Net-(U14E-OUT)") (class "Default")
      (node (ref "R41") (pin "1") (pinfunction "1_1") (pintype "passive"))
      (node (ref "U14") (pin "14") (pinfunction "OUT_14") (pintype "output"))
    )
    (net (code "158") (name "Net-(U14H-OUT)") (class "Default")
      (node (ref "R45") (pin "1") (pinfunction "1_1") (pintype "passive"))
      (node (ref "U14") (pin "13") (pinfunction "OUT_13") (pintype "output"))
    )
    (net (code "159") (name "Net-(U14I-OUT)") (class "Default")
      (node (ref "R44") (pin "1") (pinfunction "1_1") (pintype "passive"))
      (node (ref "U14") (pin "12") (pinfunction "OUT_12") (pintype "output"))
    )
    (net (code "160") (name "Net-(U14J-OUT)") (class "Default")
      (node (ref "R3") (pin "2") (pinfunction "2_2") (pintype "passive"))
      (node (ref "U14") (pin "11") (pinfunction "OUT_11") (pintype "output"))
    )
    (net (code "161") (name "Net-(U17A-IN2)") (class "Default")
      (node (ref "U17") (pin "2") (pinfunction "IN2_2") (pintype "input"))
      (node (ref "U2") (pin "4") (pinfunction "OUT_4") (pintype "output"))
      (node (ref "U3") (pin "2") (pinfunction "IN2_2") (pintype "input"))
    )
    (net (code "162") (name "Net-(U22A-OUT)") (class "Default")
      (node (ref "U22") (pin "7") (pinfunction "OUT_7") (pintype "output"))
      (node (ref "U24") (pin "4") (pinfunction "G_4") (pintype "input"))
    )
    (net (code "163") (name "Net-(U22B-OUT)") (class "Default")
      (node (ref "U22") (pin "5") (pinfunction "OUT_5") (pintype "output"))
      (node (ref "U25") (pin "4") (pinfunction "G_4") (pintype "input"))
    )
    (net (code "164") (name "Net-(U23A-OUT)") (class "Default")
      (node (ref "U23") (pin "7") (pinfunction "OUT_7") (pintype "output"))
      (node (ref "U27") (pin "4") (pinfunction "G_4") (pintype "input"))
    )
    (net (code "165") (name "Net-(U30-INB)") (class "Default")
      (node (ref "U30") (pin "P$3") (pinfunction "INB_P$3") (pintype "bidirectional"))
      (node (ref "U36") (pin "P$5") (pinfunction "SDATA_P$5") (pintype "bidirectional"))
    )
    (net (code "166") (name "Net-(U30-OUTA)") (class "Default")
      (node (ref "U30") (pin "P$2") (pinfunction "OUTA_P$2") (pintype "bidirectional"))
      (node (ref "U36") (pin "P$6") (pinfunction "~{CS}_P$6") (pintype "bidirectional"))
    )
    (net (code "167") (name "Net-(U31-OUTA)") (class "Default")
      (node (ref "U31") (pin "P$2") (pinfunction "OUTA_P$2") (pintype "bidirectional"))
      (node (ref "U36") (pin "P$4") (pinfunction "SCLK_P$4") (pintype "bidirectional"))
    )
    (net (code "168") (name "Net-(U33-INB)") (class "Default")
      (node (ref "U33") (pin "P$3") (pinfunction "INB_P$3") (pintype "bidirectional"))
      (node (ref "U37") (pin "P$5") (pinfunction "SDATA_P$5") (pintype "bidirectional"))
    )
    (net (code "169") (name "Net-(U33-OUTA)") (class "Default")
      (node (ref "U33") (pin "P$2") (pinfunction "OUTA_P$2") (pintype "bidirectional"))
      (node (ref "U37") (pin "P$6") (pinfunction "~{CS}_P$6") (pintype "bidirectional"))
    )
    (net (code "170") (name "Net-(U34-OUTA)") (class "Default")
      (node (ref "U34") (pin "P$2") (pinfunction "OUTA_P$2") (pintype "bidirectional"))
      (node (ref "U37") (pin "P$4") (pinfunction "SCLK_P$4") (pintype "bidirectional"))
    )
    (net (code "171") (name "Net-(U38-3V3OUT)") (class "Default")
      (node (ref "C4") (pin "1") (pinfunction "1_1") (pintype "passive"))
      (node (ref "U38") (pin "17") (pinfunction "3V3OUT_17") (pintype "output"))
    )
    (net (code "172") (name "Net-(U38-CBUS0)") (class "Default")
      (node (ref "R7") (pin "1") (pinfunction "1_1") (pintype "passive"))
      (node (ref "U38") (pin "23") (pinfunction "CBUS0_23") (pintype "bidirectional"))
    )
    (net (code "173") (name "Net-(U38-CBUS1)") (class "Default")
      (node (ref "R8") (pin "1") (pinfunction "1_1") (pintype "passive"))
      (node (ref "U38") (pin "22") (pinfunction "CBUS1_22") (pintype "bidirectional"))
    )
    (net (code "174") (name "Net-(U38-USBDM)") (class "Default")
      (node (ref "U38") (pin "16") (pinfunction "USBDM_16") (pintype "bidirectional"))
      (node (ref "U8") (pin "11") (pinfunction "DD-_11") (pintype "bidirectional"))
    )
    (net (code "175") (name "Net-(U38-USBDP)") (class "Default")
      (node (ref "U38") (pin "15") (pinfunction "USBDP_15") (pintype "bidirectional"))
      (node (ref "U8") (pin "10") (pinfunction "DD+_10") (pintype "bidirectional"))
    )
    (net (code "176") (name "Net-(U42-BOOT)") (class "Default")
      (node (ref "C95") (pin "1") (pinfunction "1_1") (pintype "passive"))
      (node (ref "U42") (pin "1") (pinfunction "BOOT_1") (pintype "bidirectional"))
    )
    (net (code "177") (name "Net-(U42-COMP)") (class "Default")
      (node (ref "C94") (pin "1") (pinfunction "1_1") (pintype "passive"))
      (node (ref "R48") (pin "2") (pinfunction "2_2") (pintype "passive"))
      (node (ref "U42") (pin "6") (pinfunction "COMP_6") (pintype "bidirectional"))
    )
    (net (code "178") (name "Net-(U42-EN)") (class "Default")
      (node (ref "R52") (pin "1") (pinfunction "1_1") (pintype "passive"))
      (node (ref "R53") (pin "2") (pinfunction "2_2") (pintype "passive"))
      (node (ref "U42") (pin "3") (pinfunction "EN_3") (pintype "bidirectional"))
    )
    (net (code "179") (name "Net-(U42-FB)") (class "Default")
      (node (ref "R50") (pin "1") (pinfunction "1_1") (pintype "passive"))
      (node (ref "R51") (pin "2") (pinfunction "2_2") (pintype "passive"))
      (node (ref "U42") (pin "5") (pinfunction "FB_5") (pintype "bidirectional"))
    )
    (net (code "180") (name "Net-(U42-RT{slash}CLK)") (class "Default")
      (node (ref "R47") (pin "2") (pinfunction "2_2") (pintype "passive"))
      (node (ref "U42") (pin "4") (pinfunction "RT/CLK_4") (pintype "bidirectional"))
    )
    (net (code "181") (name "unconnected-(H1-Pad3)") (class "Default")
      (node (ref "H1") (pin "3") (pinfunction "3_3") (pintype "bidirectional"))
    )
    (net (code "182") (name "unconnected-(H1-Pad4)") (class "Default")
      (node (ref "H1") (pin "4") (pinfunction "4_4") (pintype "bidirectional"))
    )
    (net (code "183") (name "unconnected-(H4-Pad5)") (class "Default")
      (node (ref "H4") (pin "5") (pinfunction "5_5") (pintype "bidirectional"))
    )
    (net (code "184") (name "unconnected-(H4-Pad7)") (class "Default")
      (node (ref "H4") (pin "7") (pinfunction "7_7") (pintype "bidirectional"))
    )
    (net (code "185") (name "unconnected-(J1-Pad6)") (class "Default")
      (node (ref "J1") (pin "6") (pinfunction "6_6") (pintype "bidirectional"))
    )
    (net (code "186") (name "unconnected-(J1-Pad13)") (class "Default")
      (node (ref "J1") (pin "13") (pinfunction "13_13") (pintype "bidirectional"))
    )
    (net (code "187") (name "unconnected-(J1-Pad14)") (class "Default")
      (node (ref "J1") (pin "14") (pinfunction "14_14") (pintype "bidirectional"))
    )
    (net (code "188") (name "unconnected-(J1-Pad17)") (class "Default")
      (node (ref "J1") (pin "17") (pinfunction "17_17") (pintype "bidirectional"))
    )
    (net (code "189") (name "unconnected-(J1-Pad18)") (class "Default")
      (node (ref "J1") (pin "18") (pinfunction "18_18") (pintype "bidirectional"))
    )
    (net (code "190") (name "unconnected-(J1-Pad19)") (class "Default")
      (node (ref "J1") (pin "19") (pinfunction "19_19") (pintype "bidirectional"))
    )
    (net (code "191") (name "unconnected-(J2-P10-PadP$10)") (class "Default")
      (node (ref "J2") (pin "P$10") (pinfunction "P10_P$10") (pintype "bidirectional"))
    )
    (net (code "192") (name "unconnected-(J2-P11-PadP$11)") (class "Default")
      (node (ref "J2") (pin "P$11") (pinfunction "P11_P$11") (pintype "bidirectional"))
    )
    (net (code "193") (name "unconnected-(J2-P12-PadP$12)") (class "Default")
      (node (ref "J2") (pin "P$12") (pinfunction "P12_P$12") (pintype "bidirectional"))
    )
    (net (code "194") (name "unconnected-(J2-P13-PadP$13)") (class "Default")
      (node (ref "J2") (pin "P$13") (pinfunction "P13_P$13") (pintype "bidirectional"))
    )
    (net (code "195") (name "unconnected-(J2-P14-PadP$14)") (class "Default")
      (node (ref "J2") (pin "P$14") (pinfunction "P14_P$14") (pintype "bidirectional"))
    )
    (net (code "196") (name "unconnected-(J2-P15-PadP$15)") (class "Default")
      (node (ref "J2") (pin "P$15") (pinfunction "P15_P$15") (pintype "bidirectional"))
    )
    (net (code "197") (name "unconnected-(J2-P17-PadP$17)") (class "Default")
      (node (ref "J2") (pin "P$17") (pinfunction "P17_P$17") (pintype "bidirectional"))
    )
    (net (code "198") (name "unconnected-(J2-P18-PadP$18)") (class "Default")
      (node (ref "J2") (pin "P$18") (pinfunction "P18_P$18") (pintype "bidirectional"))
    )
    (net (code "199") (name "unconnected-(J2-P19-PadP$19)") (class "Default")
      (node (ref "J2") (pin "P$19") (pinfunction "P19_P$19") (pintype "bidirectional"))
    )
    (net (code "200") (name "unconnected-(J2-P20-PadP$20)") (class "Default")
      (node (ref "J2") (pin "P$20") (pinfunction "P20_P$20") (pintype "bidirectional"))
    )
    (net (code "201") (name "unconnected-(J2-P22-PadP$22)") (class "Default")
      (node (ref "J2") (pin "P$22") (pinfunction "P22_P$22") (pintype "bidirectional"))
    )
    (net (code "202") (name "unconnected-(U4A-AD1EVT{slash}MII_RX_ER{slash}RMII_RX_ER-Pad86)") (class "Default")
      (node (ref "U4") (pin "86") (pinfunction "AD1EVT/MII_RX_ER/RMII_RX_ER_86") (pintype "input"))
    )
    (net (code "203") (name "unconnected-(U4A-AD1IN[0]-Pad60)") (class "Default")
      (node (ref "U4") (pin "60") (pinfunction "AD1IN[0]_60") (pintype "input"))
    )
    (net (code "204") (name "unconnected-(U4A-AD1IN[1]-Pad71)") (class "Default")
      (node (ref "U4") (pin "71") (pinfunction "AD1IN[1]_71") (pintype "input"))
    )
    (net (code "205") (name "unconnected-(U4A-AD1IN[4]-Pad76)") (class "Default")
      (node (ref "U4") (pin "76") (pinfunction "AD1IN[4]_76") (pintype "input"))
    )
    (net (code "206") (name "unconnected-(U4A-AD1IN[5]-Pad78)") (class "Default")
      (node (ref "U4") (pin "78") (pinfunction "AD1IN[5]_78") (pintype "input"))
    )
    (net (code "207") (name "unconnected-(U4A-AD1IN[6]-Pad80)") (class "Default")
      (node (ref "U4") (pin "80") (pinfunction "AD1IN[6]_80") (pintype "input"))
    )
    (net (code "208") (name "unconnected-(U4A-AD1IN[7]-Pad61)") (class "Default")
      (node (ref "U4") (pin "61") (pinfunction "AD1IN[7]_61") (pintype "input"))
    )
    (net (code "209") (name "unconnected-(U4A-AD1IN[8]{slash}AD2IN[8]-Pad83)") (class "Default")
      (node (ref "U4") (pin "83") (pinfunction "AD1IN[8]/AD2IN[8]_83") (pintype "input"))
    )
    (net (code "210") (name "unconnected-(U4A-AD1IN[9]{slash}AD2IN[9]-Pad70)") (class "Default")
      (node (ref "U4") (pin "70") (pinfunction "AD1IN[9]/AD2IN[9]_70") (pintype "input"))
    )
    (net (code "211") (name "unconnected-(U4A-AD1IN[10]{slash}AD2IN[10]-Pad72)") (class "Default")
      (node (ref "U4") (pin "72") (pinfunction "AD1IN[10]/AD2IN[10]_72") (pintype "input"))
    )
    (net (code "212") (name "unconnected-(U4A-AD1IN[11]{slash}AD2IN[11]-Pad75)") (class "Default")
      (node (ref "U4") (pin "75") (pinfunction "AD1IN[11]/AD2IN[11]_75") (pintype "input"))
    )
    (net (code "213") (name "unconnected-(U4A-AD1IN[12]{slash}AD2IN[12]-Pad77)") (class "Default")
      (node (ref "U4") (pin "77") (pinfunction "AD1IN[12]/AD2IN[12]_77") (pintype "input"))
    )
    (net (code "214") (name "unconnected-(U4A-AD1IN[13]{slash}AD2IN[13]-Pad79)") (class "Default")
      (node (ref "U4") (pin "79") (pinfunction "AD1IN[13]/AD2IN[13]_79") (pintype "input"))
    )
    (net (code "215") (name "unconnected-(U4A-AD1IN[14]{slash}AD2IN[14]-Pad82)") (class "Default")
      (node (ref "U4") (pin "82") (pinfunction "AD1IN[14]/AD2IN[14]_82") (pintype "input"))
    )
    (net (code "216") (name "unconnected-(U4A-AD1IN[15]{slash}AD2IN[15]-Pad85)") (class "Default")
      (node (ref "U4") (pin "85") (pinfunction "AD1IN[15]/AD2IN[15]_85") (pintype "input"))
    )
    (net (code "217") (name "unconnected-(U4A-AD1IN[16]{slash}AD2IN[0]-Pad58)") (class "Default")
      (node (ref "U4") (pin "58") (pinfunction "AD1IN[16]/AD2IN[0]_58") (pintype "input"))
    )
    (net (code "218") (name "unconnected-(U4A-AD1IN[17]{slash}AD2IN[1]-Pad59)") (class "Default")
      (node (ref "U4") (pin "59") (pinfunction "AD1IN[17]/AD2IN[1]_59") (pintype "input"))
    )
    (net (code "219") (name "unconnected-(U4A-AD1IN[18]{slash}AD2IN[2]-Pad62)") (class "Default")
      (node (ref "U4") (pin "62") (pinfunction "AD1IN[18]/AD2IN[2]_62") (pintype "input"))
    )
    (net (code "220") (name "unconnected-(U4A-AD1IN[19]{slash}AD2IN[3]-Pad63)") (class "Default")
      (node (ref "U4") (pin "63") (pinfunction "AD1IN[19]/AD2IN[3]_63") (pintype "input"))
    )
    (net (code "221") (name "unconnected-(U4A-AD1IN[20]{slash}AD2IN[4]-Pad64)") (class "Default")
      (node (ref "U4") (pin "64") (pinfunction "AD1IN[20]/AD2IN[4]_64") (pintype "input"))
    )
    (net (code "222") (name "unconnected-(U4A-AD1IN[21]{slash}AD2IN[5]-Pad65)") (class "Default")
      (node (ref "U4") (pin "65") (pinfunction "AD1IN[21]/AD2IN[5]_65") (pintype "input"))
    )
    (net (code "223") (name "unconnected-(U4A-AD1IN[22]{slash}AD2IN[6]-Pad81)") (class "Default")
      (node (ref "U4") (pin "81") (pinfunction "AD1IN[22]/AD2IN[6]_81") (pintype "input"))
    )
    (net (code "224") (name "unconnected-(U4A-AD1IN[23]{slash}AD2IN[7]-Pad84)") (class "Default")
      (node (ref "U4") (pin "84") (pinfunction "AD1IN[23]/AD2IN[7]_84") (pintype "input"))
    )
    (net (code "225") (name "unconnected-(U4A-CAN3RX-Pad12)") (class "Default")
      (node (ref "U4") (pin "12") (pinfunction "CAN3RX_12") (pintype "bidirectional"))
    )
    (net (code "226") (name "unconnected-(U4A-CAN3TX-Pad13)") (class "Default")
      (node (ref "U4") (pin "13") (pinfunction "CAN3TX_13") (pintype "bidirectional"))
    )
    (net (code "227") (name "unconnected-(U4A-MIBSPI1NENA{slash}N2HET1[23]{slash}MII_RXD[2]{slash}USB1.VP{slash}ECAP4-Pad96)") (class "Default")
      (node (ref "U4") (pin "96") (pinfunction "MIBSPI1NENA/N2HET1[23]/MII_RXD[2]/USB1.VP/ECAP4_96") (pintype "bidirectional"))
    )
    (net (code "228") (name "unconnected-(U4A-MIBSPI3CLK{slash}AWM1_EXT_SEL[1]{slash}EQEP1A-Pad53)") (class "Default")
      (node (ref "U4") (pin "53") (pinfunction "MIBSPI3CLK/AWM1_EXT_SEL[1]/EQEP1A_53") (pintype "bidirectional"))
    )
    (net (code "229") (name "unconnected-(U4A-MIBSPI3NCS[0]{slash}AD2EVT{slash}GIOB[2]{slash}EQEP1I{slash}N2HET2_PIN_NDIS-Pad55)") (class "Default")
      (node (ref "U4") (pin "55") (pinfunction "MIBSPI3NCS[0]/AD2EVT/GIOB[2]/EQEP1I/N2HET2_PIN_NDIS_55") (pintype "bidirectional"))
    )
    (net (code "230") (name "unconnected-(U4A-MIBSPI3NCS[2]{slash}I2C_SDA{slash}N2HET1[27]{slash}NTZ2-Pad4)") (class "Default")
      (node (ref "U4") (pin "4") (pinfunction "MIBSPI3NCS[2]/I2C_SDA/N2HET1[27]/NTZ2_4") (pintype "bidirectional"))
    )
    (net (code "231") (name "unconnected-(U4A-MIBSPI3NCS[3]{slash}I2C_SCL{slash}N2HET1[29]{slash}NTZ1-Pad3)") (class "Default")
      (node (ref "U4") (pin "3") (pinfunction "MIBSPI3NCS[3]/I2C_SCL/N2HET1[29]/NTZ1_3") (pintype "bidirectional"))
    )
    (net (code "232") (name "unconnected-(U4A-MIBSPI3NENA{slash}MIBSPI3NCS[5]{slash}N2HET1[31]{slash}EQEP1B-Pad54)") (class "Default")
      (node (ref "U4") (pin "54") (pinfunction "MIBSPI3NENA/MIBSPI3NCS[5]/N2HET1[31]/EQEP1B_54") (pintype "bidirectional"))
    )
    (net (code "233") (name "unconnected-(U4A-MIBSPI3SIMO[0]{slash}AWM1_EXT_SEL[0]{slash}ECAP3-Pad52)") (class "Default")
      (node (ref "U4") (pin "52") (pinfunction "MIBSPI3SIMO[0]/AWM1_EXT_SEL[0]/ECAP3_52") (pintype "bidirectional"))
    )
    (net (code "234") (name "unconnected-(U4A-MIBSPI3SOMI[0]{slash}AWM1_EXT_ENA{slash}ECAP2-Pad51)") (class "Default")
      (node (ref "U4") (pin "51") (pinfunction "MIBSPI3SOMI[0]/AWM1_EXT_ENA/ECAP2_51") (pintype "bidirectional"))
    )
    (net (code "235") (name "unconnected-(U4A-MIBSPI5CLK{slash}MII_TXEN{slash}RMII_TXEN-Pad100)") (class "Default")
      (node (ref "U4") (pin "100") (pinfunction "MIBSPI5CLK/MII_TXEN/RMII_TXEN_100") (pintype "bidirectional"))
    )
    (net (code "236") (name "unconnected-(U4A-MIBSPI5NCS[0]{slash}EPWM4A-Pad32)") (class "Default")
      (node (ref "U4") (pin "32") (pinfunction "MIBSPI5NCS[0]/EPWM4A_32") (pintype "bidirectional"))
    )
    (net (code "237") (name "unconnected-(U4A-MIBSPI5NENA{slash}MII_RXD[3]{slash}USB1.VM{slash}MIBSPI5SOMI[1]{slash}ECAP5-Pad97)") (class "Default")
      (node (ref "U4") (pin "97") (pinfunction "MIBSPI5NENA/MII_RXD[3]/USB1.VM/MIBSPI5SOMI[1]/ECAP5_97") (pintype "bidirectional"))
    )
    (net (code "238") (name "unconnected-(U4A-MIBSPI5SIMO[0]{slash}MII_TXD[1]{slash}RMII_TXD[1]{slash}MIBSPI5SOMI[2]-Pad99)") (class "Default")
      (node (ref "U4") (pin "99") (pinfunction "MIBSPI5SIMO[0]/MII_TXD[1]/RMII_TXD[1]/MIBSPI5SOMI[2]_99") (pintype "bidirectional"))
    )
    (net (code "239") (name "unconnected-(U4A-MIBSPI5SOMI[0]{slash}MII_TXD[0]{slash}RMII_TXD[0]-Pad98)") (class "Default")
      (node (ref "U4") (pin "98") (pinfunction "MIBSPI5SOMI[0]/MII_TXD[0]/RMII_TXD[0]_98") (pintype "bidirectional"))
    )
    (net (code "240") (name "unconnected-(U4A-N2HET1[0]{slash}SPI4CLK{slash}EPWM2B-Pad25)") (class "Default")
      (node (ref "U4") (pin "25") (pinfunction "N2HET1[0]/SPI4CLK/EPWM2B_25") (pintype "bidirectional"))
    )
    (net (code "241") (name "unconnected-(U4A-N2HET1[1]{slash}SPI4NENA{slash}USB2.TXEN{slash}USB_FUNC.PUENO{slash}N2HET2[8]{slash}EQEP2A-Pad23)") (class "Default")
      (node (ref "U4") (pin "23") (pinfunction "N2HET1[1]/SPI4NENA/USB2.TXEN/USB_FUNC.PUENO/N2HET2[8]/EQEP2A_23") (pintype "bidirectional"))
    )
    (net (code "242") (name "unconnected-(U4A-N2HET1[3]{slash}SPI4NCS[0]{slash}USB2.SPEED{slash}USB_FUNC.PUENON{slash}N2HET2[10]{slash}EQEP2B-Pad24)") (class "Default")
      (node (ref "U4") (pin "24") (pinfunction "N2HET1[3]/SPI4NCS[0]/USB2.SPEED/USB_FUNC.PUENON/N2HET2[10]/EQEP2B_24") (pintype "bidirectional"))
    )
    (net (code "243") (name "unconnected-(U4A-N2HET1[5]{slash}SPI4SOMI[0]{slash}N2HET2[12]{slash}EPWM3B-Pad31)") (class "Default")
      (node (ref "U4") (pin "31") (pinfunction "N2HET1[5]/SPI4SOMI[0]/N2HET2[12]/EPWM3B_31") (pintype "bidirectional"))
    )
    (net (code "244") (name "unconnected-(U4A-N2HET1[7]{slash}USB2.PORTPOWER{slash}USB_FUNC.GZO{slash}N2HET2[14]{slash}EPWM7B-Pad33)") (class "Default")
      (node (ref "U4") (pin "33") (pinfunction "N2HET1[7]/USB2.PORTPOWER/USB_FUNC.GZO/N2HET2[14]/EPWM7B_33") (pintype "bidirectional"))
    )
    (net (code "245") (name "unconnected-(U4A-N2HET1[8]{slash}MIBSPI1SIMO[1]{slash}MII_TXD[3]{slash}USB1.OVERCURRENT-Pad106)") (class "Default")
      (node (ref "U4") (pin "106") (pinfunction "N2HET1[8]/MIBSPI1SIMO[1]/MII_TXD[3]/USB1.OVERCURRENT_106") (pintype "bidirectional"))
    )
    (net (code "246") (name "unconnected-(U4A-N2HET1[9]{slash}N2HET2[16]{slash}USB2.SUSPEND{slash}USB_FUNC.SUSPENDO{slash}EPWM7A-Pad35)") (class "Default")
      (node (ref "U4") (pin "35") (pinfunction "N2HET1[9]/N2HET2[16]/USB2.SUSPEND/USB_FUNC.SUSPENDO/EPWM7A_35") (pintype "bidirectional"))
    )
    (net (code "247") (name "unconnected-(U4A-N2HET1[10]{slash}MII_TXCLK{slash}USB1.TXEN{slash}MII_TX_VCLKA4{slash}NTZ3-Pad118)") (class "Default")
      (node (ref "U4") (pin "118") (pinfunction "N2HET1[10]/MII_TXCLK/USB1.TXEN/MII_TX_VCLKA4/NTZ3_118") (pintype "bidirectional"))
    )
    (net (code "248") (name "unconnected-(U4A-N2HET1[11]{slash}MIBSPI3NCS[4]{slash}N2HET2[18]{slash}USB2.OVERCURRENT{slash}USB_FUNC.VBUSI{slash}EPWM1SYNCO-Pad6)") (class "Default")
      (node (ref "U4") (pin "6") (pinfunction "N2HET1[11]/MIBSPI3NCS[4]/N2HET2[18]/USB2.OVERCURRENT/USB_FUNC.VBUSI/EPWM1SYNCO_6") (pintype "bidirectional"))
    )
    (net (code "249") (name "unconnected-(U4A-N2HET1[15]{slash}MIBSPI1NCS[4]{slash}ECAP1-Pad41)") (class "Default")
      (node (ref "U4") (pin "41") (pinfunction "N2HET1[15]/MIBSPI1NCS[4]/ECAP1_41") (pintype "bidirectional"))
    )
    (net (code "250") (name "unconnected-(U4A-N2HET1[22]{slash}USB2.TXSE0{slash}USB_FUNC.SE0O-Pad15)") (class "Default")
      (node (ref "U4") (pin "15") (pinfunction "N2HET1[22]/USB2.TXSE0/USB_FUNC.SE0O_15") (pintype "bidirectional"))
    )
    (net (code "251") (name "unconnected-(U4A-N2HET1[24]{slash}MIBSPI1NCS[5]{slash}MII_RXD[0]{slash}RMII_RXD[0]-Pad91)") (class "Default")
      (node (ref "U4") (pin "91") (pinfunction "N2HET1[24]/MIBSPI1NCS[5]/MII_RXD[0]/RMII_RXD[0]_91") (pintype "bidirectional"))
    )
    (net (code "252") (name "unconnected-(U4A-N2HET1[26]{slash}MII_RXD[1]{slash}RMII_RXD[1]-Pad92)") (class "Default")
      (node (ref "U4") (pin "92") (pinfunction "N2HET1[26]/MII_RXD[1]/RMII_RXD[1]_92") (pintype "bidirectional"))
    )
    (net (code "253") (name "unconnected-(U4A-N2HET1[28]{slash}MII_RXCLK{slash}RMII_REFCLK{slash}MII_RX_VCLKA4-Pad107)") (class "Default")
      (node (ref "U4") (pin "107") (pinfunction "N2HET1[28]/MII_RXCLK/RMII_REFCLK/MII_RX_VCLKA4_107") (pintype "bidirectional"))
    )
    (net (code "254") (name "unconnected-(U4A-N2HET1[30]{slash}MII_RX_DV{slash}USB1.SPEED{slash}EQEP2S-Pad127)") (class "Default")
      (node (ref "U4") (pin "127") (pinfunction "N2HET1[30]/MII_RX_DV/USB1.SPEED/EQEP2S_127") (pintype "bidirectional"))
    )
    (net (code "255") (name "unconnected-(U4B-ECLK-Pad119)") (class "Default")
      (node (ref "U4") (pin "119") (pinfunction "ECLK_119") (pintype "bidirectional"))
    )
    (net (code "256") (name "unconnected-(U4B-FLTP1-Pad7)") (class "Default")
      (node (ref "U4") (pin "7") (pinfunction "FLTP1_7") (pintype "bidirectional"))
    )
    (net (code "257") (name "unconnected-(U4B-FLTP2-Pad8)") (class "Default")
      (node (ref "U4") (pin "8") (pinfunction "FLTP2_8") (pintype "bidirectional"))
    )
    (net (code "258") (name "unconnected-(U5D-IN-Pad9)") (class "Default")
      (node (ref "U5") (pin "9") (pinfunction "IN_9") (pintype "input"))
    )
    (net (code "259") (name "unconnected-(U5D-OUT-Pad10)") (class "Default")
      (node (ref "U5") (pin "10") (pinfunction "OUT_10") (pintype "output"))
    )
    (net (code "260") (name "unconnected-(U5E-IN-Pad11)") (class "Default")
      (node (ref "U5") (pin "11") (pinfunction "IN_11") (pintype "input"))
    )
    (net (code "261") (name "unconnected-(U5E-OUT-Pad12)") (class "Default")
      (node (ref "U5") (pin "12") (pinfunction "OUT_12") (pintype "output"))
    )
    (net (code "262") (name "unconnected-(U5F-IN-Pad14)") (class "Default")
      (node (ref "U5") (pin "14") (pinfunction "IN_14") (pintype "input"))
    )
    (net (code "263") (name "unconnected-(U5F-OUT-Pad15)") (class "Default")
      (node (ref "U5") (pin "15") (pinfunction "OUT_15") (pintype "output"))
    )
    (net (code "264") (name "unconnected-(U23B-IN-Pad4)") (class "Default")
      (node (ref "U23") (pin "4") (pinfunction "IN_4") (pintype "input"))
    )
    (net (code "265") (name "unconnected-(U23B-OUT-Pad5)") (class "Default")
      (node (ref "U23") (pin "5") (pinfunction "OUT_5") (pintype "output"))
    )
    (net (code "266") (name "unconnected-(U38-CBUS2-Pad13)") (class "Default")
      (node (ref "U38") (pin "13") (pinfunction "CBUS2_13") (pintype "bidirectional"))
    )
    (net (code "267") (name "unconnected-(U38-CBUS3-Pad14)") (class "Default")
      (node (ref "U38") (pin "14") (pinfunction "CBUS3_14") (pintype "bidirectional"))
    )
    (net (code "268") (name "unconnected-(U38-CBUS4-Pad12)") (class "Default")
      (node (ref "U38") (pin "12") (pinfunction "CBUS4_12") (pintype "bidirectional"))
    )
    (net (code "269") (name "unconnected-(U38-OSCI-Pad27)") (class "Default")
      (node (ref "U38") (pin "27") (pinfunction "OSCI_27") (pintype "input"))
    )
    (net (code "270") (name "unconnected-(U38-OSCO-Pad28)") (class "Default")
      (node (ref "U38") (pin "28") (pinfunction "OSCO_28") (pintype "output"))
    )
    (net (code "271") (name "unconnected-(U38-~{CTS}-Pad11)") (class "Default")
      (node (ref "U38") (pin "11") (pinfunction "~{CTS}_11") (pintype "input"))
    )
    (net (code "272") (name "unconnected-(U38-~{DCD}-Pad10)") (class "Default")
      (node (ref "U38") (pin "10") (pinfunction "~{DCD}_10") (pintype "input"))
    )
    (net (code "273") (name "unconnected-(U38-~{DSR}-Pad9)") (class "Default")
      (node (ref "U38") (pin "9") (pinfunction "~{DSR}_9") (pintype "input"))
    )
    (net (code "274") (name "unconnected-(U38-~{DTR}-Pad2)") (class "Default")
      (node (ref "U38") (pin "2") (pinfunction "~{DTR}_2") (pintype "output"))
    )
    (net (code "275") (name "unconnected-(U38-~{RI}-Pad6)") (class "Default")
      (node (ref "U38") (pin "6") (pinfunction "~{RI}_6") (pintype "input"))
    )
    (net (code "276") (name "unconnected-(U38-~{RTS}-Pad3)") (class "Default")
      (node (ref "U38") (pin "3") (pinfunction "~{RTS}_3") (pintype "output"))
    )
  )
)
